# 8BIT_LOGIC_2.net
KiCad netlist of a schematic drawn in EAGLE
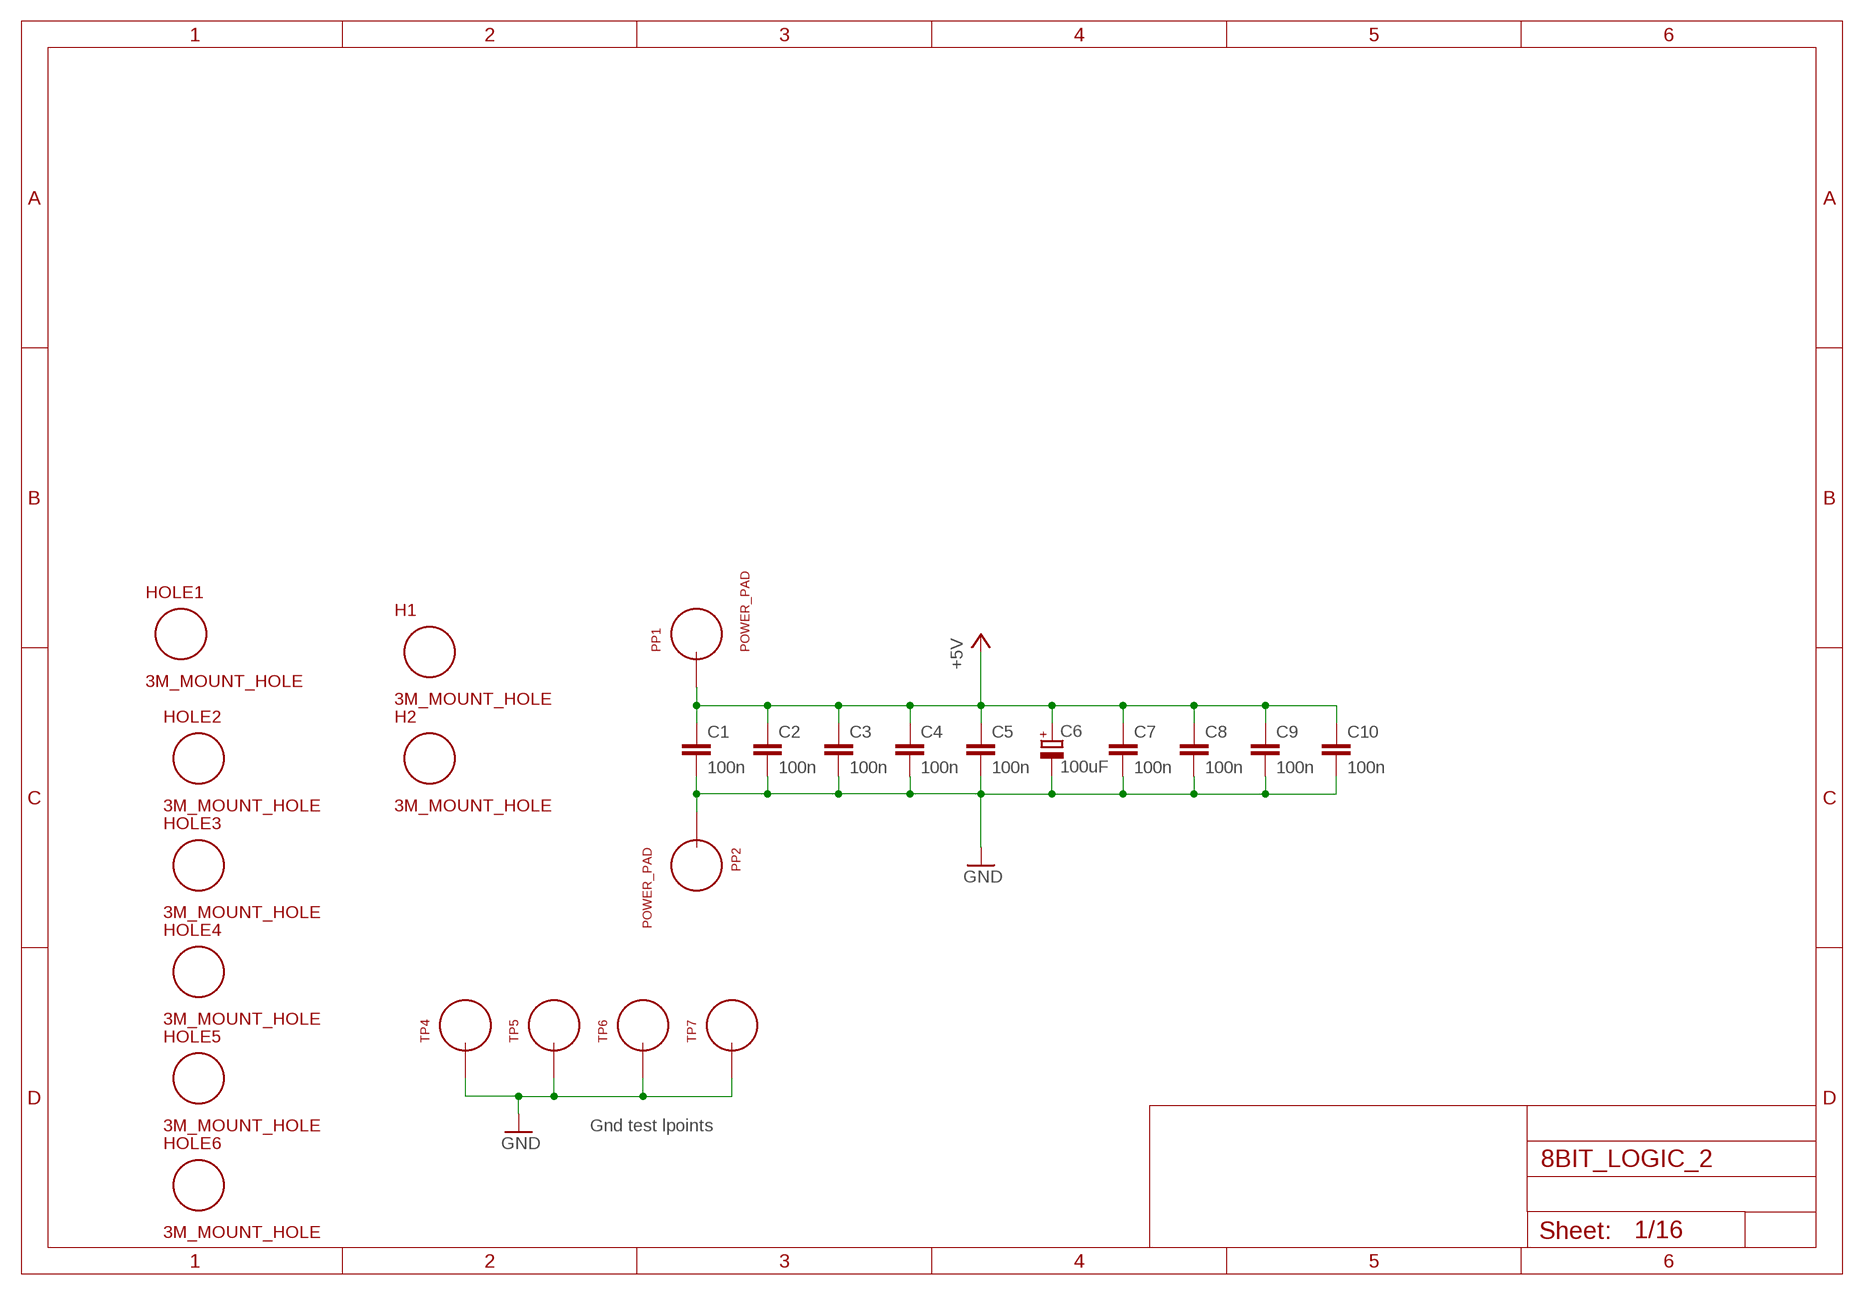
[diagram p0: schematic, sheet 1]
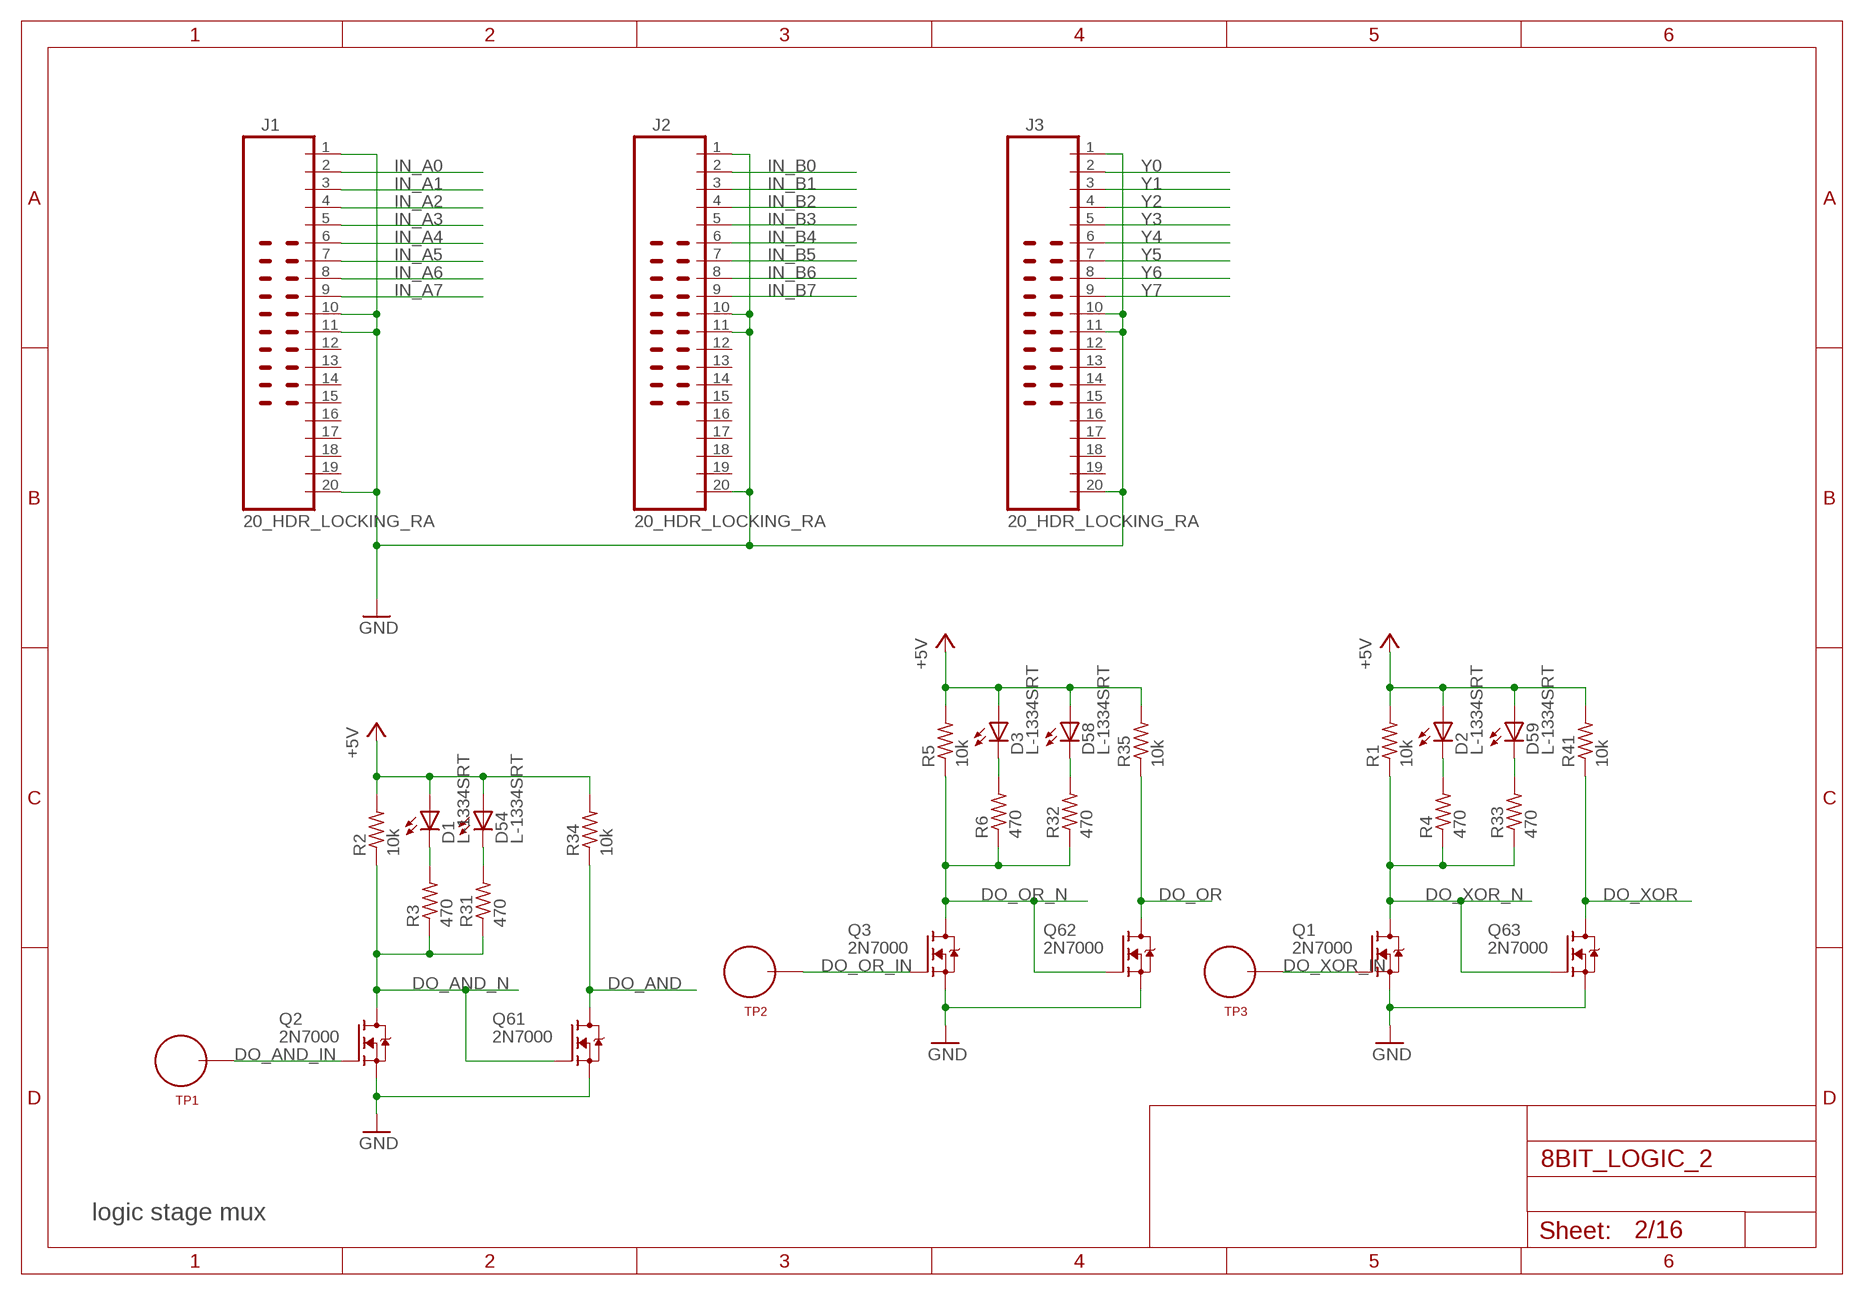
[diagram p1: schematic, sheet 2]
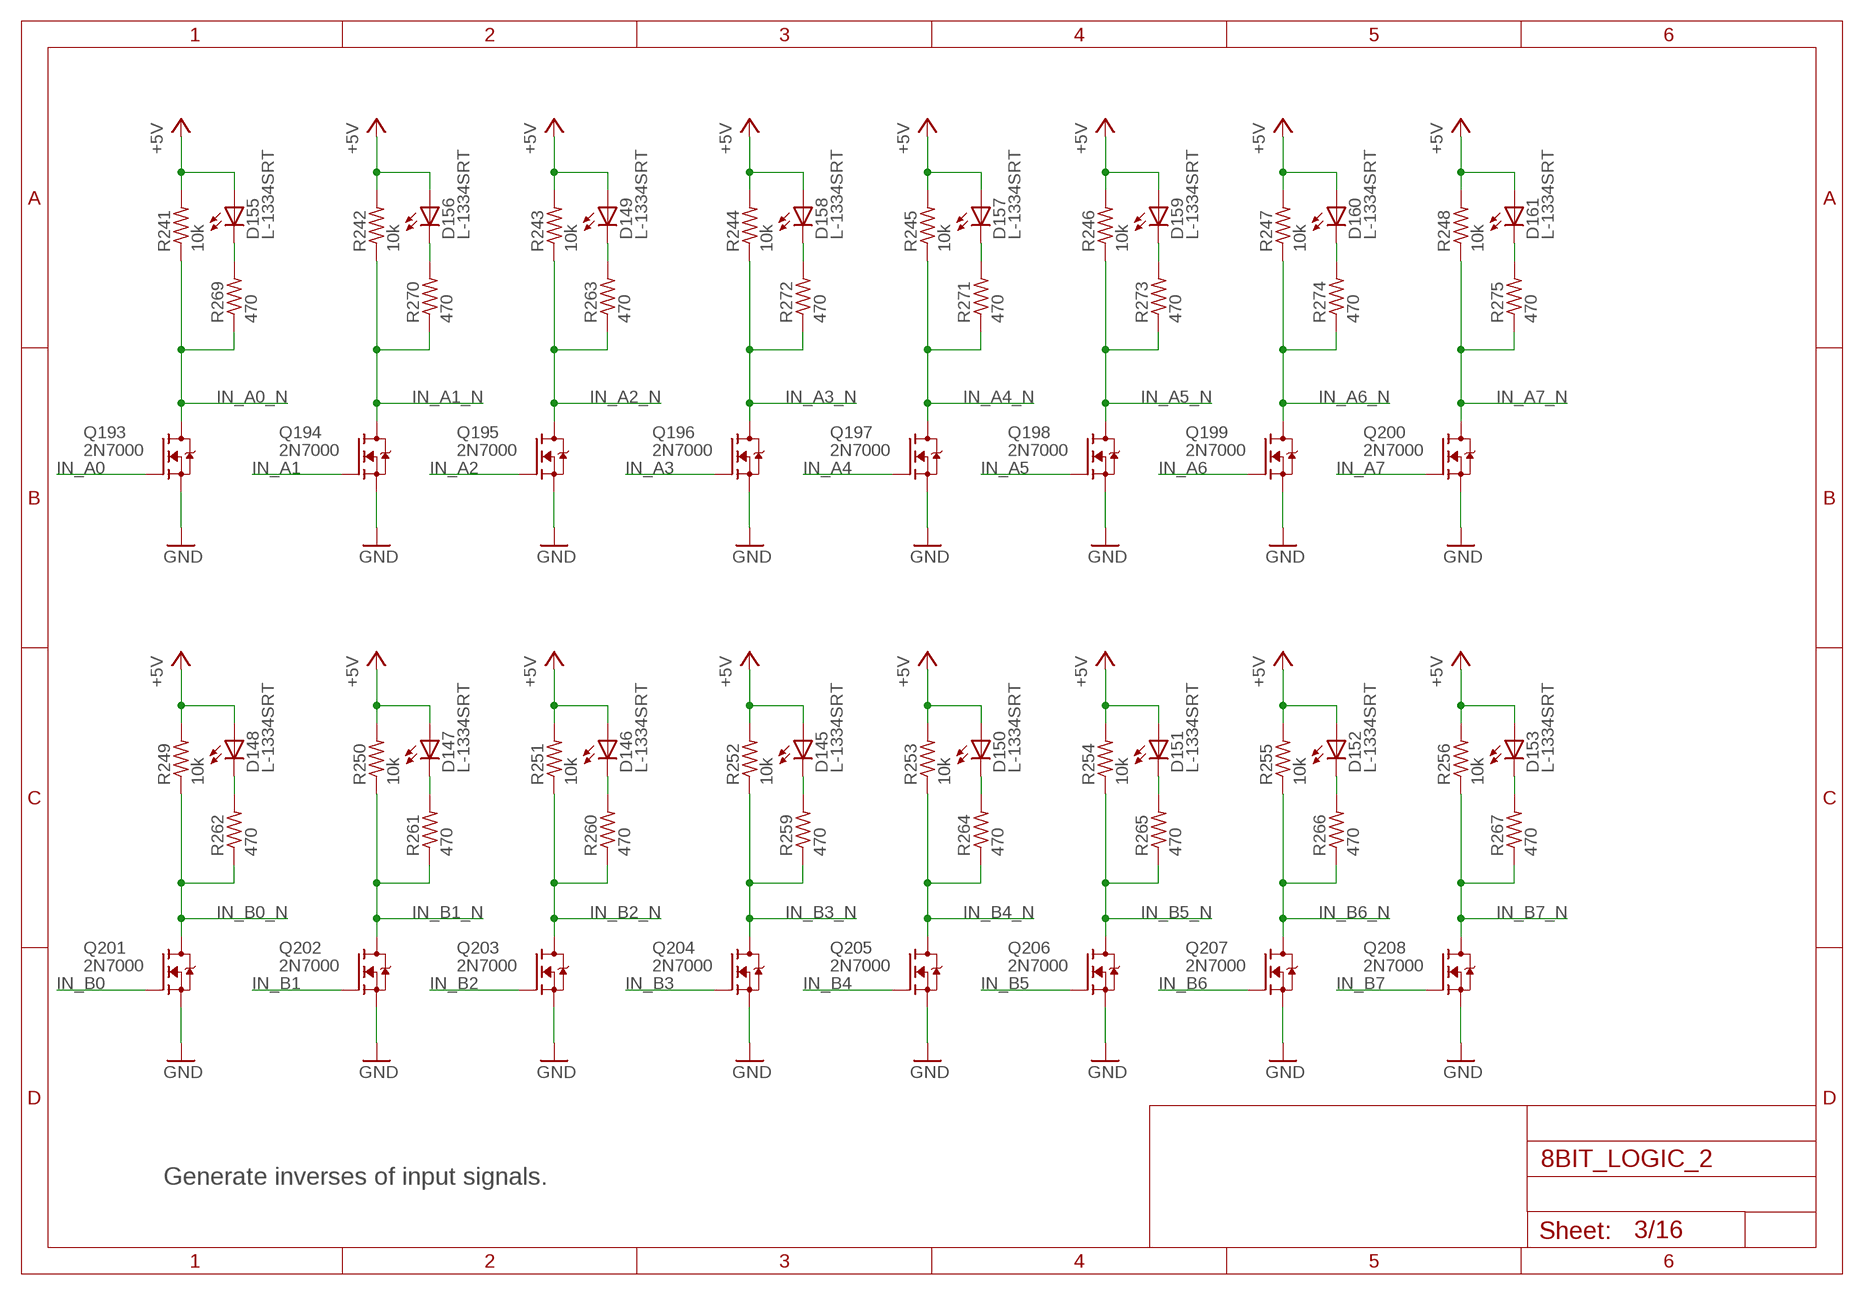
[diagram p2: schematic, sheet 3]
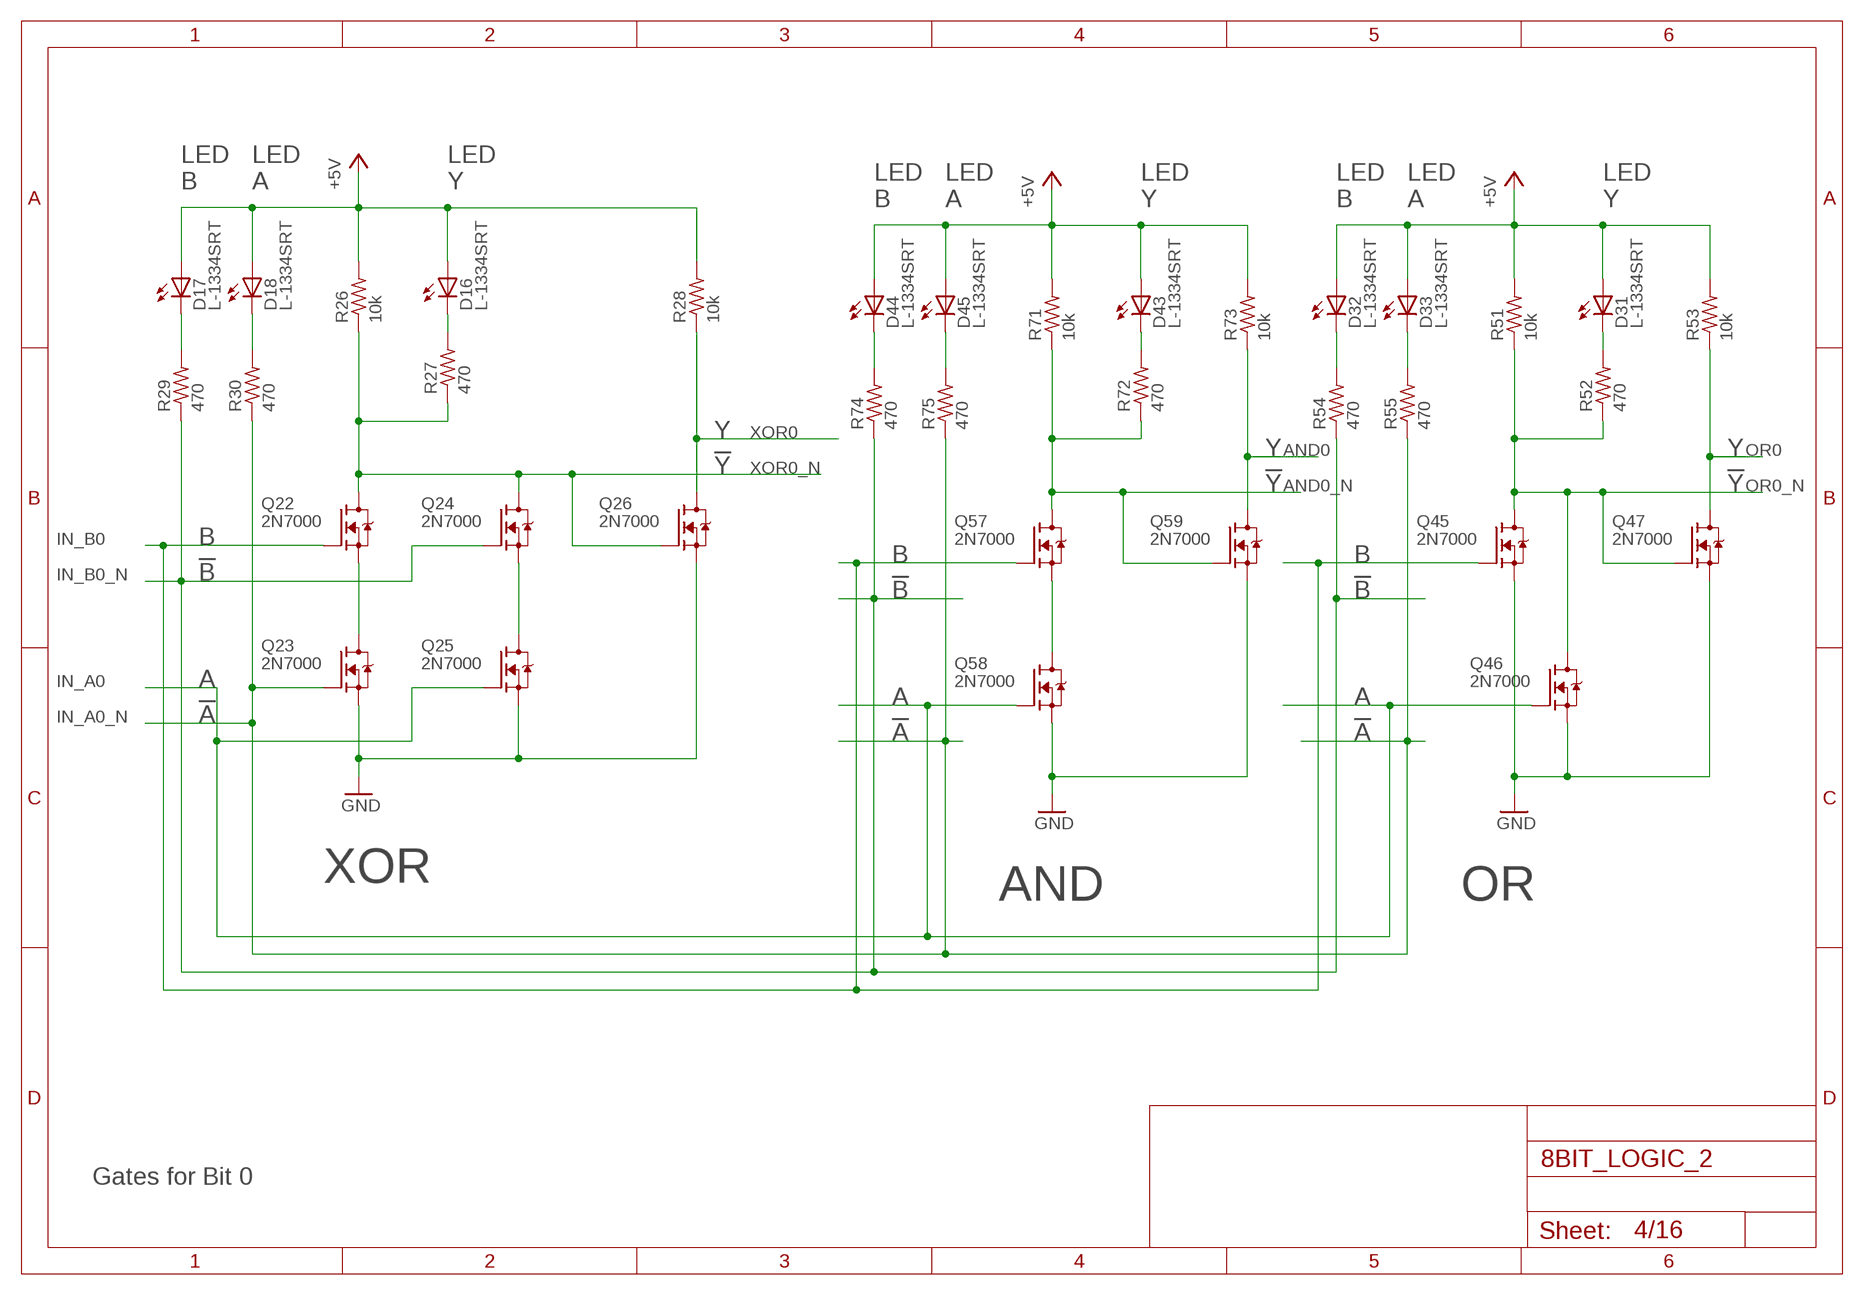
[diagram p3: schematic, sheet 4]
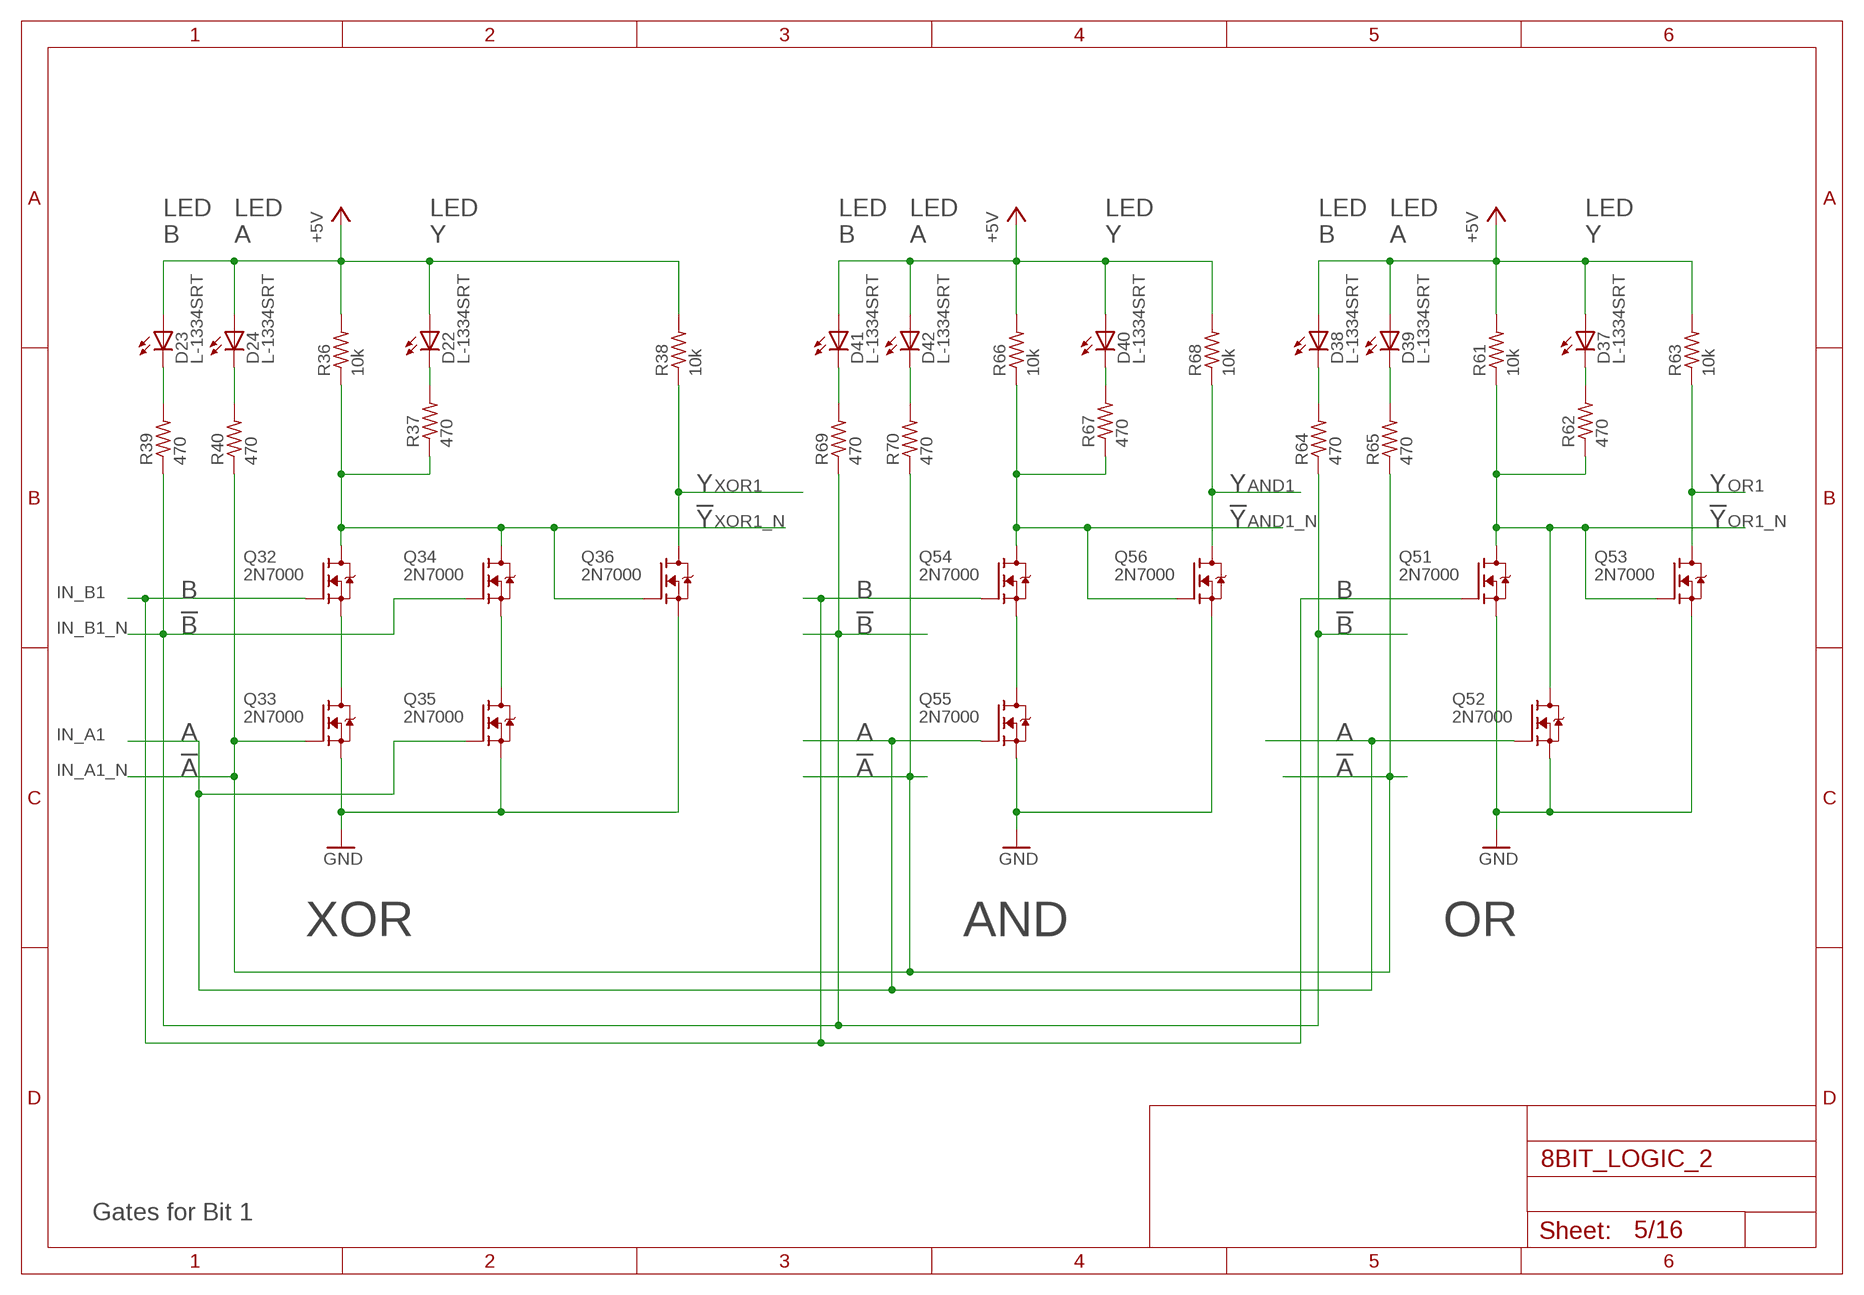
[diagram p4: schematic, sheet 5]
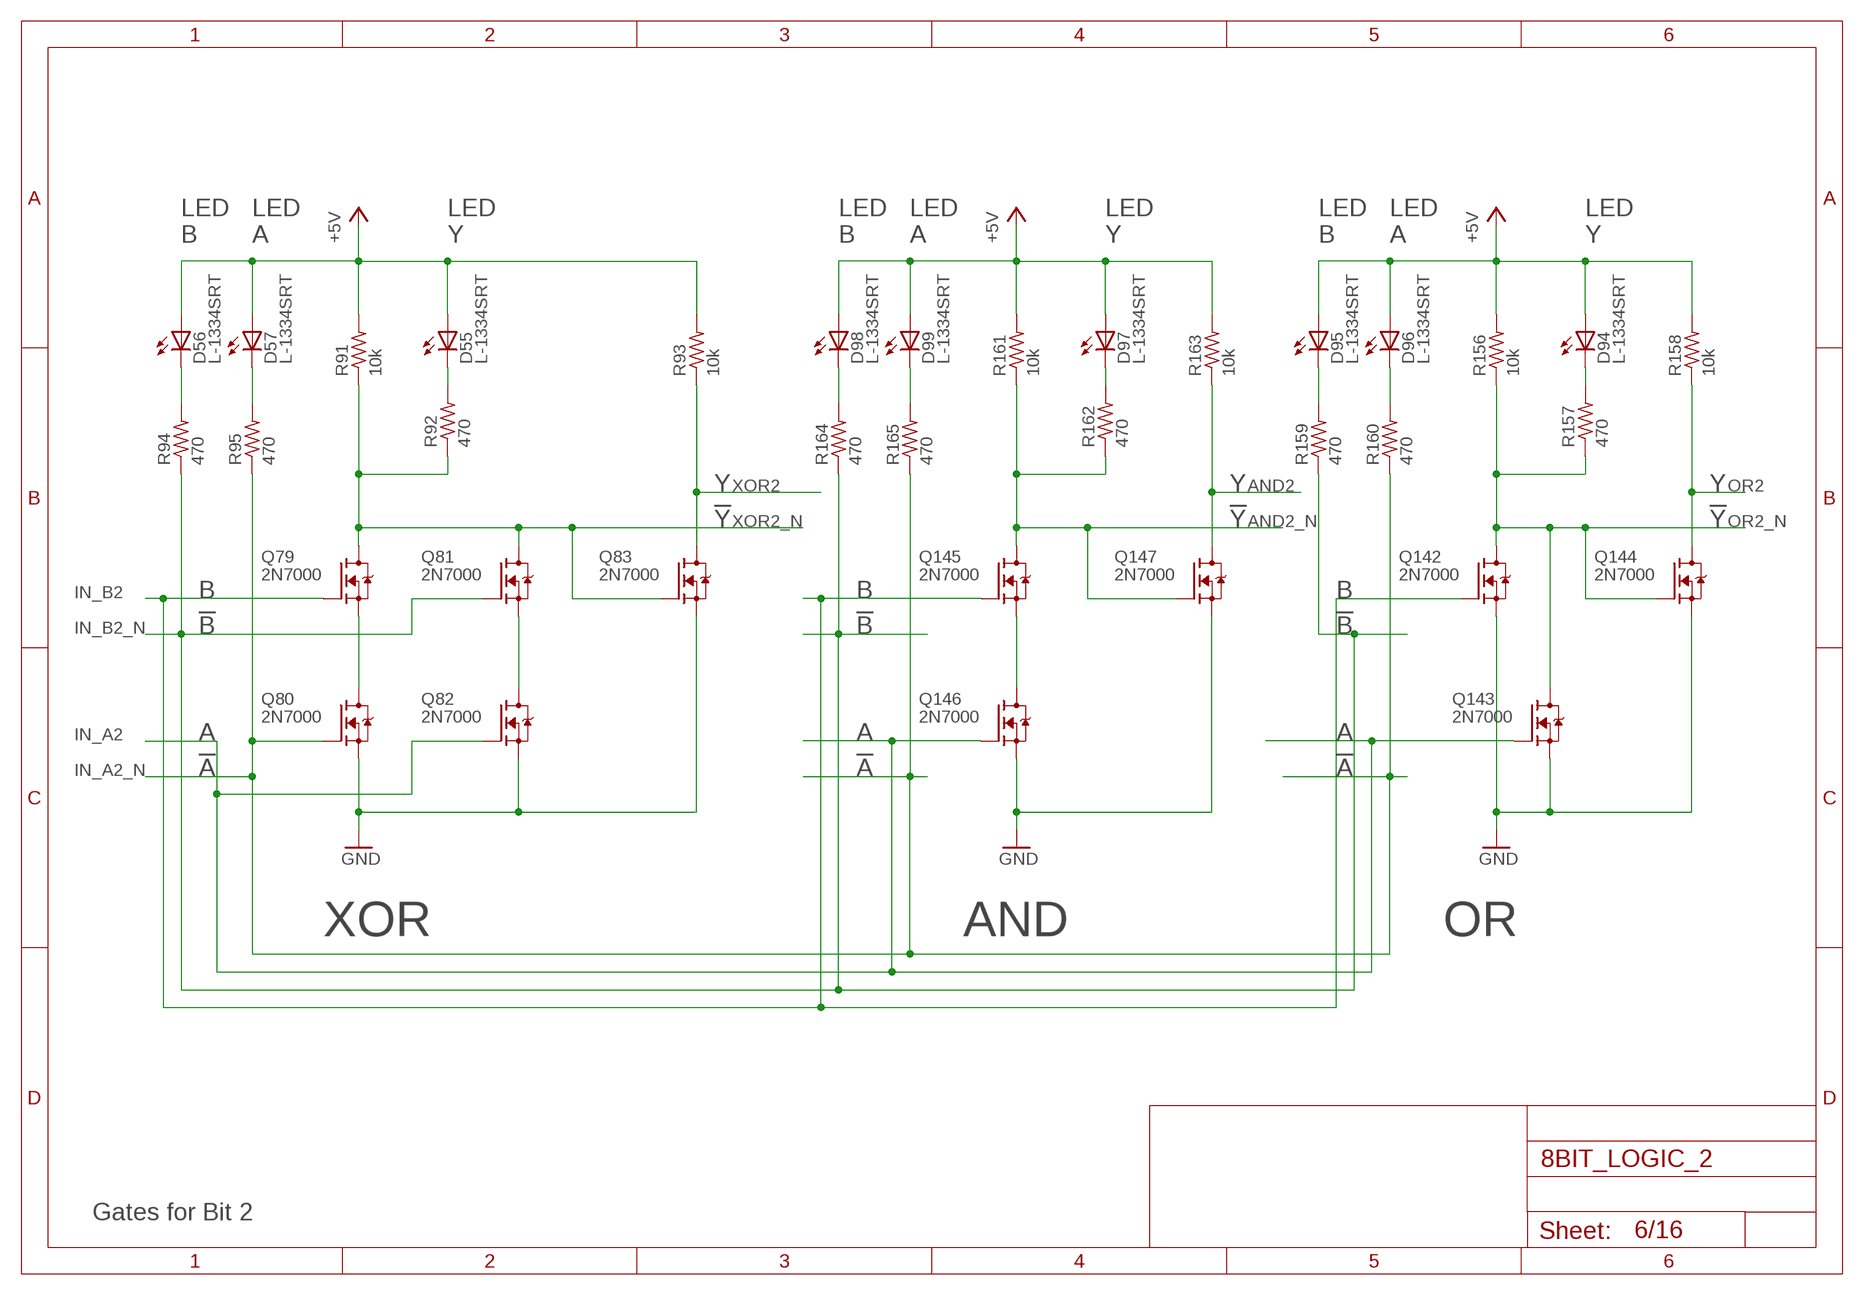
[diagram p5: schematic, sheet 6]
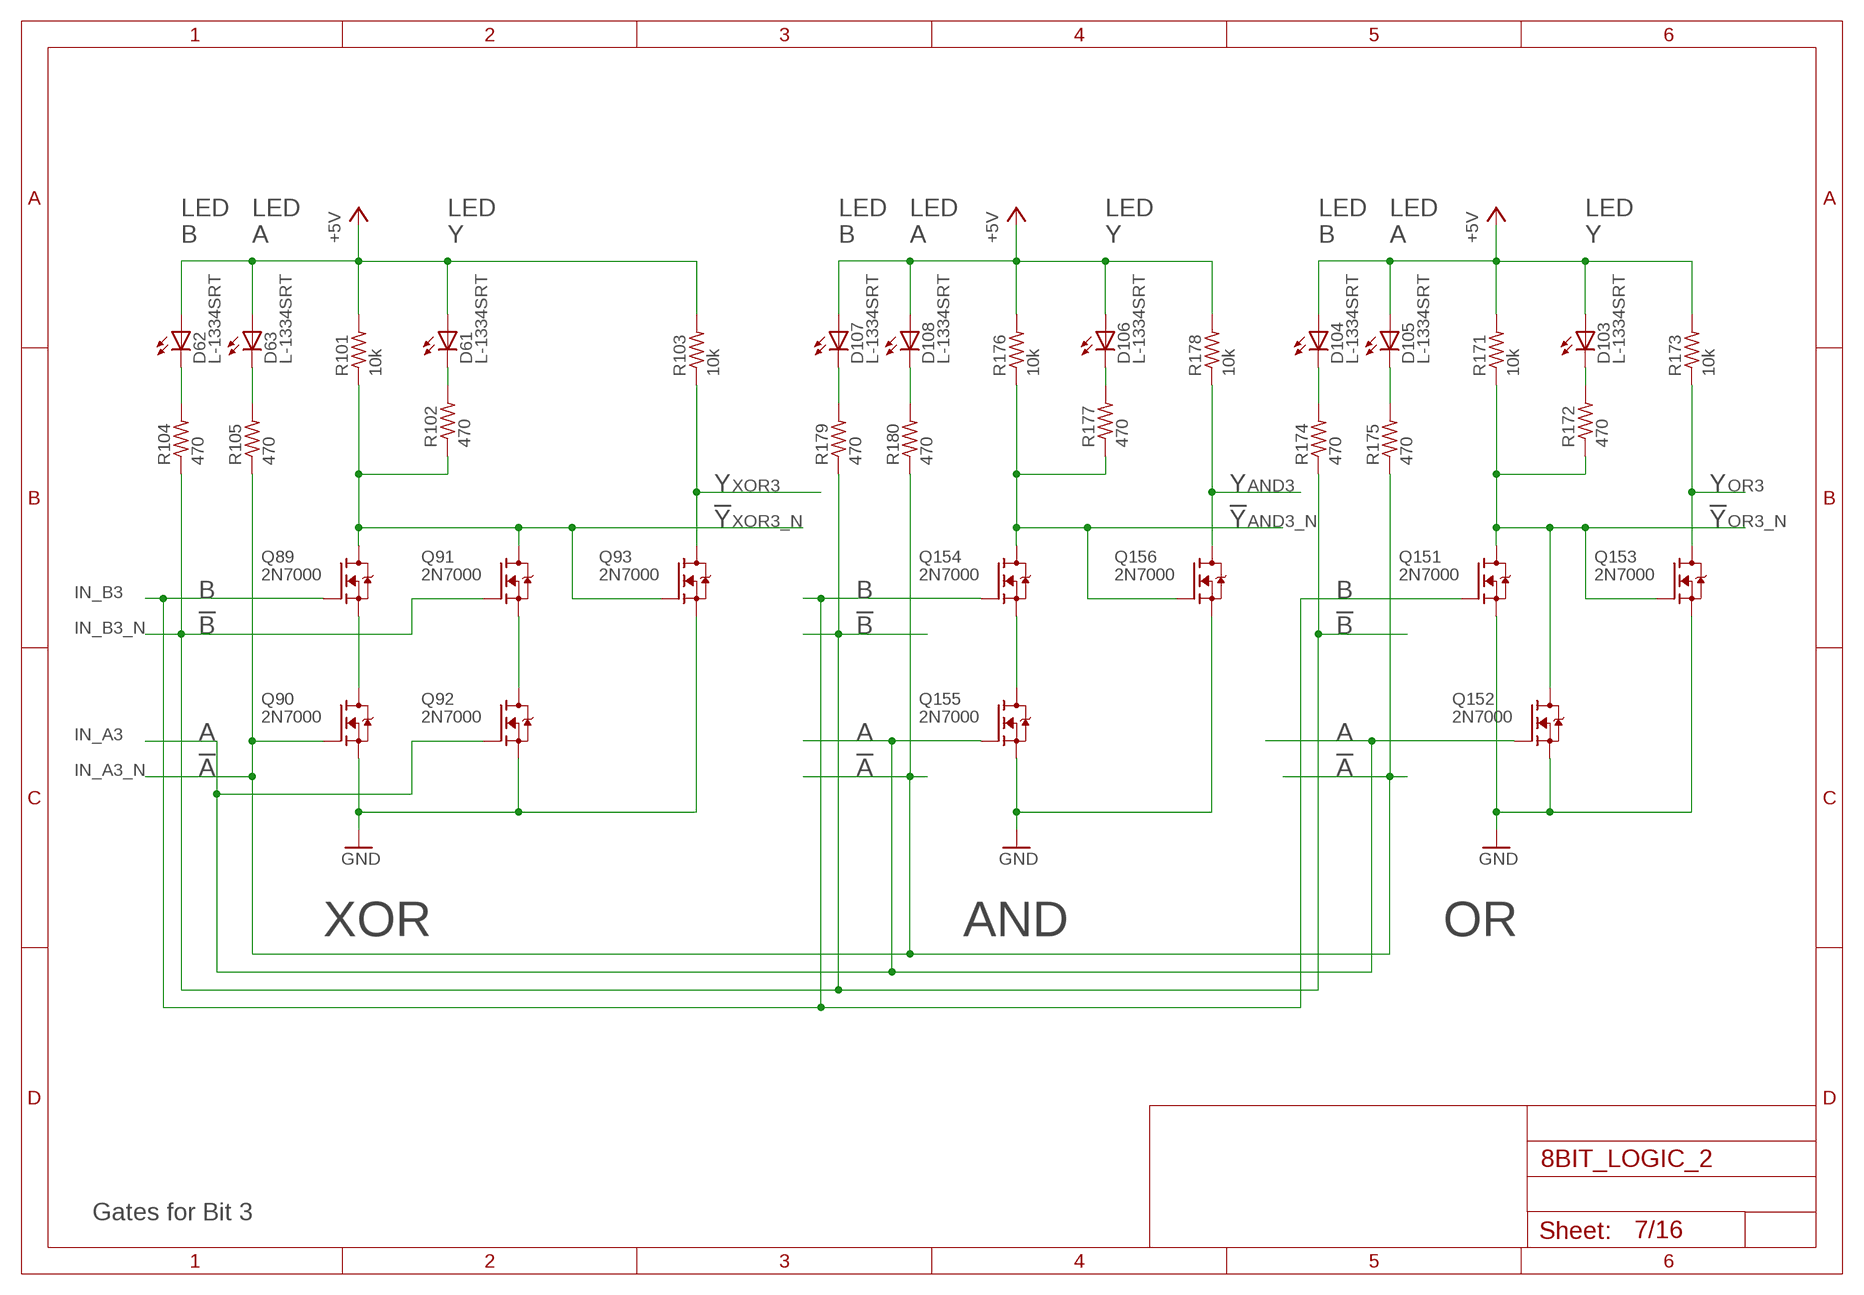
[diagram p6: schematic, sheet 7]
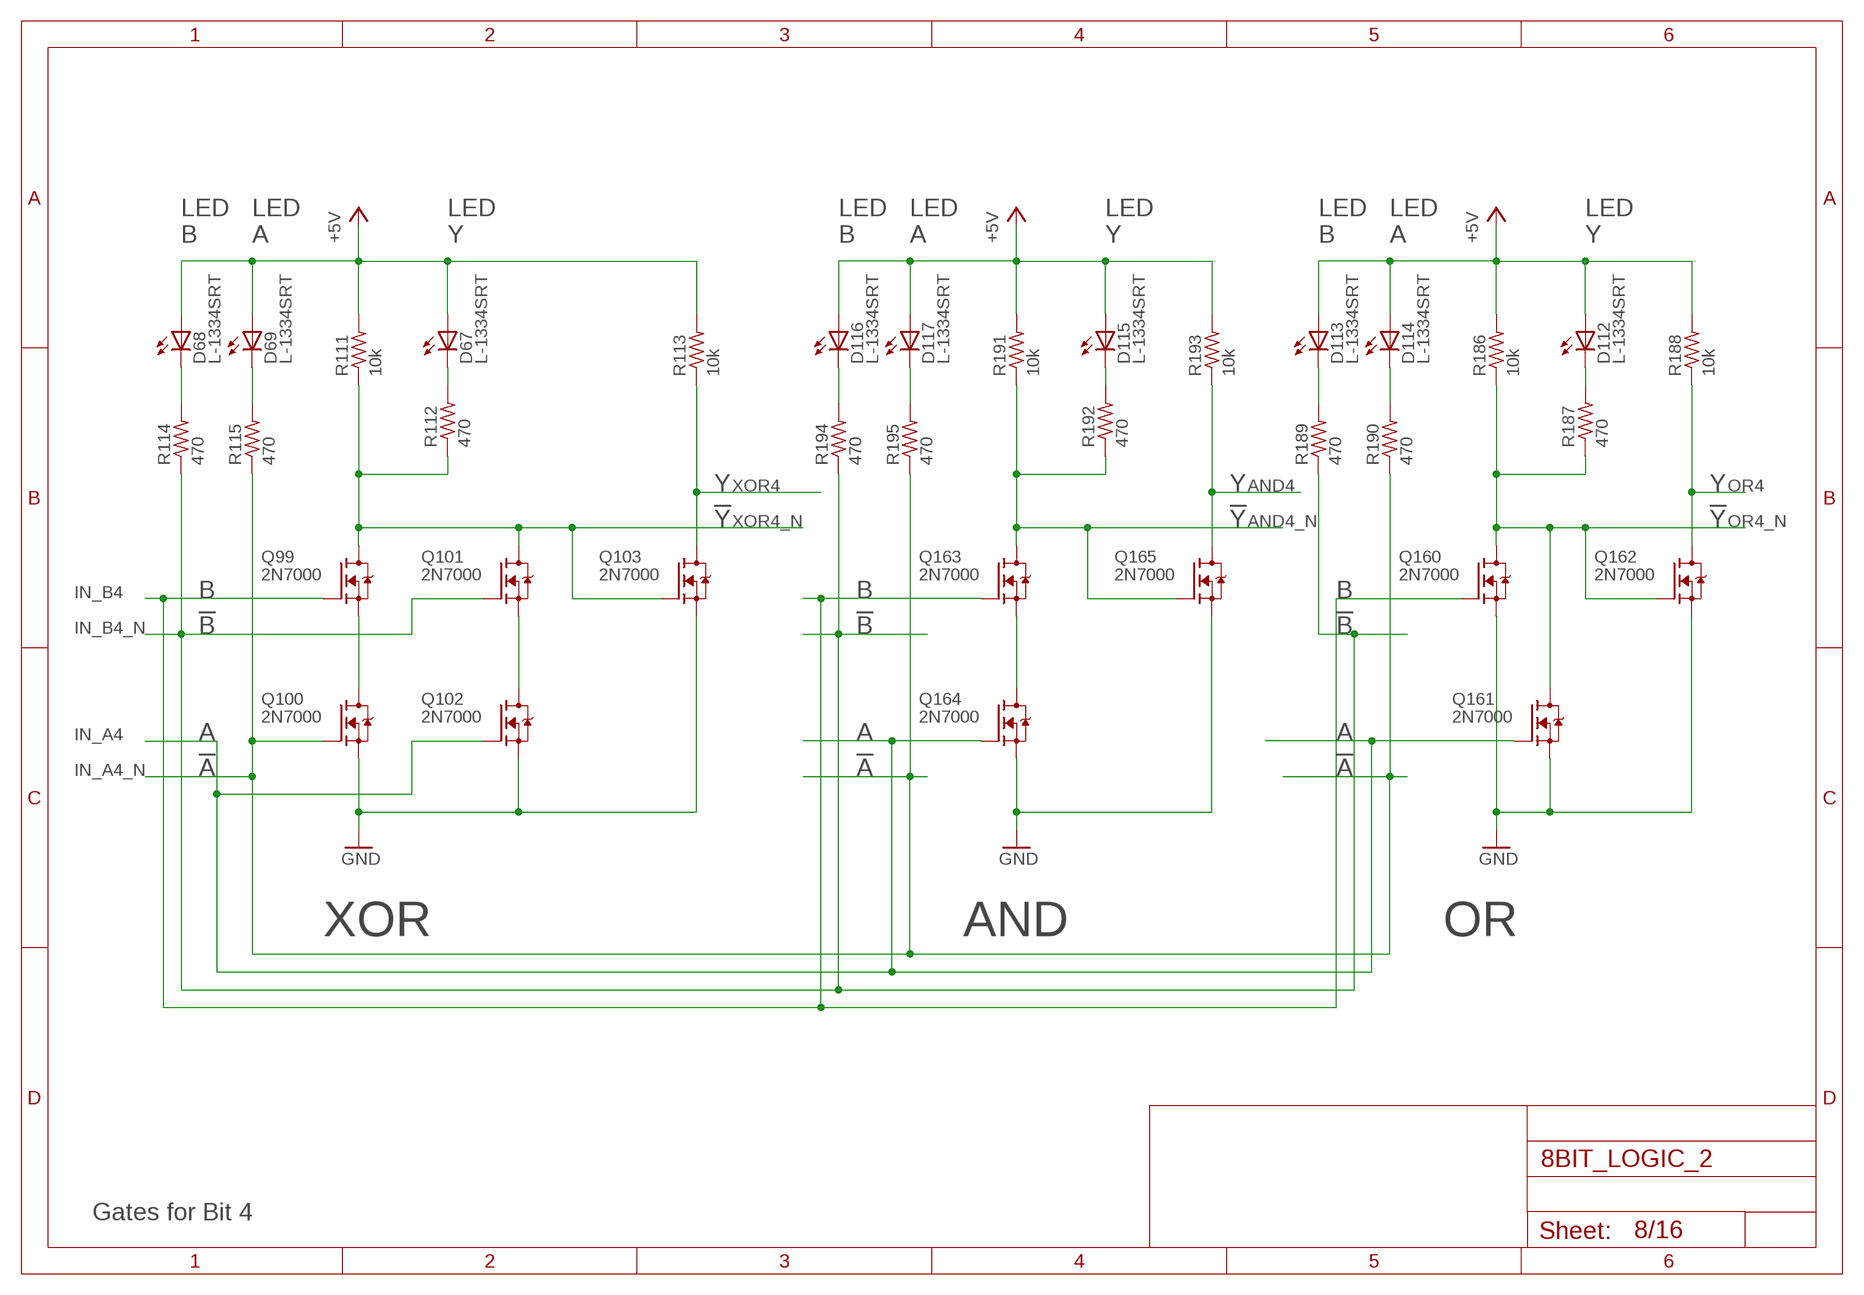
[diagram p7: schematic, sheet 8]
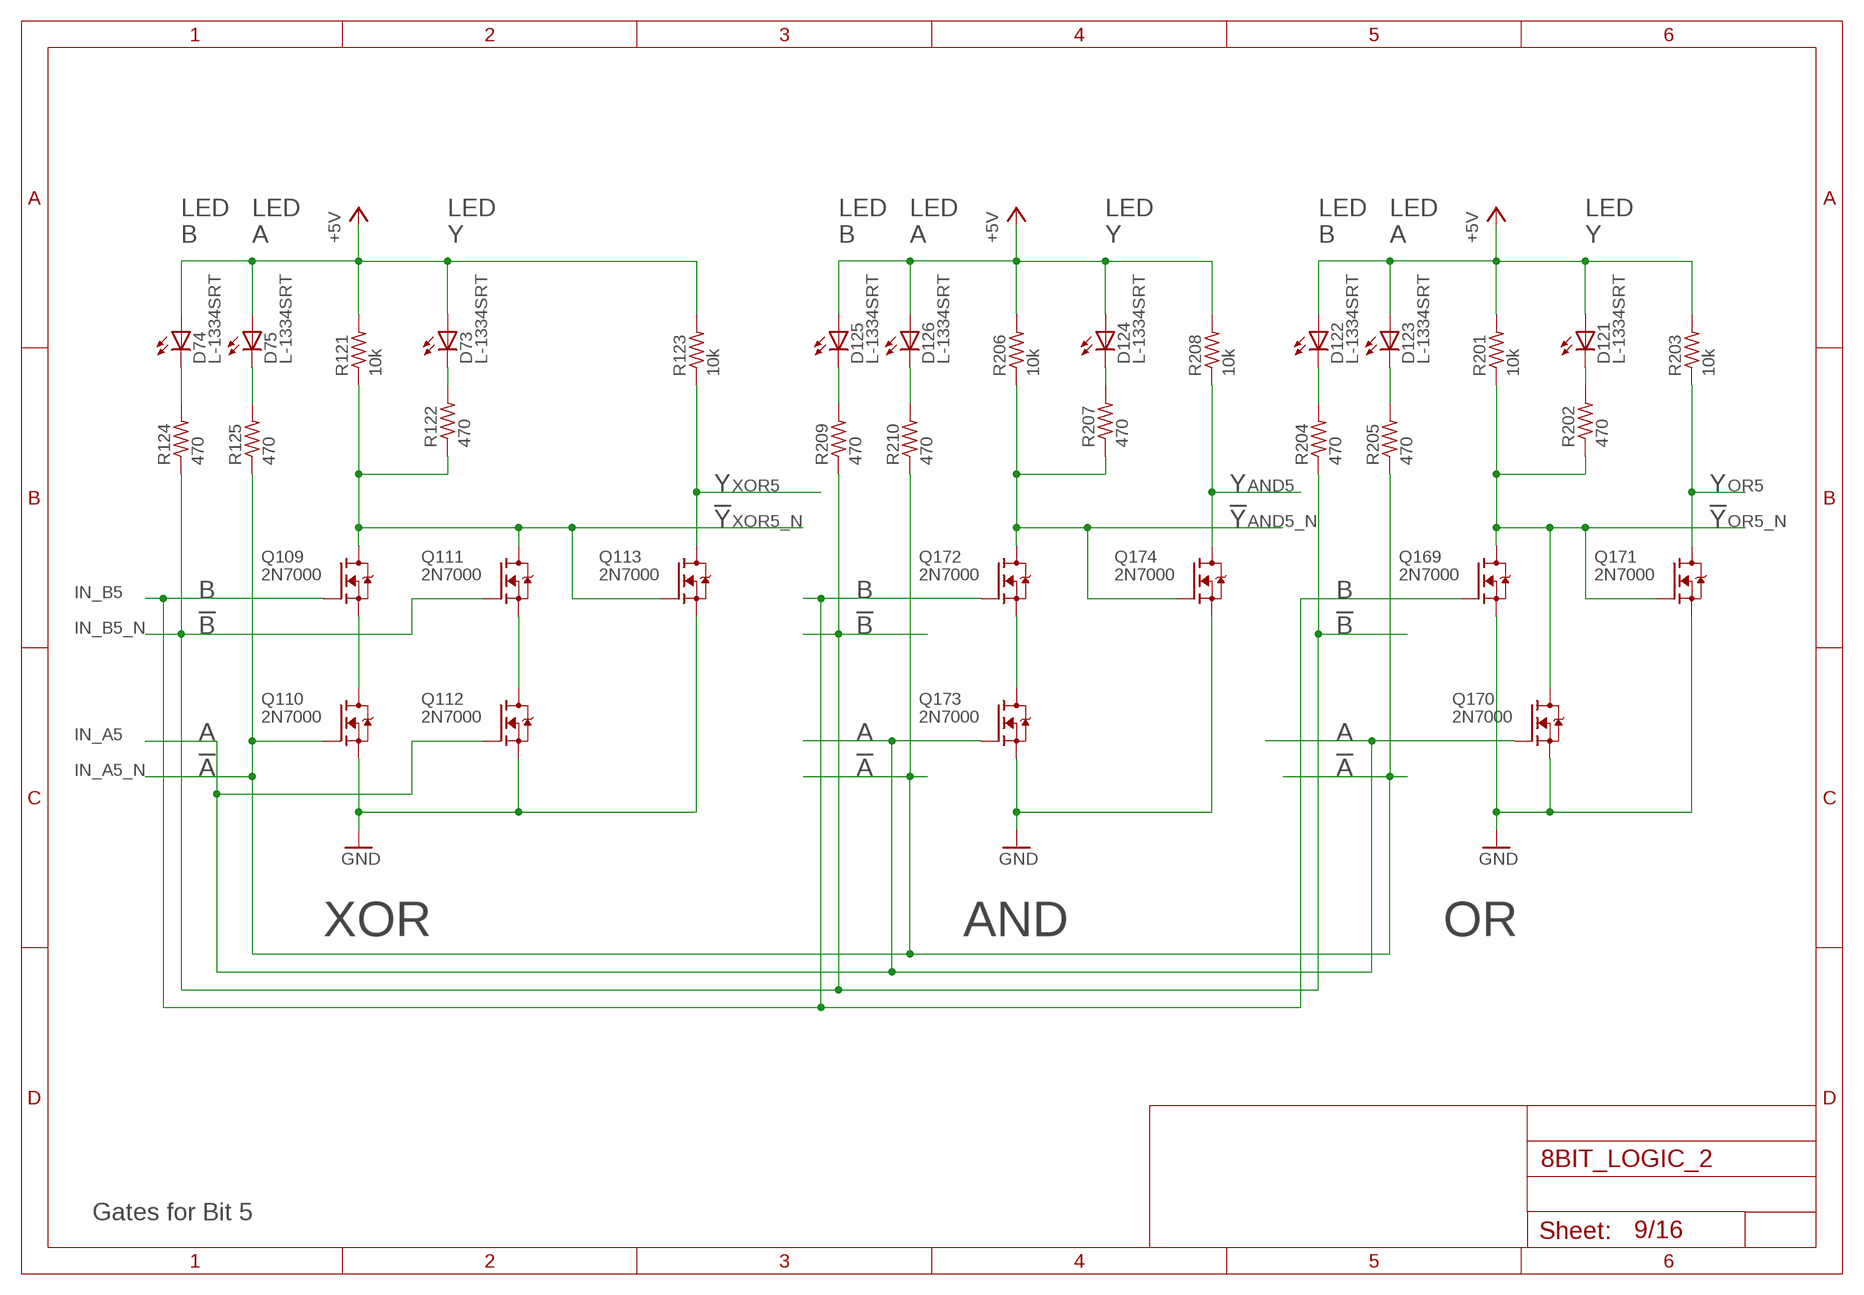
[diagram p8: schematic, sheet 9]
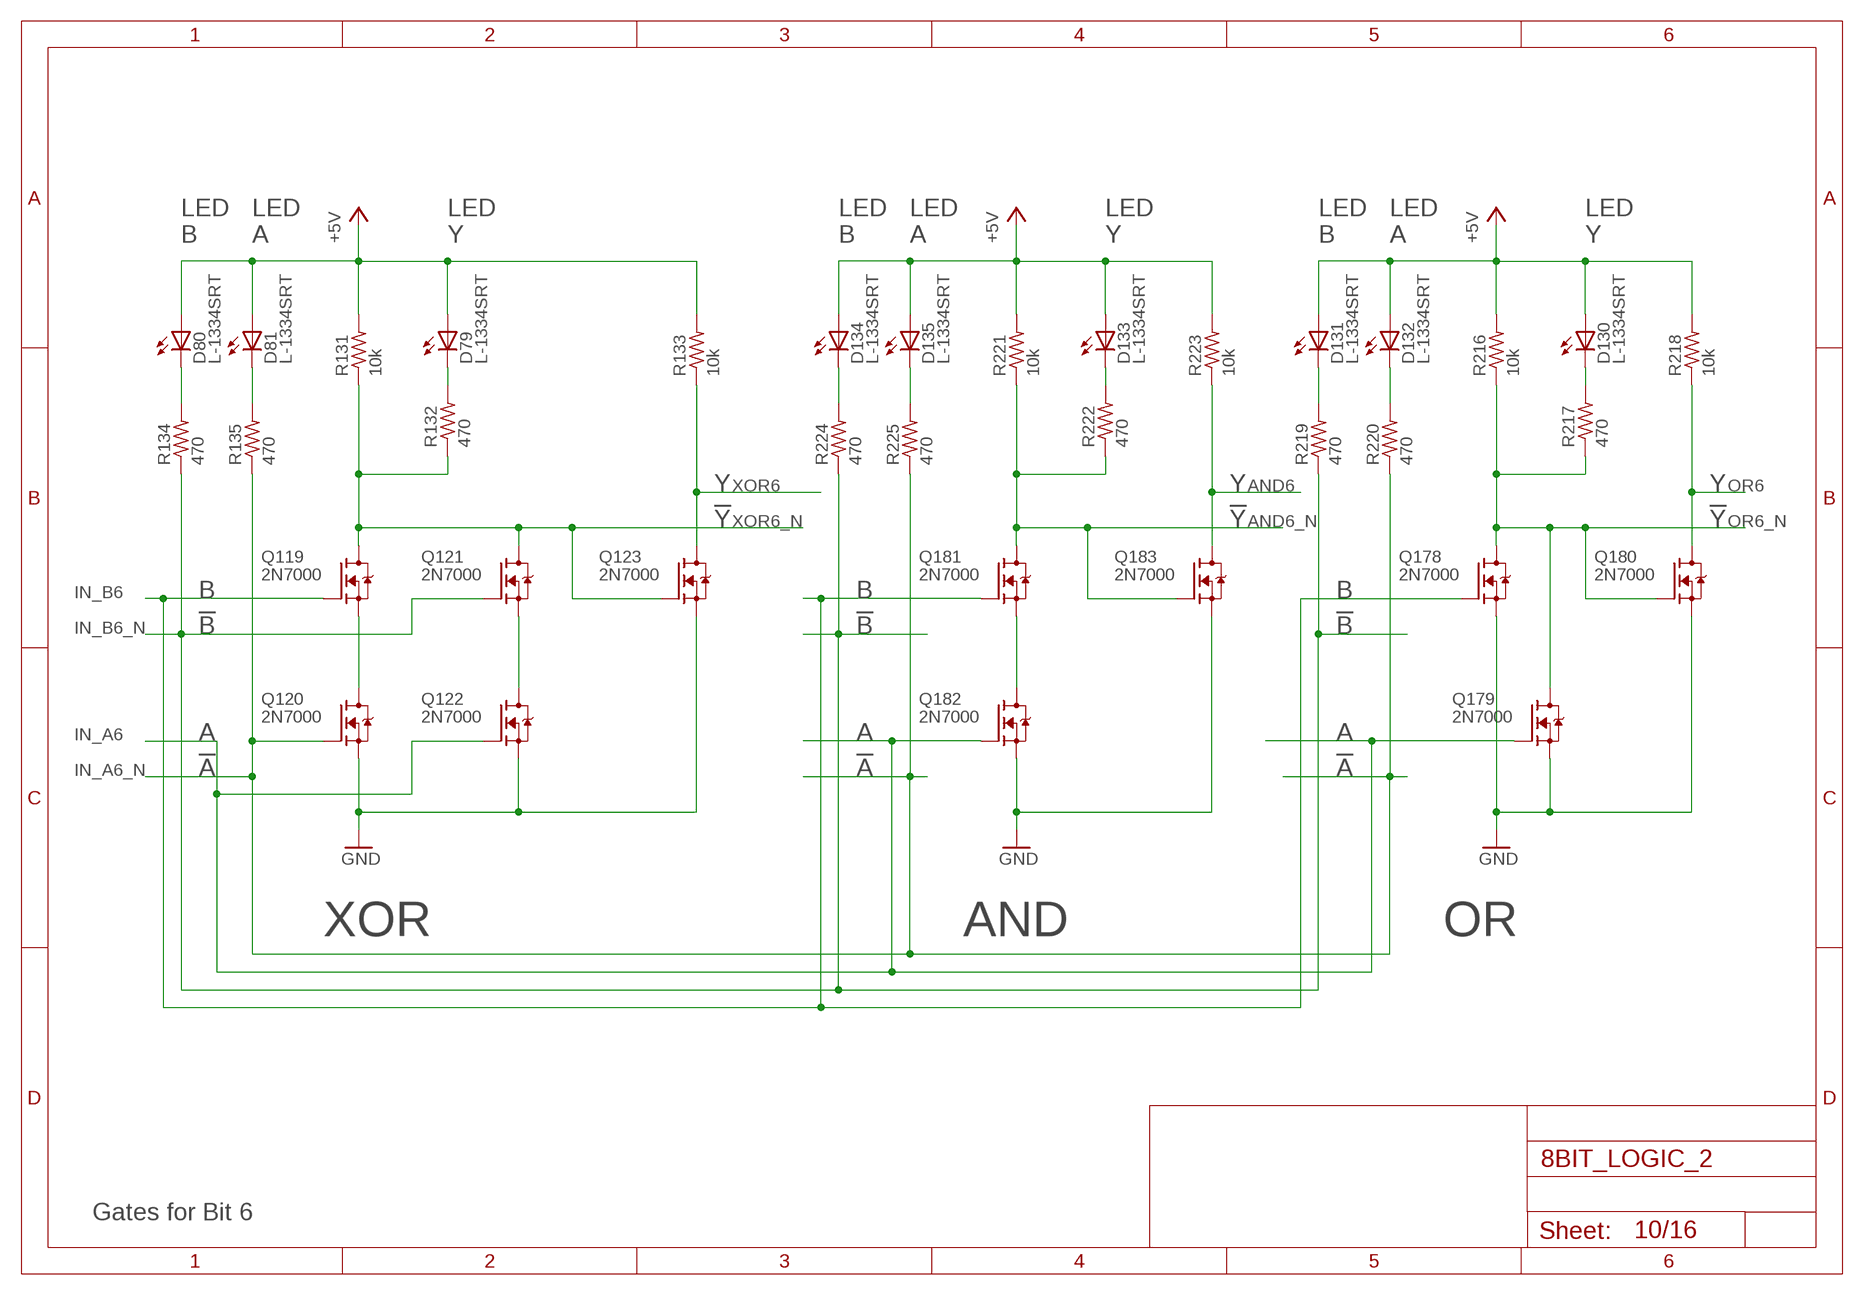
[diagram p9: schematic, sheet 10]
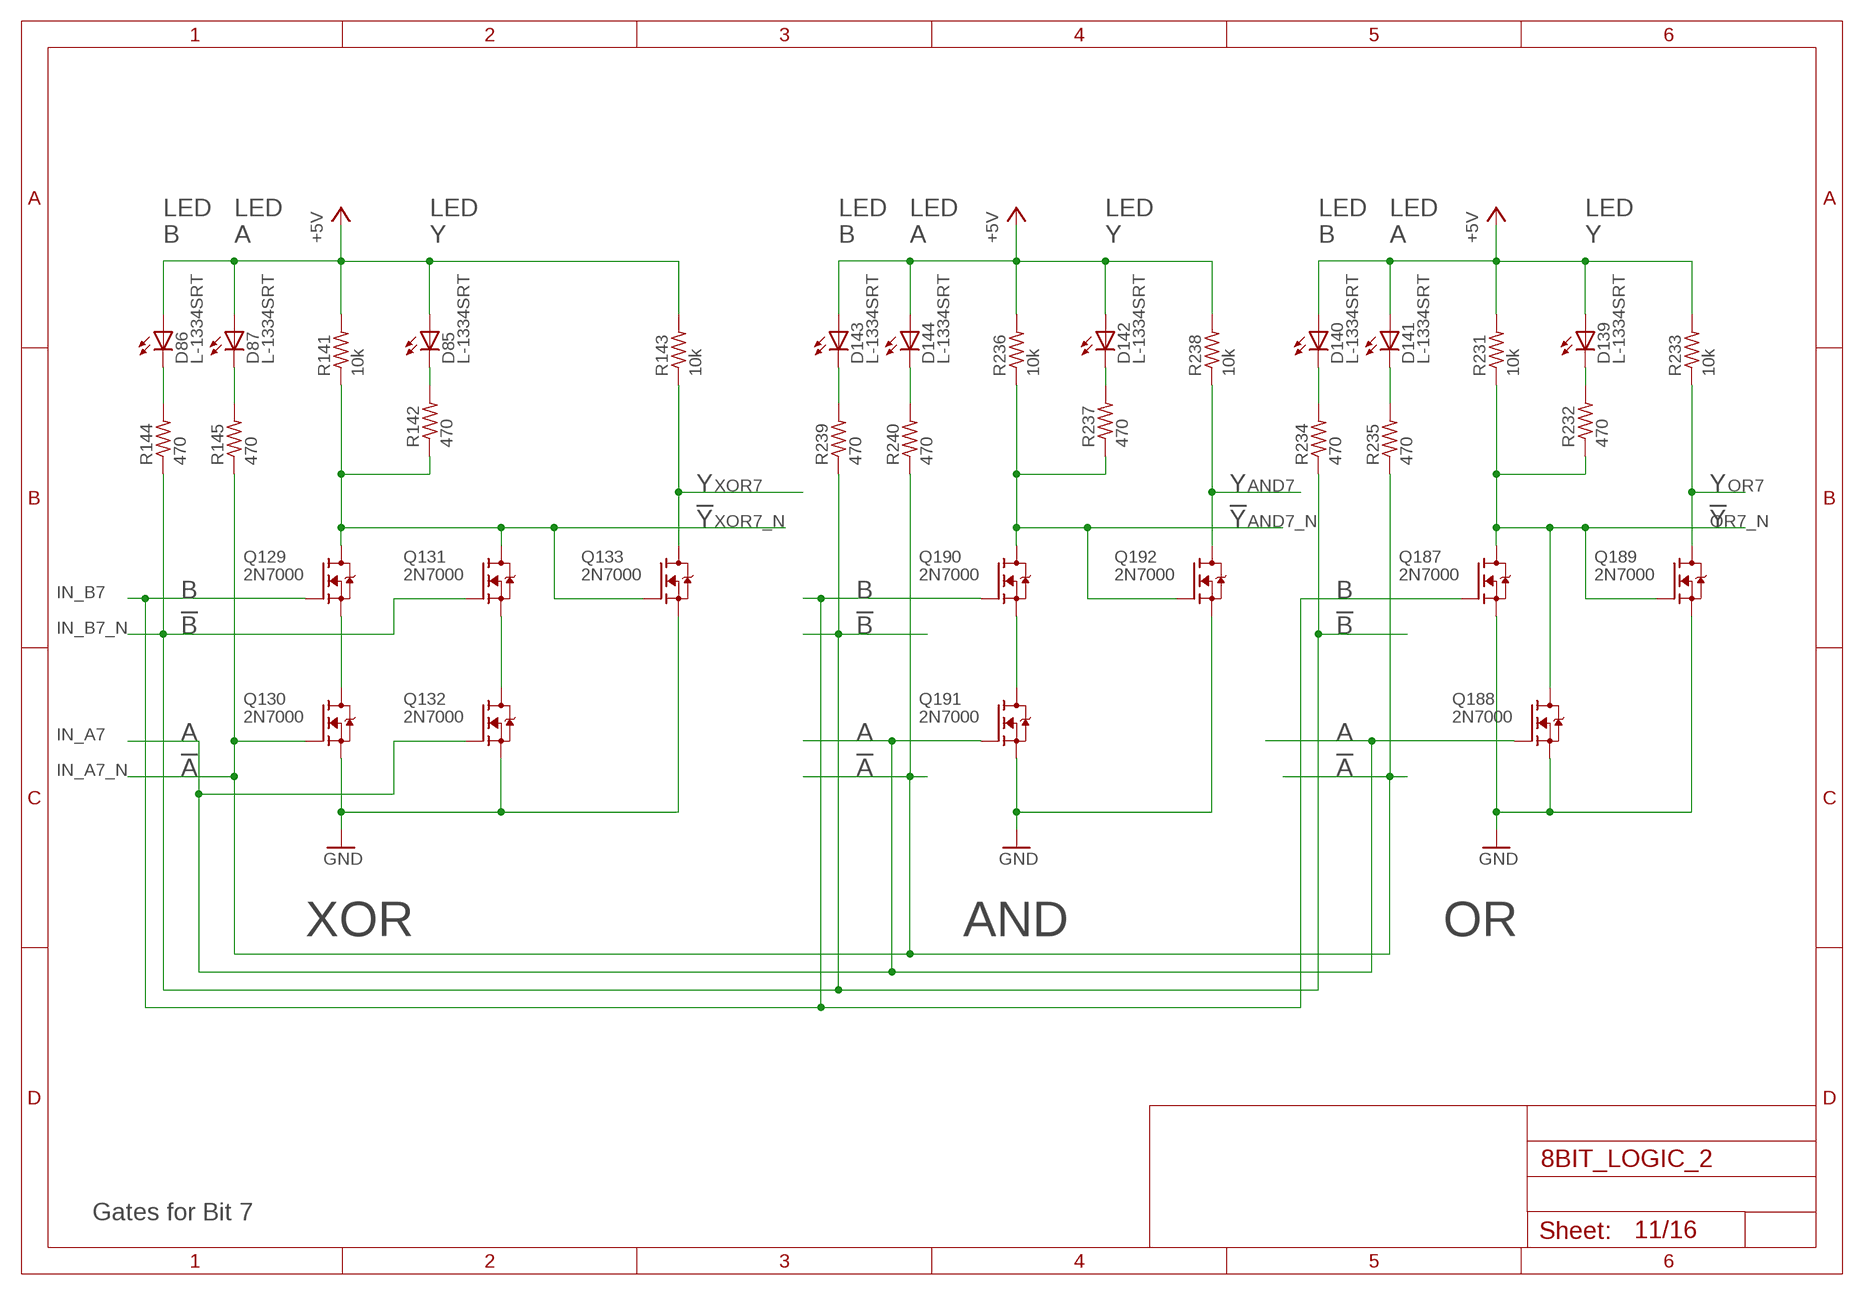
[diagram p10: schematic, sheet 11]
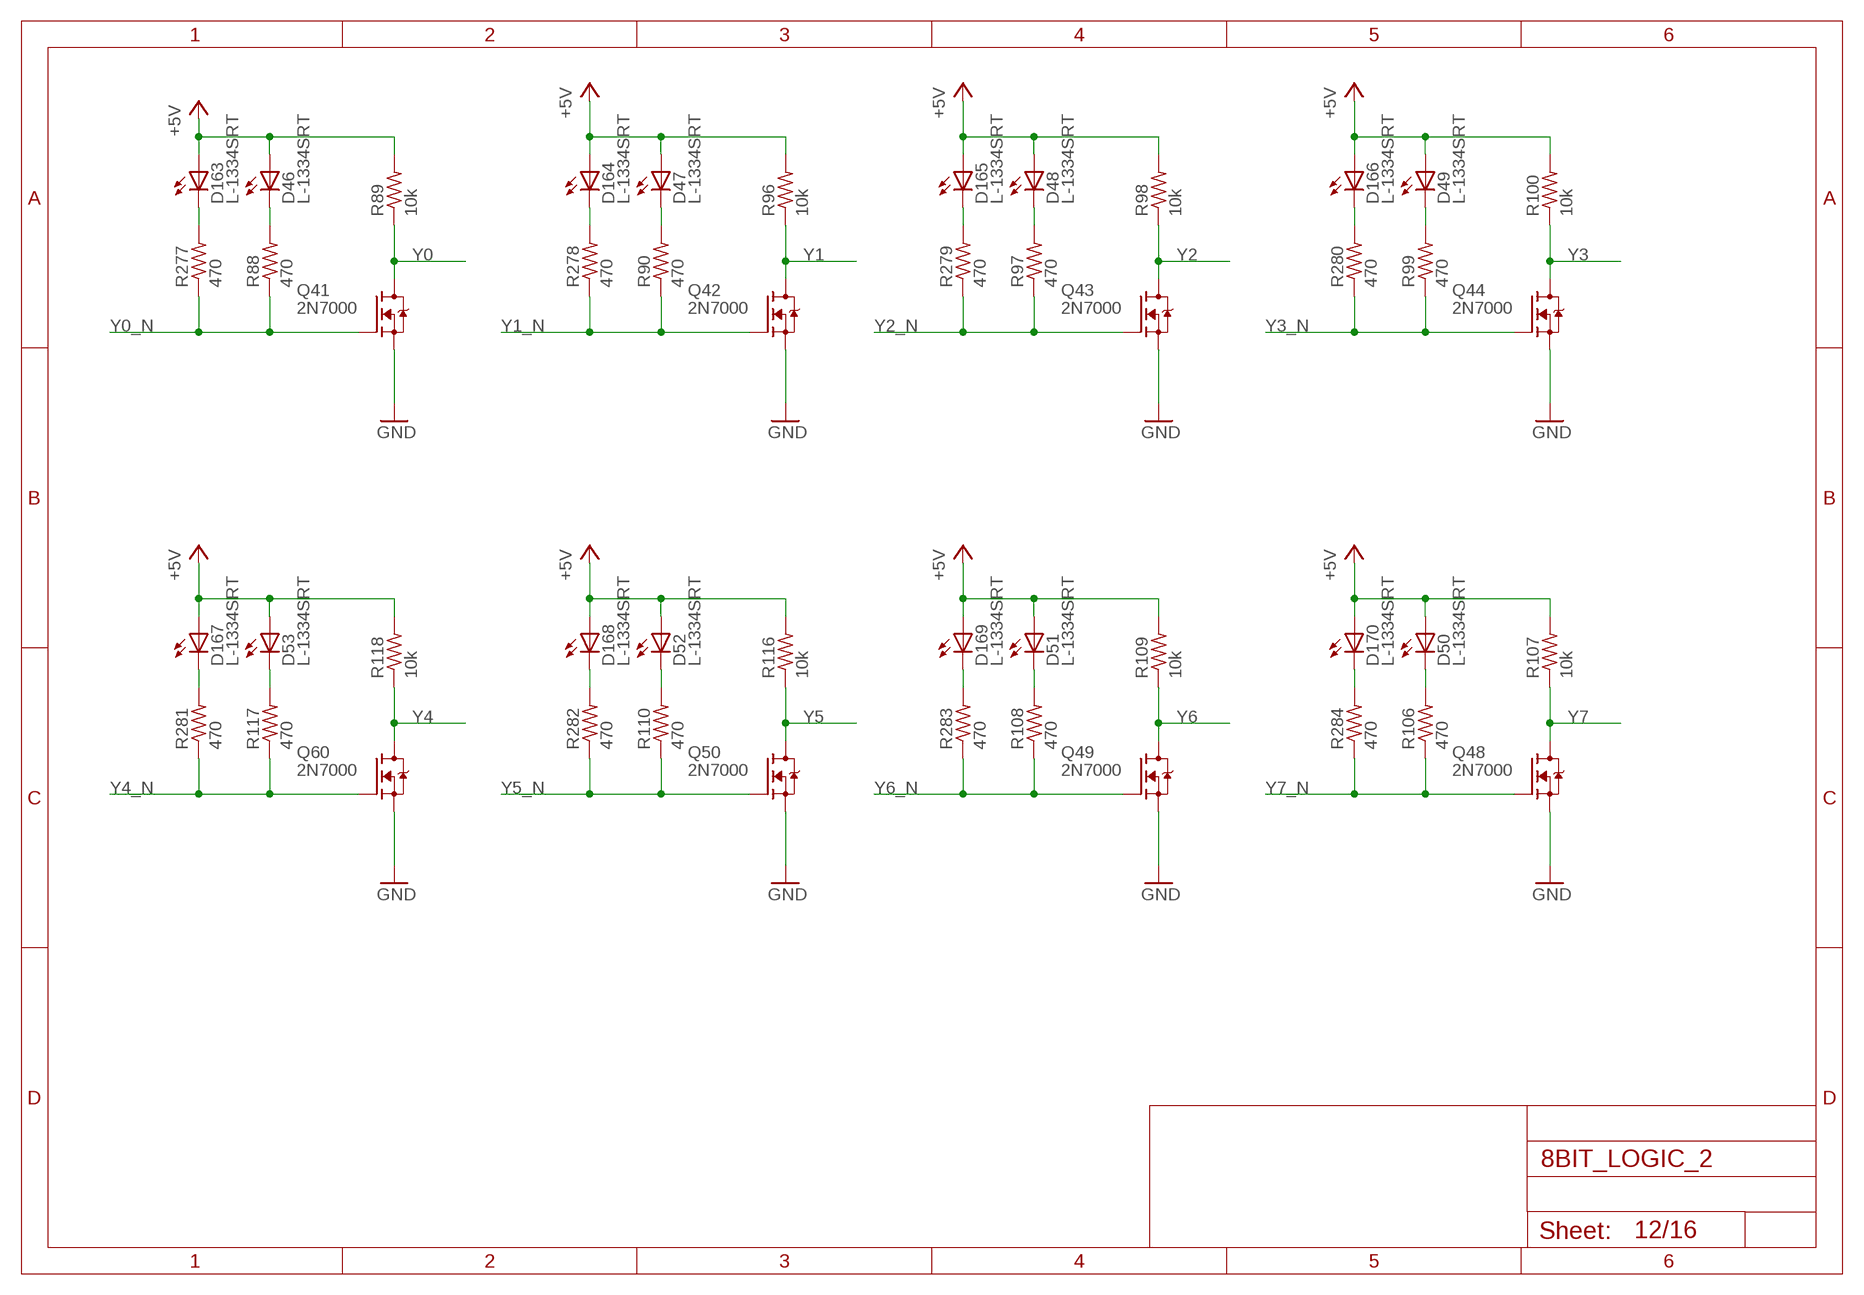
[diagram p11: schematic, sheet 12]
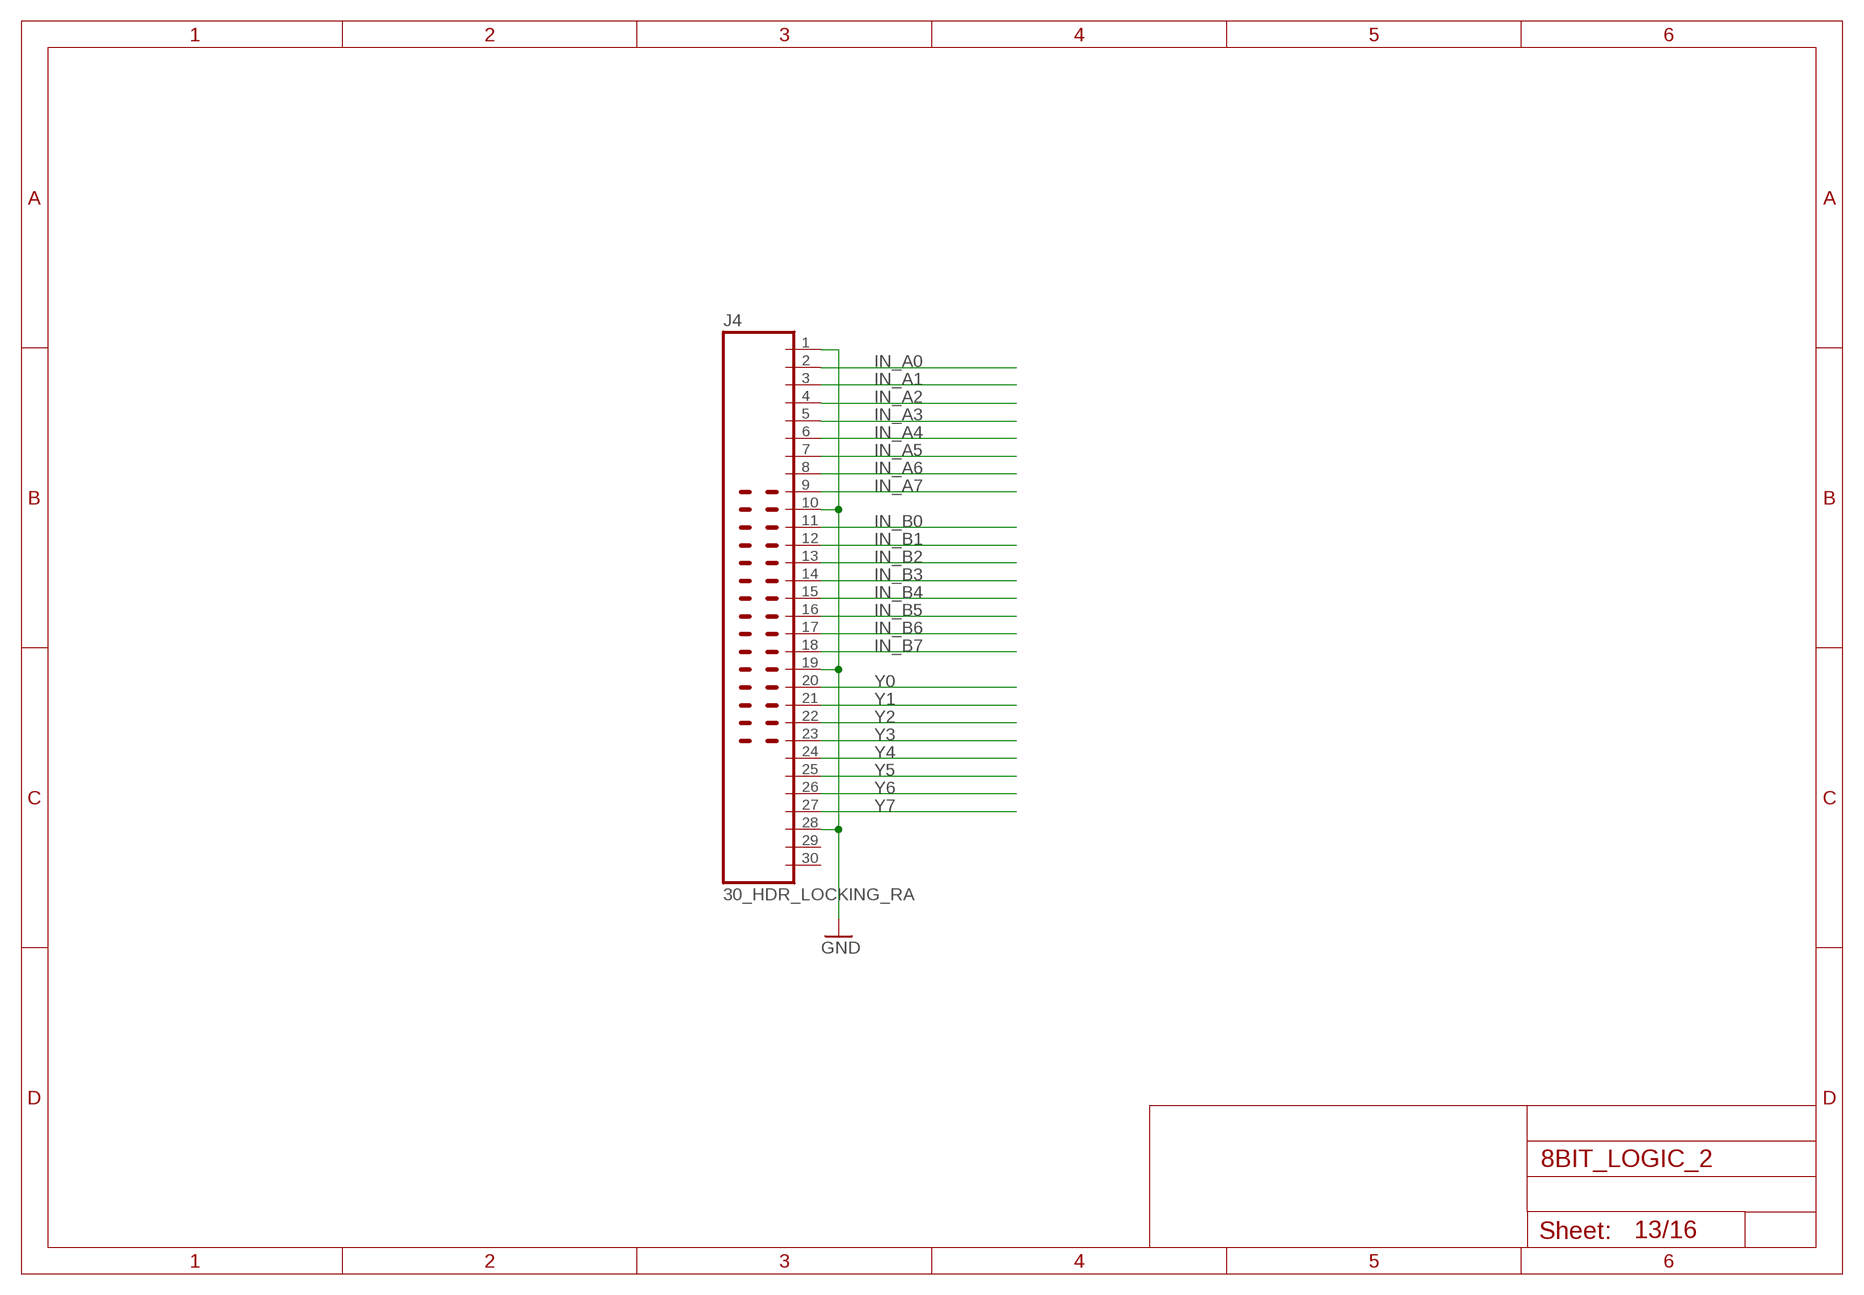
[diagram p12: schematic, sheet 13]
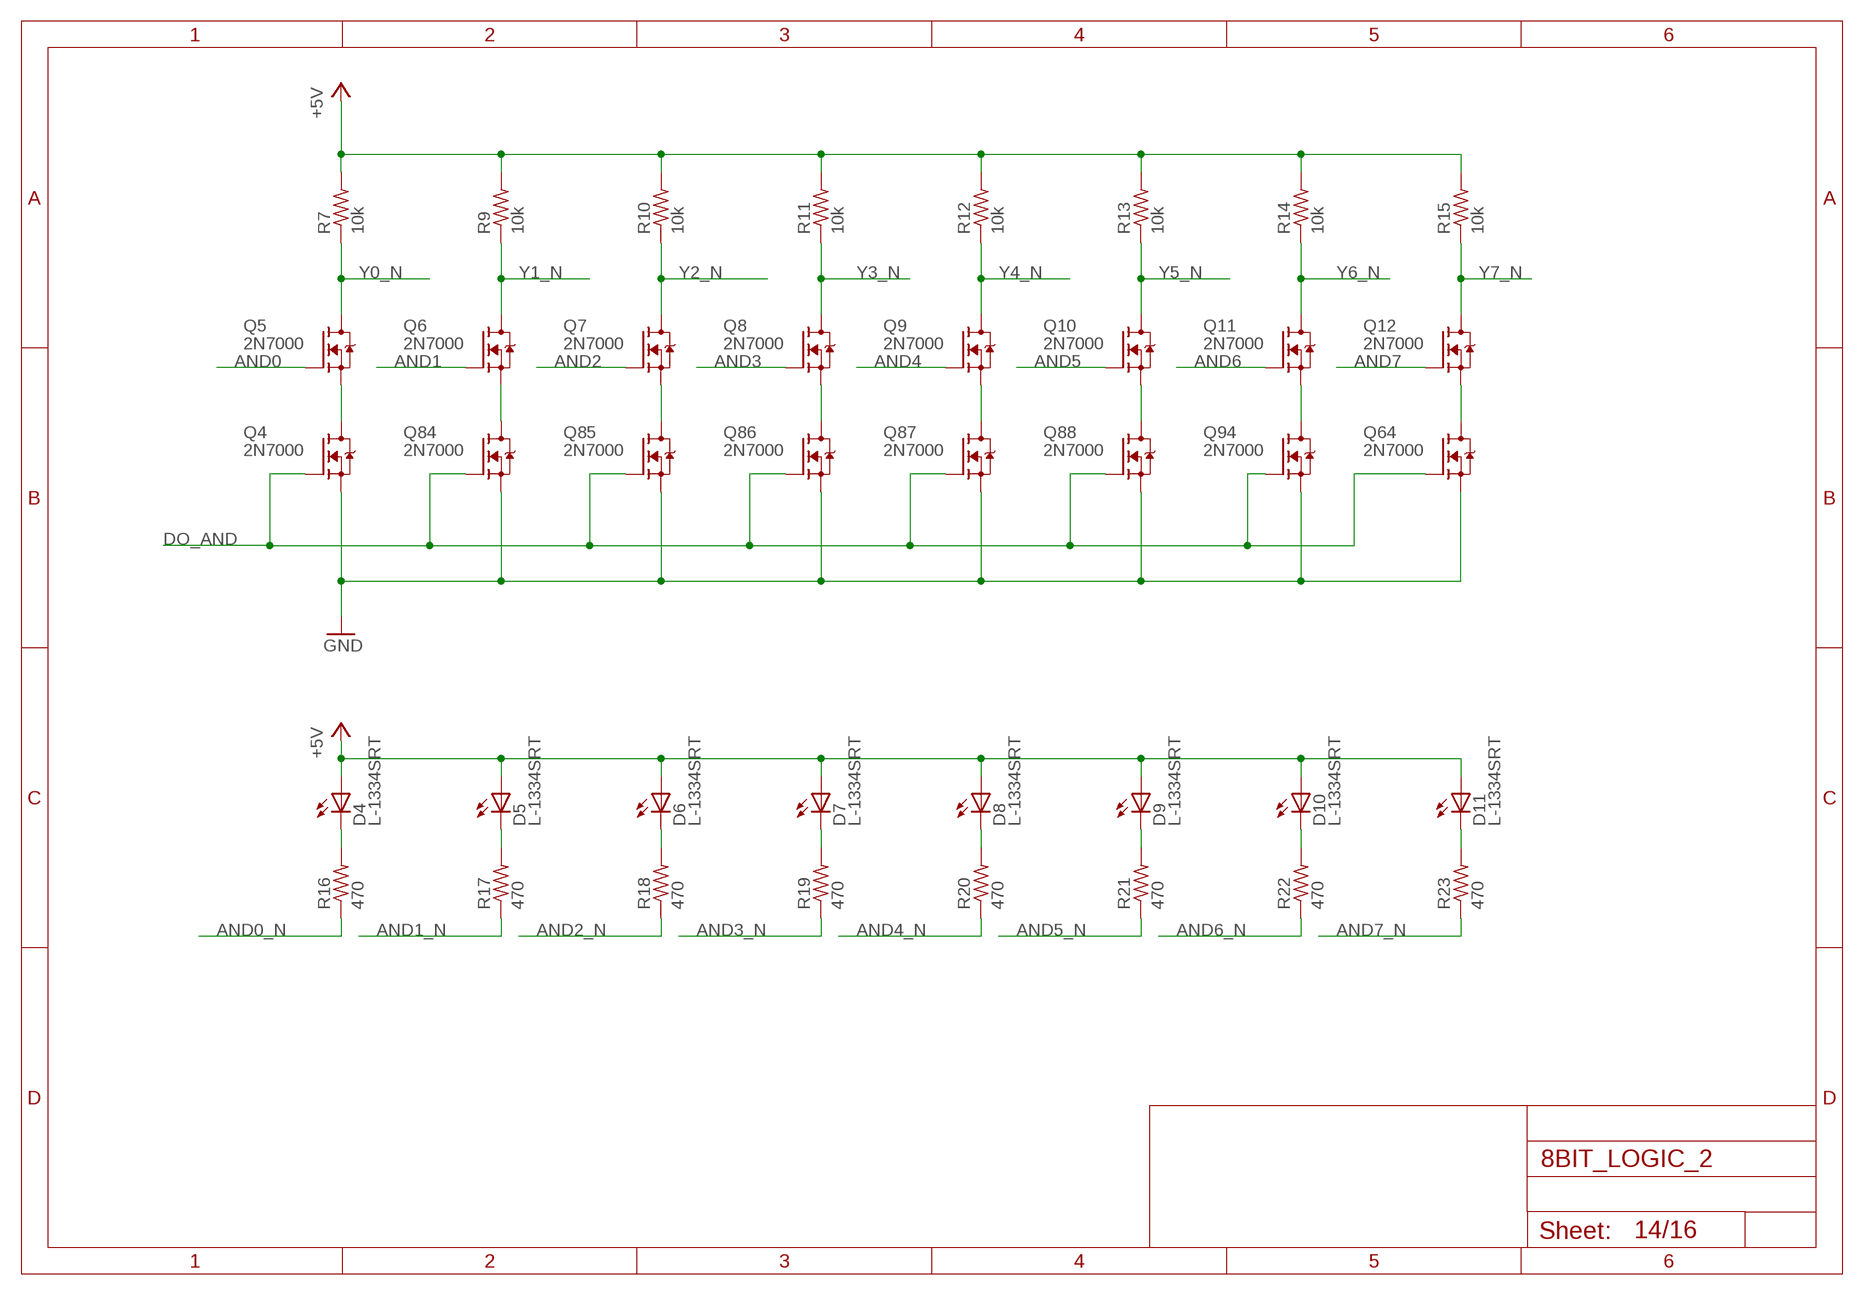
[diagram p13: schematic, sheet 14]
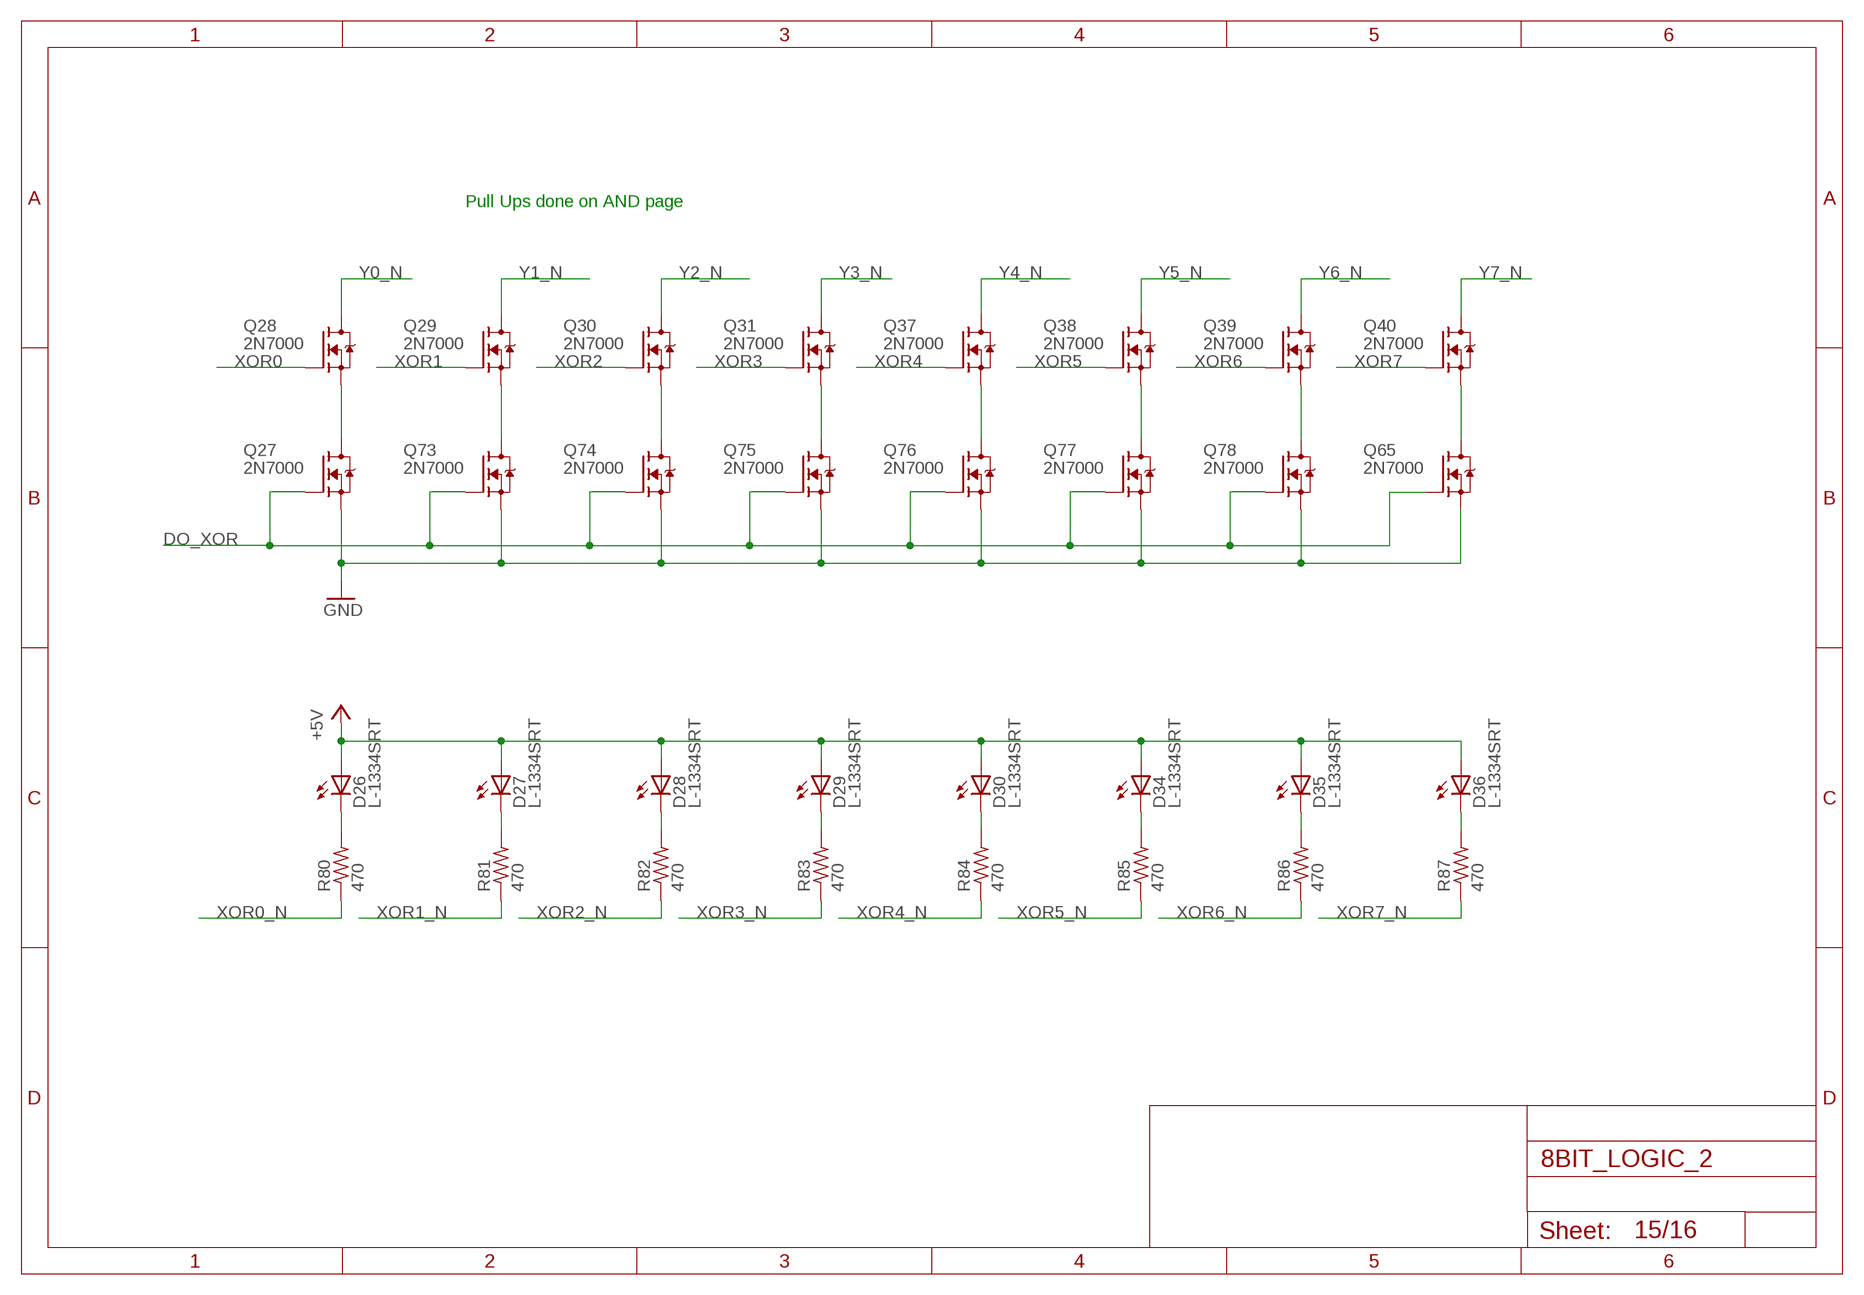
[diagram p14: schematic, sheet 15]
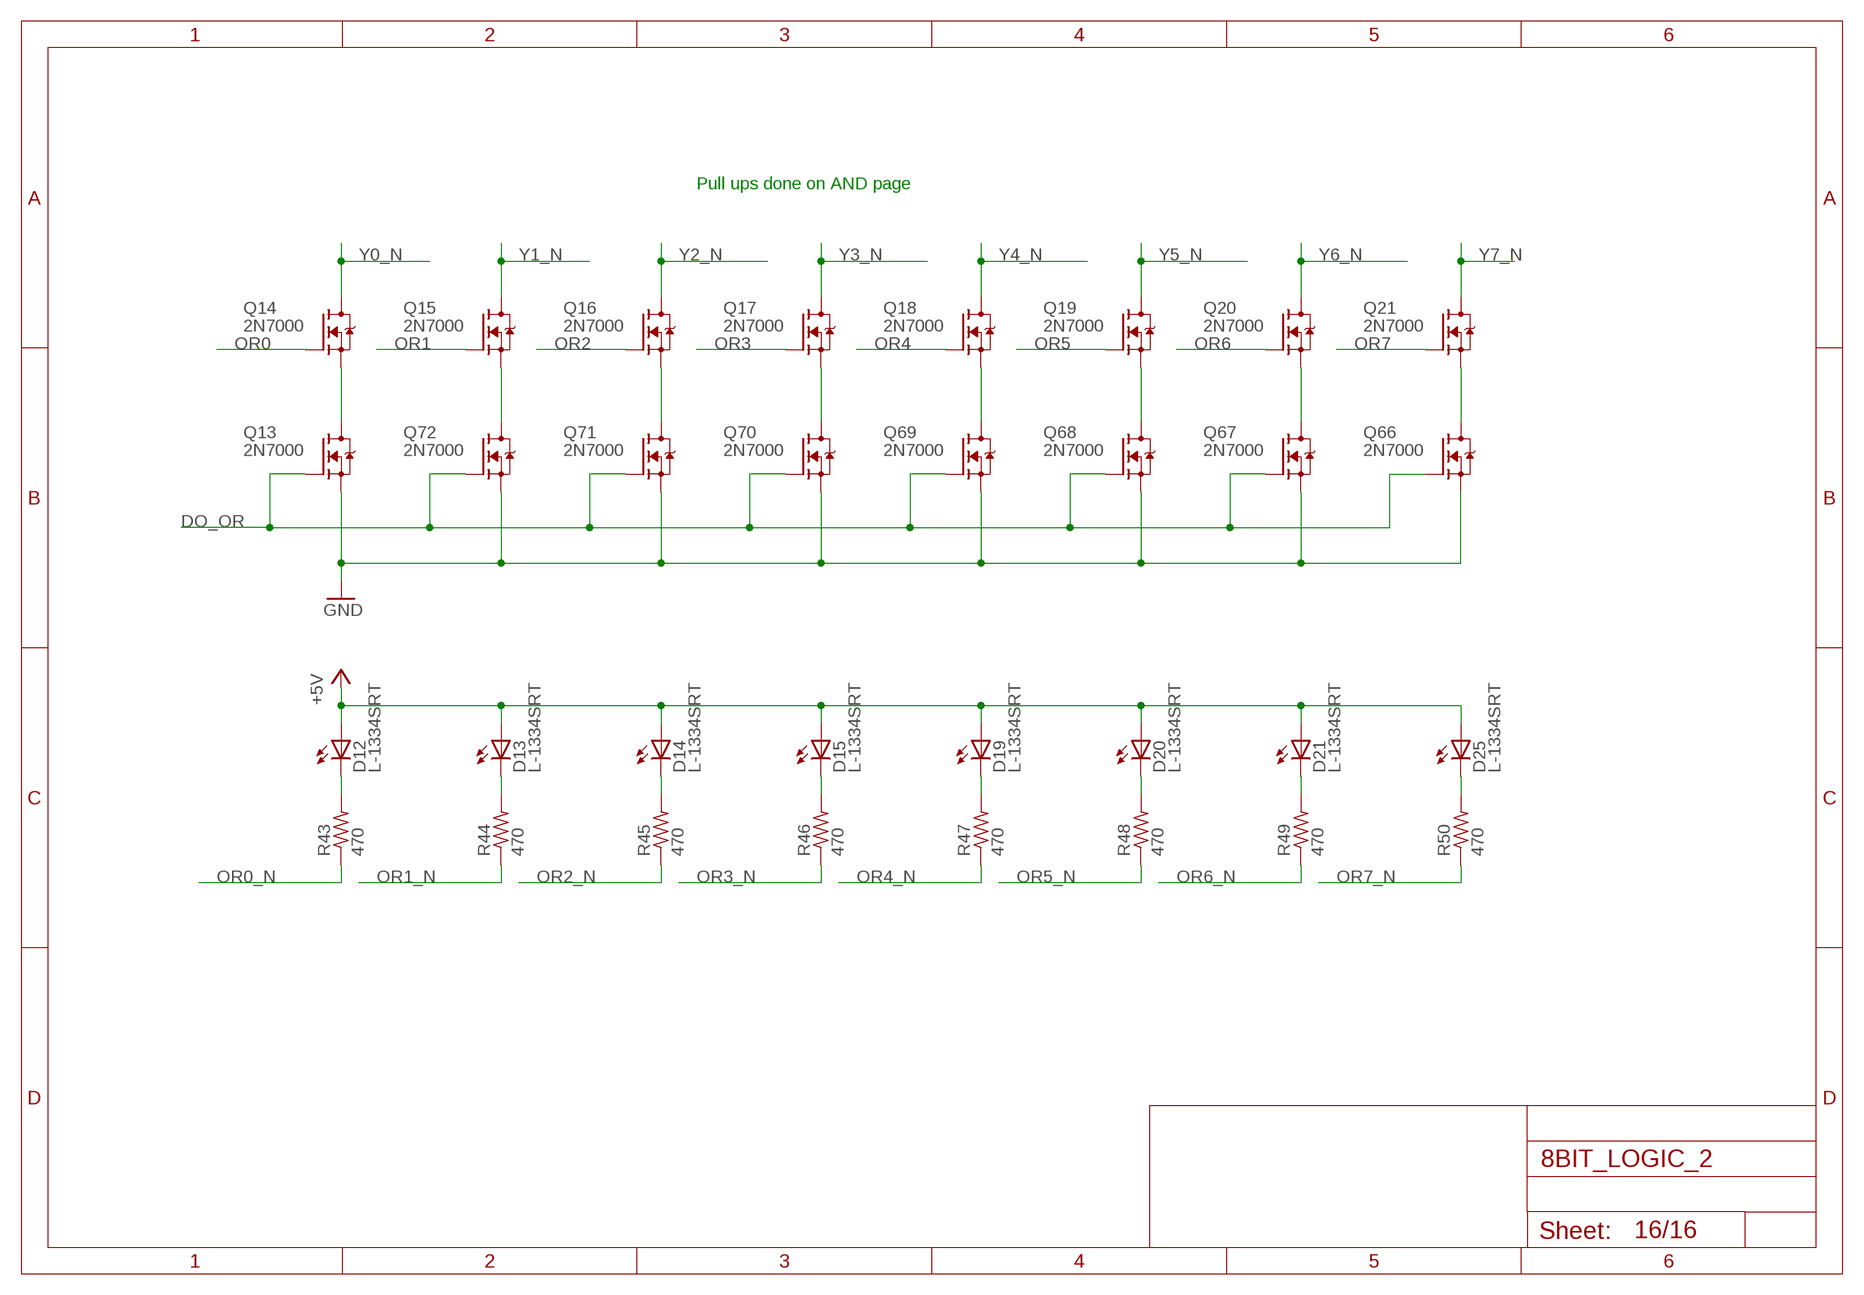
[diagram p15: schematic, sheet 16]

(export (version "E")
  (design (tool "Eeschema 10.0.6"))
  (components
    (comp (ref "D85")
      (value "L-1334SRT")
      (footprint "eagle-import:LED3MM")
      (libsource (lib "eagle-import") (part "L-1334SRT"))
    )
    (comp (ref "D86")
      (value "L-1334SRT")
      (footprint "eagle-import:LED3MM")
      (libsource (lib "eagle-import") (part "L-1334SRT"))
    )
    (comp (ref "D87")
      (value "L-1334SRT")
      (footprint "eagle-import:LED3MM")
      (libsource (lib "eagle-import") (part "L-1334SRT"))
    )
    (comp (ref "D139")
      (value "L-1334SRT")
      (footprint "eagle-import:LED3MM")
      (libsource (lib "eagle-import") (part "L-1334SRT"))
    )
    (comp (ref "D140")
      (value "L-1334SRT")
      (footprint "eagle-import:LED3MM")
      (libsource (lib "eagle-import") (part "L-1334SRT"))
    )
    (comp (ref "D141")
      (value "L-1334SRT")
      (footprint "eagle-import:LED3MM")
      (libsource (lib "eagle-import") (part "L-1334SRT"))
    )
    (comp (ref "D142")
      (value "L-1334SRT")
      (footprint "eagle-import:LED3MM")
      (libsource (lib "eagle-import") (part "L-1334SRT"))
    )
    (comp (ref "D143")
      (value "L-1334SRT")
      (footprint "eagle-import:LED3MM")
      (libsource (lib "eagle-import") (part "L-1334SRT"))
    )
    (comp (ref "D144")
      (value "L-1334SRT")
      (footprint "eagle-import:LED3MM")
      (libsource (lib "eagle-import") (part "L-1334SRT"))
    )
    (comp (ref "Q129")
      (value "2N7000")
      (footprint "eagle-import:TO92-DGS")
      (libsource (lib "eagle-import") (part "2N7000"))
    )
    (comp (ref "Q130")
      (value "2N7000")
      (footprint "eagle-import:TO92-DGS")
      (libsource (lib "eagle-import") (part "2N7000"))
    )
    (comp (ref "Q131")
      (value "2N7000")
      (footprint "eagle-import:TO92-DGS")
      (libsource (lib "eagle-import") (part "2N7000"))
    )
    (comp (ref "Q132")
      (value "2N7000")
      (footprint "eagle-import:TO92-DGS")
      (libsource (lib "eagle-import") (part "2N7000"))
    )
    (comp (ref "Q133")
      (value "2N7000")
      (footprint "eagle-import:TO92-DGS")
      (libsource (lib "eagle-import") (part "2N7000"))
    )
    (comp (ref "Q187")
      (value "2N7000")
      (footprint "eagle-import:TO92-DGS")
      (libsource (lib "eagle-import") (part "2N7000"))
    )
    (comp (ref "Q188")
      (value "2N7000")
      (footprint "eagle-import:TO92-DGS")
      (libsource (lib "eagle-import") (part "2N7000"))
    )
    (comp (ref "Q189")
      (value "2N7000")
      (footprint "eagle-import:TO92-DGS")
      (libsource (lib "eagle-import") (part "2N7000"))
    )
    (comp (ref "Q190")
      (value "2N7000")
      (footprint "eagle-import:TO92-DGS")
      (libsource (lib "eagle-import") (part "2N7000"))
    )
    (comp (ref "Q191")
      (value "2N7000")
      (footprint "eagle-import:TO92-DGS")
      (libsource (lib "eagle-import") (part "2N7000"))
    )
    (comp (ref "Q192")
      (value "2N7000")
      (footprint "eagle-import:TO92-DGS")
      (libsource (lib "eagle-import") (part "2N7000"))
    )
    (comp (ref "R141")
      (value "10k")
      (footprint "eagle-import:R_P2INCH")
      (libsource (lib "eagle-import") (part "R_P2INCH"))
    )
    (comp (ref "R142")
      (value "470")
      (footprint "eagle-import:R_P2INCH")
      (libsource (lib "eagle-import") (part "R_P2INCH"))
    )
    (comp (ref "R143")
      (value "10k")
      (footprint "eagle-import:R_P2INCH")
      (libsource (lib "eagle-import") (part "R_P2INCH"))
    )
    (comp (ref "R144")
      (value "470")
      (footprint "eagle-import:R_P2INCH")
      (libsource (lib "eagle-import") (part "R_P2INCH"))
    )
    (comp (ref "R145")
      (value "470")
      (footprint "eagle-import:R_P2INCH")
      (libsource (lib "eagle-import") (part "R_P2INCH"))
    )
    (comp (ref "R231")
      (value "10k")
      (footprint "eagle-import:R_P2INCH")
      (libsource (lib "eagle-import") (part "R_P2INCH"))
    )
    (comp (ref "R232")
      (value "470")
      (footprint "eagle-import:R_P2INCH")
      (libsource (lib "eagle-import") (part "R_P2INCH"))
    )
    (comp (ref "R233")
      (value "10k")
      (footprint "eagle-import:R_P2INCH")
      (libsource (lib "eagle-import") (part "R_P2INCH"))
    )
    (comp (ref "R234")
      (value "470")
      (footprint "eagle-import:R_P2INCH")
      (libsource (lib "eagle-import") (part "R_P2INCH"))
    )
    (comp (ref "R235")
      (value "470")
      (footprint "eagle-import:R_P2INCH")
      (libsource (lib "eagle-import") (part "R_P2INCH"))
    )
    (comp (ref "R236")
      (value "10k")
      (footprint "eagle-import:R_P2INCH")
      (libsource (lib "eagle-import") (part "R_P2INCH"))
    )
    (comp (ref "R237")
      (value "470")
      (footprint "eagle-import:R_P2INCH")
      (libsource (lib "eagle-import") (part "R_P2INCH"))
    )
    (comp (ref "R238")
      (value "10k")
      (footprint "eagle-import:R_P2INCH")
      (libsource (lib "eagle-import") (part "R_P2INCH"))
    )
    (comp (ref "R239")
      (value "470")
      (footprint "eagle-import:R_P2INCH")
      (libsource (lib "eagle-import") (part "R_P2INCH"))
    )
    (comp (ref "R240")
      (value "470")
      (footprint "eagle-import:R_P2INCH")
      (libsource (lib "eagle-import") (part "R_P2INCH"))
    )
    (comp (ref "D22")
      (value "L-1334SRT")
      (footprint "eagle-import:LED3MM")
      (libsource (lib "eagle-import") (part "L-1334SRT"))
    )
    (comp (ref "D23")
      (value "L-1334SRT")
      (footprint "eagle-import:LED3MM")
      (libsource (lib "eagle-import") (part "L-1334SRT"))
    )
    (comp (ref "D24")
      (value "L-1334SRT")
      (footprint "eagle-import:LED3MM")
      (libsource (lib "eagle-import") (part "L-1334SRT"))
    )
    (comp (ref "D37")
      (value "L-1334SRT")
      (footprint "eagle-import:LED3MM")
      (libsource (lib "eagle-import") (part "L-1334SRT"))
    )
    (comp (ref "D38")
      (value "L-1334SRT")
      (footprint "eagle-import:LED3MM")
      (libsource (lib "eagle-import") (part "L-1334SRT"))
    )
    (comp (ref "D39")
      (value "L-1334SRT")
      (footprint "eagle-import:LED3MM")
      (libsource (lib "eagle-import") (part "L-1334SRT"))
    )
    (comp (ref "D40")
      (value "L-1334SRT")
      (footprint "eagle-import:LED3MM")
      (libsource (lib "eagle-import") (part "L-1334SRT"))
    )
    (comp (ref "D41")
      (value "L-1334SRT")
      (footprint "eagle-import:LED3MM")
      (libsource (lib "eagle-import") (part "L-1334SRT"))
    )
    (comp (ref "D42")
      (value "L-1334SRT")
      (footprint "eagle-import:LED3MM")
      (libsource (lib "eagle-import") (part "L-1334SRT"))
    )
    (comp (ref "Q32")
      (value "2N7000")
      (footprint "eagle-import:TO92-DGS")
      (libsource (lib "eagle-import") (part "2N7000"))
    )
    (comp (ref "Q33")
      (value "2N7000")
      (footprint "eagle-import:TO92-DGS")
      (libsource (lib "eagle-import") (part "2N7000"))
    )
    (comp (ref "Q34")
      (value "2N7000")
      (footprint "eagle-import:TO92-DGS")
      (libsource (lib "eagle-import") (part "2N7000"))
    )
    (comp (ref "Q35")
      (value "2N7000")
      (footprint "eagle-import:TO92-DGS")
      (libsource (lib "eagle-import") (part "2N7000"))
    )
    (comp (ref "Q36")
      (value "2N7000")
      (footprint "eagle-import:TO92-DGS")
      (libsource (lib "eagle-import") (part "2N7000"))
    )
    (comp (ref "Q51")
      (value "2N7000")
      (footprint "eagle-import:TO92-DGS")
      (libsource (lib "eagle-import") (part "2N7000"))
    )
    (comp (ref "Q52")
      (value "2N7000")
      (footprint "eagle-import:TO92-DGS")
      (libsource (lib "eagle-import") (part "2N7000"))
    )
    (comp (ref "Q53")
      (value "2N7000")
      (footprint "eagle-import:TO92-DGS")
      (libsource (lib "eagle-import") (part "2N7000"))
    )
    (comp (ref "Q54")
      (value "2N7000")
      (footprint "eagle-import:TO92-DGS")
      (libsource (lib "eagle-import") (part "2N7000"))
    )
    (comp (ref "Q55")
      (value "2N7000")
      (footprint "eagle-import:TO92-DGS")
      (libsource (lib "eagle-import") (part "2N7000"))
    )
    (comp (ref "Q56")
      (value "2N7000")
      (footprint "eagle-import:TO92-DGS")
      (libsource (lib "eagle-import") (part "2N7000"))
    )
    (comp (ref "R36")
      (value "10k")
      (footprint "eagle-import:R_P2INCH")
      (libsource (lib "eagle-import") (part "R_P2INCH"))
    )
    (comp (ref "R37")
      (value "470")
      (footprint "eagle-import:R_P2INCH")
      (libsource (lib "eagle-import") (part "R_P2INCH"))
    )
    (comp (ref "R38")
      (value "10k")
      (footprint "eagle-import:R_P2INCH")
      (libsource (lib "eagle-import") (part "R_P2INCH"))
    )
    (comp (ref "R39")
      (value "470")
      (footprint "eagle-import:R_P2INCH")
      (libsource (lib "eagle-import") (part "R_P2INCH"))
    )
    (comp (ref "R40")
      (value "470")
      (footprint "eagle-import:R_P2INCH")
      (libsource (lib "eagle-import") (part "R_P2INCH"))
    )
    (comp (ref "R61")
      (value "10k")
      (footprint "eagle-import:R_P2INCH")
      (libsource (lib "eagle-import") (part "R_P2INCH"))
    )
    (comp (ref "R62")
      (value "470")
      (footprint "eagle-import:R_P2INCH")
      (libsource (lib "eagle-import") (part "R_P2INCH"))
    )
    (comp (ref "R63")
      (value "10k")
      (footprint "eagle-import:R_P2INCH")
      (libsource (lib "eagle-import") (part "R_P2INCH"))
    )
    (comp (ref "R64")
      (value "470")
      (footprint "eagle-import:R_P2INCH")
      (libsource (lib "eagle-import") (part "R_P2INCH"))
    )
    (comp (ref "R65")
      (value "470")
      (footprint "eagle-import:R_P2INCH")
      (libsource (lib "eagle-import") (part "R_P2INCH"))
    )
    (comp (ref "R66")
      (value "10k")
      (footprint "eagle-import:R_P2INCH")
      (libsource (lib "eagle-import") (part "R_P2INCH"))
    )
    (comp (ref "R67")
      (value "470")
      (footprint "eagle-import:R_P2INCH")
      (libsource (lib "eagle-import") (part "R_P2INCH"))
    )
    (comp (ref "R68")
      (value "10k")
      (footprint "eagle-import:R_P2INCH")
      (libsource (lib "eagle-import") (part "R_P2INCH"))
    )
    (comp (ref "R69")
      (value "470")
      (footprint "eagle-import:R_P2INCH")
      (libsource (lib "eagle-import") (part "R_P2INCH"))
    )
    (comp (ref "R70")
      (value "470")
      (footprint "eagle-import:R_P2INCH")
      (libsource (lib "eagle-import") (part "R_P2INCH"))
    )
    (comp (ref "D46")
      (value "L-1334SRT")
      (footprint "eagle-import:LED3MM")
      (libsource (lib "eagle-import") (part "L-1334SRT"))
    )
    (comp (ref "D47")
      (value "L-1334SRT")
      (footprint "eagle-import:LED3MM")
      (libsource (lib "eagle-import") (part "L-1334SRT"))
    )
    (comp (ref "D48")
      (value "L-1334SRT")
      (footprint "eagle-import:LED3MM")
      (libsource (lib "eagle-import") (part "L-1334SRT"))
    )
    (comp (ref "D49")
      (value "L-1334SRT")
      (footprint "eagle-import:LED3MM")
      (libsource (lib "eagle-import") (part "L-1334SRT"))
    )
    (comp (ref "D50")
      (value "L-1334SRT")
      (footprint "eagle-import:LED3MM")
      (libsource (lib "eagle-import") (part "L-1334SRT"))
    )
    (comp (ref "D51")
      (value "L-1334SRT")
      (footprint "eagle-import:LED3MM")
      (libsource (lib "eagle-import") (part "L-1334SRT"))
    )
    (comp (ref "D52")
      (value "L-1334SRT")
      (footprint "eagle-import:LED3MM")
      (libsource (lib "eagle-import") (part "L-1334SRT"))
    )
    (comp (ref "D53")
      (value "L-1334SRT")
      (footprint "eagle-import:LED3MM")
      (libsource (lib "eagle-import") (part "L-1334SRT"))
    )
    (comp (ref "D163")
      (value "L-1334SRT")
      (footprint "eagle-import:LED3MM")
      (libsource (lib "eagle-import") (part "L-1334SRT"))
    )
    (comp (ref "D164")
      (value "L-1334SRT")
      (footprint "eagle-import:LED3MM")
      (libsource (lib "eagle-import") (part "L-1334SRT"))
    )
    (comp (ref "D165")
      (value "L-1334SRT")
      (footprint "eagle-import:LED3MM")
      (libsource (lib "eagle-import") (part "L-1334SRT"))
    )
    (comp (ref "D166")
      (value "L-1334SRT")
      (footprint "eagle-import:LED3MM")
      (libsource (lib "eagle-import") (part "L-1334SRT"))
    )
    (comp (ref "D167")
      (value "L-1334SRT")
      (footprint "eagle-import:LED3MM")
      (libsource (lib "eagle-import") (part "L-1334SRT"))
    )
    (comp (ref "D168")
      (value "L-1334SRT")
      (footprint "eagle-import:LED3MM")
      (libsource (lib "eagle-import") (part "L-1334SRT"))
    )
    (comp (ref "D169")
      (value "L-1334SRT")
      (footprint "eagle-import:LED3MM")
      (libsource (lib "eagle-import") (part "L-1334SRT"))
    )
    (comp (ref "D170")
      (value "L-1334SRT")
      (footprint "eagle-import:LED3MM")
      (libsource (lib "eagle-import") (part "L-1334SRT"))
    )
    (comp (ref "Q41")
      (value "2N7000")
      (footprint "eagle-import:TO92-DGS")
      (libsource (lib "eagle-import") (part "2N7000"))
    )
    (comp (ref "Q42")
      (value "2N7000")
      (footprint "eagle-import:TO92-DGS")
      (libsource (lib "eagle-import") (part "2N7000"))
    )
    (comp (ref "Q43")
      (value "2N7000")
      (footprint "eagle-import:TO92-DGS")
      (libsource (lib "eagle-import") (part "2N7000"))
    )
    (comp (ref "Q44")
      (value "2N7000")
      (footprint "eagle-import:TO92-DGS")
      (libsource (lib "eagle-import") (part "2N7000"))
    )
    (comp (ref "Q48")
      (value "2N7000")
      (footprint "eagle-import:TO92-DGS")
      (libsource (lib "eagle-import") (part "2N7000"))
    )
    (comp (ref "Q49")
      (value "2N7000")
      (footprint "eagle-import:TO92-DGS")
      (libsource (lib "eagle-import") (part "2N7000"))
    )
    (comp (ref "Q50")
      (value "2N7000")
      (footprint "eagle-import:TO92-DGS")
      (libsource (lib "eagle-import") (part "2N7000"))
    )
    (comp (ref "Q60")
      (value "2N7000")
      (footprint "eagle-import:TO92-DGS")
      (libsource (lib "eagle-import") (part "2N7000"))
    )
    (comp (ref "R88")
      (value "470")
      (footprint "eagle-import:R_P2INCH")
      (libsource (lib "eagle-import") (part "R_P2INCH"))
    )
    (comp (ref "R89")
      (value "10k")
      (footprint "eagle-import:R_P2INCH")
      (libsource (lib "eagle-import") (part "R_P2INCH"))
    )
    (comp (ref "R90")
      (value "470")
      (footprint "eagle-import:R_P2INCH")
      (libsource (lib "eagle-import") (part "R_P2INCH"))
    )
    (comp (ref "R96")
      (value "10k")
      (footprint "eagle-import:R_P2INCH")
      (libsource (lib "eagle-import") (part "R_P2INCH"))
    )
    (comp (ref "R97")
      (value "470")
      (footprint "eagle-import:R_P2INCH")
      (libsource (lib "eagle-import") (part "R_P2INCH"))
    )
    (comp (ref "R98")
      (value "10k")
      (footprint "eagle-import:R_P2INCH")
      (libsource (lib "eagle-import") (part "R_P2INCH"))
    )
    (comp (ref "R99")
      (value "470")
      (footprint "eagle-import:R_P2INCH")
      (libsource (lib "eagle-import") (part "R_P2INCH"))
    )
    (comp (ref "R100")
      (value "10k")
      (footprint "eagle-import:R_P2INCH")
      (libsource (lib "eagle-import") (part "R_P2INCH"))
    )
    (comp (ref "R106")
      (value "470")
      (footprint "eagle-import:R_P2INCH")
      (libsource (lib "eagle-import") (part "R_P2INCH"))
    )
    (comp (ref "R107")
      (value "10k")
      (footprint "eagle-import:R_P2INCH")
      (libsource (lib "eagle-import") (part "R_P2INCH"))
    )
    (comp (ref "R108")
      (value "470")
      (footprint "eagle-import:R_P2INCH")
      (libsource (lib "eagle-import") (part "R_P2INCH"))
    )
    (comp (ref "R109")
      (value "10k")
      (footprint "eagle-import:R_P2INCH")
      (libsource (lib "eagle-import") (part "R_P2INCH"))
    )
    (comp (ref "R110")
      (value "470")
      (footprint "eagle-import:R_P2INCH")
      (libsource (lib "eagle-import") (part "R_P2INCH"))
    )
    (comp (ref "R116")
      (value "10k")
      (footprint "eagle-import:R_P2INCH")
      (libsource (lib "eagle-import") (part "R_P2INCH"))
    )
    (comp (ref "R117")
      (value "470")
      (footprint "eagle-import:R_P2INCH")
      (libsource (lib "eagle-import") (part "R_P2INCH"))
    )
    (comp (ref "R118")
      (value "10k")
      (footprint "eagle-import:R_P2INCH")
      (libsource (lib "eagle-import") (part "R_P2INCH"))
    )
    (comp (ref "R277")
      (value "470")
      (footprint "eagle-import:R_P2INCH")
      (libsource (lib "eagle-import") (part "R_P2INCH"))
    )
    (comp (ref "R278")
      (value "470")
      (footprint "eagle-import:R_P2INCH")
      (libsource (lib "eagle-import") (part "R_P2INCH"))
    )
    (comp (ref "R279")
      (value "470")
      (footprint "eagle-import:R_P2INCH")
      (libsource (lib "eagle-import") (part "R_P2INCH"))
    )
    (comp (ref "R280")
      (value "470")
      (footprint "eagle-import:R_P2INCH")
      (libsource (lib "eagle-import") (part "R_P2INCH"))
    )
    (comp (ref "R281")
      (value "470")
      (footprint "eagle-import:R_P2INCH")
      (libsource (lib "eagle-import") (part "R_P2INCH"))
    )
    (comp (ref "R282")
      (value "470")
      (footprint "eagle-import:R_P2INCH")
      (libsource (lib "eagle-import") (part "R_P2INCH"))
    )
    (comp (ref "R283")
      (value "470")
      (footprint "eagle-import:R_P2INCH")
      (libsource (lib "eagle-import") (part "R_P2INCH"))
    )
    (comp (ref "R284")
      (value "470")
      (footprint "eagle-import:R_P2INCH")
      (libsource (lib "eagle-import") (part "R_P2INCH"))
    )
    (comp (ref "D4")
      (value "L-1334SRT")
      (footprint "eagle-import:LED3MM")
      (libsource (lib "eagle-import") (part "L-1334SRT"))
    )
    (comp (ref "D5")
      (value "L-1334SRT")
      (footprint "eagle-import:LED3MM")
      (libsource (lib "eagle-import") (part "L-1334SRT"))
    )
    (comp (ref "D6")
      (value "L-1334SRT")
      (footprint "eagle-import:LED3MM")
      (libsource (lib "eagle-import") (part "L-1334SRT"))
    )
    (comp (ref "D7")
      (value "L-1334SRT")
      (footprint "eagle-import:LED3MM")
      (libsource (lib "eagle-import") (part "L-1334SRT"))
    )
    (comp (ref "D8")
      (value "L-1334SRT")
      (footprint "eagle-import:LED3MM")
      (libsource (lib "eagle-import") (part "L-1334SRT"))
    )
    (comp (ref "D9")
      (value "L-1334SRT")
      (footprint "eagle-import:LED3MM")
      (libsource (lib "eagle-import") (part "L-1334SRT"))
    )
    (comp (ref "D10")
      (value "L-1334SRT")
      (footprint "eagle-import:LED3MM")
      (libsource (lib "eagle-import") (part "L-1334SRT"))
    )
    (comp (ref "D11")
      (value "L-1334SRT")
      (footprint "eagle-import:LED3MM")
      (libsource (lib "eagle-import") (part "L-1334SRT"))
    )
    (comp (ref "Q4")
      (value "2N7000")
      (footprint "eagle-import:TO92-DGS")
      (libsource (lib "eagle-import") (part "2N7000"))
    )
    (comp (ref "Q5")
      (value "2N7000")
      (footprint "eagle-import:TO92-DGS")
      (libsource (lib "eagle-import") (part "2N7000"))
    )
    (comp (ref "Q6")
      (value "2N7000")
      (footprint "eagle-import:TO92-DGS")
      (libsource (lib "eagle-import") (part "2N7000"))
    )
    (comp (ref "Q7")
      (value "2N7000")
      (footprint "eagle-import:TO92-DGS")
      (libsource (lib "eagle-import") (part "2N7000"))
    )
    (comp (ref "Q8")
      (value "2N7000")
      (footprint "eagle-import:TO92-DGS")
      (libsource (lib "eagle-import") (part "2N7000"))
    )
    (comp (ref "Q9")
      (value "2N7000")
      (footprint "eagle-import:TO92-DGS")
      (libsource (lib "eagle-import") (part "2N7000"))
    )
    (comp (ref "Q10")
      (value "2N7000")
      (footprint "eagle-import:TO92-DGS")
      (libsource (lib "eagle-import") (part "2N7000"))
    )
    (comp (ref "Q11")
      (value "2N7000")
      (footprint "eagle-import:TO92-DGS")
      (libsource (lib "eagle-import") (part "2N7000"))
    )
    (comp (ref "Q12")
      (value "2N7000")
      (footprint "eagle-import:TO92-DGS")
      (libsource (lib "eagle-import") (part "2N7000"))
    )
    (comp (ref "Q64")
      (value "2N7000")
      (footprint "eagle-import:TO92-DGS")
      (libsource (lib "eagle-import") (part "2N7000"))
    )
    (comp (ref "Q84")
      (value "2N7000")
      (footprint "eagle-import:TO92-DGS")
      (libsource (lib "eagle-import") (part "2N7000"))
    )
    (comp (ref "Q85")
      (value "2N7000")
      (footprint "eagle-import:TO92-DGS")
      (libsource (lib "eagle-import") (part "2N7000"))
    )
    (comp (ref "Q86")
      (value "2N7000")
      (footprint "eagle-import:TO92-DGS")
      (libsource (lib "eagle-import") (part "2N7000"))
    )
    (comp (ref "Q87")
      (value "2N7000")
      (footprint "eagle-import:TO92-DGS")
      (libsource (lib "eagle-import") (part "2N7000"))
    )
    (comp (ref "Q88")
      (value "2N7000")
      (footprint "eagle-import:TO92-DGS")
      (libsource (lib "eagle-import") (part "2N7000"))
    )
    (comp (ref "Q94")
      (value "2N7000")
      (footprint "eagle-import:TO92-DGS")
      (libsource (lib "eagle-import") (part "2N7000"))
    )
    (comp (ref "R7")
      (value "10k")
      (footprint "eagle-import:R_P2INCH")
      (libsource (lib "eagle-import") (part "R_P2INCH"))
    )
    (comp (ref "R9")
      (value "10k")
      (footprint "eagle-import:R_P2INCH")
      (libsource (lib "eagle-import") (part "R_P2INCH"))
    )
    (comp (ref "R10")
      (value "10k")
      (footprint "eagle-import:R_P2INCH")
      (libsource (lib "eagle-import") (part "R_P2INCH"))
    )
    (comp (ref "R11")
      (value "10k")
      (footprint "eagle-import:R_P2INCH")
      (libsource (lib "eagle-import") (part "R_P2INCH"))
    )
    (comp (ref "R12")
      (value "10k")
      (footprint "eagle-import:R_P2INCH")
      (libsource (lib "eagle-import") (part "R_P2INCH"))
    )
    (comp (ref "R13")
      (value "10k")
      (footprint "eagle-import:R_P2INCH")
      (libsource (lib "eagle-import") (part "R_P2INCH"))
    )
    (comp (ref "R14")
      (value "10k")
      (footprint "eagle-import:R_P2INCH")
      (libsource (lib "eagle-import") (part "R_P2INCH"))
    )
    (comp (ref "R15")
      (value "10k")
      (footprint "eagle-import:R_P2INCH")
      (libsource (lib "eagle-import") (part "R_P2INCH"))
    )
    (comp (ref "R16")
      (value "470")
      (footprint "eagle-import:R_P2INCH")
      (libsource (lib "eagle-import") (part "R_P2INCH"))
    )
    (comp (ref "R17")
      (value "470")
      (footprint "eagle-import:R_P2INCH")
      (libsource (lib "eagle-import") (part "R_P2INCH"))
    )
    (comp (ref "R18")
      (value "470")
      (footprint "eagle-import:R_P2INCH")
      (libsource (lib "eagle-import") (part "R_P2INCH"))
    )
    (comp (ref "R19")
      (value "470")
      (footprint "eagle-import:R_P2INCH")
      (libsource (lib "eagle-import") (part "R_P2INCH"))
    )
    (comp (ref "R20")
      (value "470")
      (footprint "eagle-import:R_P2INCH")
      (libsource (lib "eagle-import") (part "R_P2INCH"))
    )
    (comp (ref "R21")
      (value "470")
      (footprint "eagle-import:R_P2INCH")
      (libsource (lib "eagle-import") (part "R_P2INCH"))
    )
    (comp (ref "R22")
      (value "470")
      (footprint "eagle-import:R_P2INCH")
      (libsource (lib "eagle-import") (part "R_P2INCH"))
    )
    (comp (ref "R23")
      (value "470")
      (footprint "eagle-import:R_P2INCH")
      (libsource (lib "eagle-import") (part "R_P2INCH"))
    )
    (comp (ref "D26")
      (value "L-1334SRT")
      (footprint "eagle-import:LED3MM")
      (libsource (lib "eagle-import") (part "L-1334SRT"))
    )
    (comp (ref "D27")
      (value "L-1334SRT")
      (footprint "eagle-import:LED3MM")
      (libsource (lib "eagle-import") (part "L-1334SRT"))
    )
    (comp (ref "D28")
      (value "L-1334SRT")
      (footprint "eagle-import:LED3MM")
      (libsource (lib "eagle-import") (part "L-1334SRT"))
    )
    (comp (ref "D29")
      (value "L-1334SRT")
      (footprint "eagle-import:LED3MM")
      (libsource (lib "eagle-import") (part "L-1334SRT"))
    )
    (comp (ref "D30")
      (value "L-1334SRT")
      (footprint "eagle-import:LED3MM")
      (libsource (lib "eagle-import") (part "L-1334SRT"))
    )
    (comp (ref "D34")
      (value "L-1334SRT")
      (footprint "eagle-import:LED3MM")
      (libsource (lib "eagle-import") (part "L-1334SRT"))
    )
    (comp (ref "D35")
      (value "L-1334SRT")
      (footprint "eagle-import:LED3MM")
      (libsource (lib "eagle-import") (part "L-1334SRT"))
    )
    (comp (ref "D36")
      (value "L-1334SRT")
      (footprint "eagle-import:LED3MM")
      (libsource (lib "eagle-import") (part "L-1334SRT"))
    )
    (comp (ref "Q27")
      (value "2N7000")
      (footprint "eagle-import:TO92-DGS")
      (libsource (lib "eagle-import") (part "2N7000"))
    )
    (comp (ref "Q28")
      (value "2N7000")
      (footprint "eagle-import:TO92-DGS")
      (libsource (lib "eagle-import") (part "2N7000"))
    )
    (comp (ref "Q29")
      (value "2N7000")
      (footprint "eagle-import:TO92-DGS")
      (libsource (lib "eagle-import") (part "2N7000"))
    )
    (comp (ref "Q30")
      (value "2N7000")
      (footprint "eagle-import:TO92-DGS")
      (libsource (lib "eagle-import") (part "2N7000"))
    )
    (comp (ref "Q31")
      (value "2N7000")
      (footprint "eagle-import:TO92-DGS")
      (libsource (lib "eagle-import") (part "2N7000"))
    )
    (comp (ref "Q37")
      (value "2N7000")
      (footprint "eagle-import:TO92-DGS")
      (libsource (lib "eagle-import") (part "2N7000"))
    )
    (comp (ref "Q38")
      (value "2N7000")
      (footprint "eagle-import:TO92-DGS")
      (libsource (lib "eagle-import") (part "2N7000"))
    )
    (comp (ref "Q39")
      (value "2N7000")
      (footprint "eagle-import:TO92-DGS")
      (libsource (lib "eagle-import") (part "2N7000"))
    )
    (comp (ref "Q40")
      (value "2N7000")
      (footprint "eagle-import:TO92-DGS")
      (libsource (lib "eagle-import") (part "2N7000"))
    )
    (comp (ref "Q65")
      (value "2N7000")
      (footprint "eagle-import:TO92-DGS")
      (libsource (lib "eagle-import") (part "2N7000"))
    )
    (comp (ref "Q73")
      (value "2N7000")
      (footprint "eagle-import:TO92-DGS")
      (libsource (lib "eagle-import") (part "2N7000"))
    )
    (comp (ref "Q74")
      (value "2N7000")
      (footprint "eagle-import:TO92-DGS")
      (libsource (lib "eagle-import") (part "2N7000"))
    )
    (comp (ref "Q75")
      (value "2N7000")
      (footprint "eagle-import:TO92-DGS")
      (libsource (lib "eagle-import") (part "2N7000"))
    )
    (comp (ref "Q76")
      (value "2N7000")
      (footprint "eagle-import:TO92-DGS")
      (libsource (lib "eagle-import") (part "2N7000"))
    )
    (comp (ref "Q77")
      (value "2N7000")
      (footprint "eagle-import:TO92-DGS")
      (libsource (lib "eagle-import") (part "2N7000"))
    )
    (comp (ref "Q78")
      (value "2N7000")
      (footprint "eagle-import:TO92-DGS")
      (libsource (lib "eagle-import") (part "2N7000"))
    )
    (comp (ref "R80")
      (value "470")
      (footprint "eagle-import:R_P2INCH")
      (libsource (lib "eagle-import") (part "R_P2INCH"))
    )
    (comp (ref "R81")
      (value "470")
      (footprint "eagle-import:R_P2INCH")
      (libsource (lib "eagle-import") (part "R_P2INCH"))
    )
    (comp (ref "R82")
      (value "470")
      (footprint "eagle-import:R_P2INCH")
      (libsource (lib "eagle-import") (part "R_P2INCH"))
    )
    (comp (ref "R83")
      (value "470")
      (footprint "eagle-import:R_P2INCH")
      (libsource (lib "eagle-import") (part "R_P2INCH"))
    )
    (comp (ref "R84")
      (value "470")
      (footprint "eagle-import:R_P2INCH")
      (libsource (lib "eagle-import") (part "R_P2INCH"))
    )
    (comp (ref "R85")
      (value "470")
      (footprint "eagle-import:R_P2INCH")
      (libsource (lib "eagle-import") (part "R_P2INCH"))
    )
    (comp (ref "R86")
      (value "470")
      (footprint "eagle-import:R_P2INCH")
      (libsource (lib "eagle-import") (part "R_P2INCH"))
    )
    (comp (ref "R87")
      (value "470")
      (footprint "eagle-import:R_P2INCH")
      (libsource (lib "eagle-import") (part "R_P2INCH"))
    )
    (comp (ref "D73")
      (value "L-1334SRT")
      (footprint "eagle-import:LED3MM")
      (libsource (lib "eagle-import") (part "L-1334SRT"))
    )
    (comp (ref "D74")
      (value "L-1334SRT")
      (footprint "eagle-import:LED3MM")
      (libsource (lib "eagle-import") (part "L-1334SRT"))
    )
    (comp (ref "D75")
      (value "L-1334SRT")
      (footprint "eagle-import:LED3MM")
      (libsource (lib "eagle-import") (part "L-1334SRT"))
    )
    (comp (ref "D121")
      (value "L-1334SRT")
      (footprint "eagle-import:LED3MM")
      (libsource (lib "eagle-import") (part "L-1334SRT"))
    )
    (comp (ref "D122")
      (value "L-1334SRT")
      (footprint "eagle-import:LED3MM")
      (libsource (lib "eagle-import") (part "L-1334SRT"))
    )
    (comp (ref "D123")
      (value "L-1334SRT")
      (footprint "eagle-import:LED3MM")
      (libsource (lib "eagle-import") (part "L-1334SRT"))
    )
    (comp (ref "D124")
      (value "L-1334SRT")
      (footprint "eagle-import:LED3MM")
      (libsource (lib "eagle-import") (part "L-1334SRT"))
    )
    (comp (ref "D125")
      (value "L-1334SRT")
      (footprint "eagle-import:LED3MM")
      (libsource (lib "eagle-import") (part "L-1334SRT"))
    )
    (comp (ref "D126")
      (value "L-1334SRT")
      (footprint "eagle-import:LED3MM")
      (libsource (lib "eagle-import") (part "L-1334SRT"))
    )
    (comp (ref "Q109")
      (value "2N7000")
      (footprint "eagle-import:TO92-DGS")
      (libsource (lib "eagle-import") (part "2N7000"))
    )
    (comp (ref "Q110")
      (value "2N7000")
      (footprint "eagle-import:TO92-DGS")
      (libsource (lib "eagle-import") (part "2N7000"))
    )
    (comp (ref "Q111")
      (value "2N7000")
      (footprint "eagle-import:TO92-DGS")
      (libsource (lib "eagle-import") (part "2N7000"))
    )
    (comp (ref "Q112")
      (value "2N7000")
      (footprint "eagle-import:TO92-DGS")
      (libsource (lib "eagle-import") (part "2N7000"))
    )
    (comp (ref "Q113")
      (value "2N7000")
      (footprint "eagle-import:TO92-DGS")
      (libsource (lib "eagle-import") (part "2N7000"))
    )
    (comp (ref "Q169")
      (value "2N7000")
      (footprint "eagle-import:TO92-DGS")
      (libsource (lib "eagle-import") (part "2N7000"))
    )
    (comp (ref "Q170")
      (value "2N7000")
      (footprint "eagle-import:TO92-DGS")
      (libsource (lib "eagle-import") (part "2N7000"))
    )
    (comp (ref "Q171")
      (value "2N7000")
      (footprint "eagle-import:TO92-DGS")
      (libsource (lib "eagle-import") (part "2N7000"))
    )
    (comp (ref "Q172")
      (value "2N7000")
      (footprint "eagle-import:TO92-DGS")
      (libsource (lib "eagle-import") (part "2N7000"))
    )
    (comp (ref "Q173")
      (value "2N7000")
      (footprint "eagle-import:TO92-DGS")
      (libsource (lib "eagle-import") (part "2N7000"))
    )
    (comp (ref "Q174")
      (value "2N7000")
      (footprint "eagle-import:TO92-DGS")
      (libsource (lib "eagle-import") (part "2N7000"))
    )
    (comp (ref "R121")
      (value "10k")
      (footprint "eagle-import:R_P2INCH")
      (libsource (lib "eagle-import") (part "R_P2INCH"))
    )
    (comp (ref "R122")
      (value "470")
      (footprint "eagle-import:R_P2INCH")
      (libsource (lib "eagle-import") (part "R_P2INCH"))
    )
    (comp (ref "R123")
      (value "10k")
      (footprint "eagle-import:R_P2INCH")
      (libsource (lib "eagle-import") (part "R_P2INCH"))
    )
    (comp (ref "R124")
      (value "470")
      (footprint "eagle-import:R_P2INCH")
      (libsource (lib "eagle-import") (part "R_P2INCH"))
    )
    (comp (ref "R125")
      (value "470")
      (footprint "eagle-import:R_P2INCH")
      (libsource (lib "eagle-import") (part "R_P2INCH"))
    )
    (comp (ref "R201")
      (value "10k")
      (footprint "eagle-import:R_P2INCH")
      (libsource (lib "eagle-import") (part "R_P2INCH"))
    )
    (comp (ref "R202")
      (value "470")
      (footprint "eagle-import:R_P2INCH")
      (libsource (lib "eagle-import") (part "R_P2INCH"))
    )
    (comp (ref "R203")
      (value "10k")
      (footprint "eagle-import:R_P2INCH")
      (libsource (lib "eagle-import") (part "R_P2INCH"))
    )
    (comp (ref "R204")
      (value "470")
      (footprint "eagle-import:R_P2INCH")
      (libsource (lib "eagle-import") (part "R_P2INCH"))
    )
    (comp (ref "R205")
      (value "470")
      (footprint "eagle-import:R_P2INCH")
      (libsource (lib "eagle-import") (part "R_P2INCH"))
    )
    (comp (ref "R206")
      (value "10k")
      (footprint "eagle-import:R_P2INCH")
      (libsource (lib "eagle-import") (part "R_P2INCH"))
    )
    (comp (ref "R207")
      (value "470")
      (footprint "eagle-import:R_P2INCH")
      (libsource (lib "eagle-import") (part "R_P2INCH"))
    )
    (comp (ref "R208")
      (value "10k")
      (footprint "eagle-import:R_P2INCH")
      (libsource (lib "eagle-import") (part "R_P2INCH"))
    )
    (comp (ref "R209")
      (value "470")
      (footprint "eagle-import:R_P2INCH")
      (libsource (lib "eagle-import") (part "R_P2INCH"))
    )
    (comp (ref "R210")
      (value "470")
      (footprint "eagle-import:R_P2INCH")
      (libsource (lib "eagle-import") (part "R_P2INCH"))
    )
    (comp (ref "J4")
      (value "30_HDR_LOCKING_RA")
      (footprint "eagle-import:30_HDR_LOCKING_RA")
      (libsource (lib "eagle-import") (part "30_HDR_LOCKING_RA"))
    )
    (comp (ref "D145")
      (value "L-1334SRT")
      (footprint "eagle-import:LED3MM")
      (libsource (lib "eagle-import") (part "L-1334SRT"))
    )
    (comp (ref "D146")
      (value "L-1334SRT")
      (footprint "eagle-import:LED3MM")
      (libsource (lib "eagle-import") (part "L-1334SRT"))
    )
    (comp (ref "D147")
      (value "L-1334SRT")
      (footprint "eagle-import:LED3MM")
      (libsource (lib "eagle-import") (part "L-1334SRT"))
    )
    (comp (ref "D148")
      (value "L-1334SRT")
      (footprint "eagle-import:LED3MM")
      (libsource (lib "eagle-import") (part "L-1334SRT"))
    )
    (comp (ref "D149")
      (value "L-1334SRT")
      (footprint "eagle-import:LED3MM")
      (libsource (lib "eagle-import") (part "L-1334SRT"))
    )
    (comp (ref "D150")
      (value "L-1334SRT")
      (footprint "eagle-import:LED3MM")
      (libsource (lib "eagle-import") (part "L-1334SRT"))
    )
    (comp (ref "D151")
      (value "L-1334SRT")
      (footprint "eagle-import:LED3MM")
      (libsource (lib "eagle-import") (part "L-1334SRT"))
    )
    (comp (ref "D152")
      (value "L-1334SRT")
      (footprint "eagle-import:LED3MM")
      (libsource (lib "eagle-import") (part "L-1334SRT"))
    )
    (comp (ref "D153")
      (value "L-1334SRT")
      (footprint "eagle-import:LED3MM")
      (libsource (lib "eagle-import") (part "L-1334SRT"))
    )
    (comp (ref "D155")
      (value "L-1334SRT")
      (footprint "eagle-import:LED3MM")
      (libsource (lib "eagle-import") (part "L-1334SRT"))
    )
    (comp (ref "D156")
      (value "L-1334SRT")
      (footprint "eagle-import:LED3MM")
      (libsource (lib "eagle-import") (part "L-1334SRT"))
    )
    (comp (ref "D157")
      (value "L-1334SRT")
      (footprint "eagle-import:LED3MM")
      (libsource (lib "eagle-import") (part "L-1334SRT"))
    )
    (comp (ref "D158")
      (value "L-1334SRT")
      (footprint "eagle-import:LED3MM")
      (libsource (lib "eagle-import") (part "L-1334SRT"))
    )
    (comp (ref "D159")
      (value "L-1334SRT")
      (footprint "eagle-import:LED3MM")
      (libsource (lib "eagle-import") (part "L-1334SRT"))
    )
    (comp (ref "D160")
      (value "L-1334SRT")
      (footprint "eagle-import:LED3MM")
      (libsource (lib "eagle-import") (part "L-1334SRT"))
    )
    (comp (ref "D161")
      (value "L-1334SRT")
      (footprint "eagle-import:LED3MM")
      (libsource (lib "eagle-import") (part "L-1334SRT"))
    )
    (comp (ref "Q193")
      (value "2N7000")
      (footprint "eagle-import:TO92-DGS")
      (libsource (lib "eagle-import") (part "2N7000"))
    )
    (comp (ref "Q194")
      (value "2N7000")
      (footprint "eagle-import:TO92-DGS")
      (libsource (lib "eagle-import") (part "2N7000"))
    )
    (comp (ref "Q195")
      (value "2N7000")
      (footprint "eagle-import:TO92-DGS")
      (libsource (lib "eagle-import") (part "2N7000"))
    )
    (comp (ref "Q196")
      (value "2N7000")
      (footprint "eagle-import:TO92-DGS")
      (libsource (lib "eagle-import") (part "2N7000"))
    )
    (comp (ref "Q197")
      (value "2N7000")
      (footprint "eagle-import:TO92-DGS")
      (libsource (lib "eagle-import") (part "2N7000"))
    )
    (comp (ref "Q198")
      (value "2N7000")
      (footprint "eagle-import:TO92-DGS")
      (libsource (lib "eagle-import") (part "2N7000"))
    )
    (comp (ref "Q199")
      (value "2N7000")
      (footprint "eagle-import:TO92-DGS")
      (libsource (lib "eagle-import") (part "2N7000"))
    )
    (comp (ref "Q200")
      (value "2N7000")
      (footprint "eagle-import:TO92-DGS")
      (libsource (lib "eagle-import") (part "2N7000"))
    )
    (comp (ref "Q201")
      (value "2N7000")
      (footprint "eagle-import:TO92-DGS")
      (libsource (lib "eagle-import") (part "2N7000"))
    )
    (comp (ref "Q202")
      (value "2N7000")
      (footprint "eagle-import:TO92-DGS")
      (libsource (lib "eagle-import") (part "2N7000"))
    )
    (comp (ref "Q203")
      (value "2N7000")
      (footprint "eagle-import:TO92-DGS")
      (libsource (lib "eagle-import") (part "2N7000"))
    )
    (comp (ref "Q204")
      (value "2N7000")
      (footprint "eagle-import:TO92-DGS")
      (libsource (lib "eagle-import") (part "2N7000"))
    )
    (comp (ref "Q205")
      (value "2N7000")
      (footprint "eagle-import:TO92-DGS")
      (libsource (lib "eagle-import") (part "2N7000"))
    )
    (comp (ref "Q206")
      (value "2N7000")
      (footprint "eagle-import:TO92-DGS")
      (libsource (lib "eagle-import") (part "2N7000"))
    )
    (comp (ref "Q207")
      (value "2N7000")
      (footprint "eagle-import:TO92-DGS")
      (libsource (lib "eagle-import") (part "2N7000"))
    )
    (comp (ref "Q208")
      (value "2N7000")
      (footprint "eagle-import:TO92-DGS")
      (libsource (lib "eagle-import") (part "2N7000"))
    )
    (comp (ref "R241")
      (value "10k")
      (footprint "eagle-import:R_P2INCH")
      (libsource (lib "eagle-import") (part "R_P2INCH"))
    )
    (comp (ref "R242")
      (value "10k")
      (footprint "eagle-import:R_P2INCH")
      (libsource (lib "eagle-import") (part "R_P2INCH"))
    )
    (comp (ref "R243")
      (value "10k")
      (footprint "eagle-import:R_P2INCH")
      (libsource (lib "eagle-import") (part "R_P2INCH"))
    )
    (comp (ref "R244")
      (value "10k")
      (footprint "eagle-import:R_P2INCH")
      (libsource (lib "eagle-import") (part "R_P2INCH"))
    )
    (comp (ref "R245")
      (value "10k")
      (footprint "eagle-import:R_P2INCH")
      (libsource (lib "eagle-import") (part "R_P2INCH"))
    )
    (comp (ref "R246")
      (value "10k")
      (footprint "eagle-import:R_P2INCH")
      (libsource (lib "eagle-import") (part "R_P2INCH"))
    )
    (comp (ref "R247")
      (value "10k")
      (footprint "eagle-import:R_P2INCH")
      (libsource (lib "eagle-import") (part "R_P2INCH"))
    )
    (comp (ref "R248")
      (value "10k")
      (footprint "eagle-import:R_P2INCH")
      (libsource (lib "eagle-import") (part "R_P2INCH"))
    )
    (comp (ref "R249")
      (value "10k")
      (footprint "eagle-import:R_P2INCH")
      (libsource (lib "eagle-import") (part "R_P2INCH"))
    )
    (comp (ref "R250")
      (value "10k")
      (footprint "eagle-import:R_P2INCH")
      (libsource (lib "eagle-import") (part "R_P2INCH"))
    )
    (comp (ref "R251")
      (value "10k")
      (footprint "eagle-import:R_P2INCH")
      (libsource (lib "eagle-import") (part "R_P2INCH"))
    )
    (comp (ref "R252")
      (value "10k")
      (footprint "eagle-import:R_P2INCH")
      (libsource (lib "eagle-import") (part "R_P2INCH"))
    )
    (comp (ref "R253")
      (value "10k")
      (footprint "eagle-import:R_P2INCH")
      (libsource (lib "eagle-import") (part "R_P2INCH"))
    )
    (comp (ref "R254")
      (value "10k")
      (footprint "eagle-import:R_P2INCH")
      (libsource (lib "eagle-import") (part "R_P2INCH"))
    )
    (comp (ref "R255")
      (value "10k")
      (footprint "eagle-import:R_P2INCH")
      (libsource (lib "eagle-import") (part "R_P2INCH"))
    )
    (comp (ref "R256")
      (value "10k")
      (footprint "eagle-import:R_P2INCH")
      (libsource (lib "eagle-import") (part "R_P2INCH"))
    )
    (comp (ref "R259")
      (value "470")
      (footprint "eagle-import:R_P2INCH")
      (libsource (lib "eagle-import") (part "R_P2INCH"))
    )
    (comp (ref "R260")
      (value "470")
      (footprint "eagle-import:R_P2INCH")
      (libsource (lib "eagle-import") (part "R_P2INCH"))
    )
    (comp (ref "R261")
      (value "470")
      (footprint "eagle-import:R_P2INCH")
      (libsource (lib "eagle-import") (part "R_P2INCH"))
    )
    (comp (ref "R262")
      (value "470")
      (footprint "eagle-import:R_P2INCH")
      (libsource (lib "eagle-import") (part "R_P2INCH"))
    )
    (comp (ref "R263")
      (value "470")
      (footprint "eagle-import:R_P2INCH")
      (libsource (lib "eagle-import") (part "R_P2INCH"))
    )
    (comp (ref "R264")
      (value "470")
      (footprint "eagle-import:R_P2INCH")
      (libsource (lib "eagle-import") (part "R_P2INCH"))
    )
    (comp (ref "R265")
      (value "470")
      (footprint "eagle-import:R_P2INCH")
      (libsource (lib "eagle-import") (part "R_P2INCH"))
    )
    (comp (ref "R266")
      (value "470")
      (footprint "eagle-import:R_P2INCH")
      (libsource (lib "eagle-import") (part "R_P2INCH"))
    )
    (comp (ref "R267")
      (value "470")
      (footprint "eagle-import:R_P2INCH")
      (libsource (lib "eagle-import") (part "R_P2INCH"))
    )
    (comp (ref "R269")
      (value "470")
      (footprint "eagle-import:R_P2INCH")
      (libsource (lib "eagle-import") (part "R_P2INCH"))
    )
    (comp (ref "R270")
      (value "470")
      (footprint "eagle-import:R_P2INCH")
      (libsource (lib "eagle-import") (part "R_P2INCH"))
    )
    (comp (ref "R271")
      (value "470")
      (footprint "eagle-import:R_P2INCH")
      (libsource (lib "eagle-import") (part "R_P2INCH"))
    )
    (comp (ref "R272")
      (value "470")
      (footprint "eagle-import:R_P2INCH")
      (libsource (lib "eagle-import") (part "R_P2INCH"))
    )
    (comp (ref "R273")
      (value "470")
      (footprint "eagle-import:R_P2INCH")
      (libsource (lib "eagle-import") (part "R_P2INCH"))
    )
    (comp (ref "R274")
      (value "470")
      (footprint "eagle-import:R_P2INCH")
      (libsource (lib "eagle-import") (part "R_P2INCH"))
    )
    (comp (ref "R275")
      (value "470")
      (footprint "eagle-import:R_P2INCH")
      (libsource (lib "eagle-import") (part "R_P2INCH"))
    )
    (comp (ref "C1")
      (value "100n")
      (footprint "eagle-import:CAP_P2INCH")
      (libsource (lib "eagle-import") (part "C_P2INCH"))
    )
    (comp (ref "C2")
      (value "100n")
      (footprint "eagle-import:CAP_P2INCH")
      (libsource (lib "eagle-import") (part "C_P2INCH"))
    )
    (comp (ref "C3")
      (value "100n")
      (footprint "eagle-import:CAP_P2INCH")
      (libsource (lib "eagle-import") (part "C_P2INCH"))
    )
    (comp (ref "C4")
      (value "100n")
      (footprint "eagle-import:CAP_P2INCH")
      (libsource (lib "eagle-import") (part "C_P2INCH"))
    )
    (comp (ref "C5")
      (value "100n")
      (footprint "eagle-import:CAP_P2INCH")
      (libsource (lib "eagle-import") (part "C_P2INCH"))
    )
    (comp (ref "C6")
      (value "100uF")
      (footprint "eagle-import:POLARISED_CAP_2P5")
      (libsource (lib "eagle-import") (part "POLARISED_CAP_2P5"))
    )
    (comp (ref "C7")
      (value "100n")
      (footprint "eagle-import:CAP_P2INCH")
      (libsource (lib "eagle-import") (part "C_P2INCH"))
    )
    (comp (ref "C8")
      (value "100n")
      (footprint "eagle-import:CAP_P2INCH")
      (libsource (lib "eagle-import") (part "C_P2INCH"))
    )
    (comp (ref "C9")
      (value "100n")
      (footprint "eagle-import:CAP_P2INCH")
      (libsource (lib "eagle-import") (part "C_P2INCH"))
    )
    (comp (ref "C10")
      (value "100n")
      (footprint "eagle-import:CAP_P2INCH")
      (libsource (lib "eagle-import") (part "C_P2INCH"))
    )
    (comp (ref "H1")
      (value "3M_MOUNT_HOLE")
      (footprint "eagle-import:3M_HOLE")
      (libsource (lib "eagle-import") (part "3M_MOUNT_HOLE"))
    )
    (comp (ref "H2")
      (value "3M_MOUNT_HOLE")
      (footprint "eagle-import:3M_HOLE")
      (libsource (lib "eagle-import") (part "3M_MOUNT_HOLE"))
    )
    (comp (ref "HOLE1")
      (value "3M_MOUNT_HOLE")
      (footprint "eagle-import:3M_HOLE")
      (libsource (lib "eagle-import") (part "3M_MOUNT_HOLE"))
    )
    (comp (ref "HOLE2")
      (value "3M_MOUNT_HOLE")
      (footprint "eagle-import:3M_HOLE")
      (libsource (lib "eagle-import") (part "3M_MOUNT_HOLE"))
    )
    (comp (ref "HOLE3")
      (value "3M_MOUNT_HOLE")
      (footprint "eagle-import:3M_HOLE")
      (libsource (lib "eagle-import") (part "3M_MOUNT_HOLE"))
    )
    (comp (ref "HOLE4")
      (value "3M_MOUNT_HOLE")
      (footprint "eagle-import:3M_HOLE")
      (libsource (lib "eagle-import") (part "3M_MOUNT_HOLE"))
    )
    (comp (ref "HOLE5")
      (value "3M_MOUNT_HOLE")
      (footprint "eagle-import:3M_HOLE")
      (libsource (lib "eagle-import") (part "3M_MOUNT_HOLE"))
    )
    (comp (ref "HOLE6")
      (value "3M_MOUNT_HOLE")
      (footprint "eagle-import:3M_HOLE")
      (libsource (lib "eagle-import") (part "3M_MOUNT_HOLE"))
    )
    (comp (ref "PP1")
      (value "POWER_PAD")
      (footprint "eagle-import:POWER_PAD")
      (libsource (lib "eagle-import") (part "POWER_PAD"))
    )
    (comp (ref "PP2")
      (value "POWER_PAD")
      (footprint "eagle-import:POWER_PAD")
      (libsource (lib "eagle-import") (part "POWER_PAD"))
    )
    (comp (ref "TP4")
      (value "TEST_LOOP")
      (footprint "eagle-import:TEST_LOOP")
      (libsource (lib "eagle-import") (part "TEST_LOOP"))
    )
    (comp (ref "TP5")
      (value "TEST_LOOP")
      (footprint "eagle-import:TEST_LOOP")
      (libsource (lib "eagle-import") (part "TEST_LOOP"))
    )
    (comp (ref "TP6")
      (value "TEST_LOOP")
      (footprint "eagle-import:TEST_LOOP")
      (libsource (lib "eagle-import") (part "TEST_LOOP"))
    )
    (comp (ref "TP7")
      (value "TEST_LOOP")
      (footprint "eagle-import:TEST_LOOP")
      (libsource (lib "eagle-import") (part "TEST_LOOP"))
    )
    (comp (ref "D67")
      (value "L-1334SRT")
      (footprint "eagle-import:LED3MM")
      (libsource (lib "eagle-import") (part "L-1334SRT"))
    )
    (comp (ref "D68")
      (value "L-1334SRT")
      (footprint "eagle-import:LED3MM")
      (libsource (lib "eagle-import") (part "L-1334SRT"))
    )
    (comp (ref "D69")
      (value "L-1334SRT")
      (footprint "eagle-import:LED3MM")
      (libsource (lib "eagle-import") (part "L-1334SRT"))
    )
    (comp (ref "D112")
      (value "L-1334SRT")
      (footprint "eagle-import:LED3MM")
      (libsource (lib "eagle-import") (part "L-1334SRT"))
    )
    (comp (ref "D113")
      (value "L-1334SRT")
      (footprint "eagle-import:LED3MM")
      (libsource (lib "eagle-import") (part "L-1334SRT"))
    )
    (comp (ref "D114")
      (value "L-1334SRT")
      (footprint "eagle-import:LED3MM")
      (libsource (lib "eagle-import") (part "L-1334SRT"))
    )
    (comp (ref "D115")
      (value "L-1334SRT")
      (footprint "eagle-import:LED3MM")
      (libsource (lib "eagle-import") (part "L-1334SRT"))
    )
    (comp (ref "D116")
      (value "L-1334SRT")
      (footprint "eagle-import:LED3MM")
      (libsource (lib "eagle-import") (part "L-1334SRT"))
    )
    (comp (ref "D117")
      (value "L-1334SRT")
      (footprint "eagle-import:LED3MM")
      (libsource (lib "eagle-import") (part "L-1334SRT"))
    )
    (comp (ref "Q99")
      (value "2N7000")
      (footprint "eagle-import:TO92-DGS")
      (libsource (lib "eagle-import") (part "2N7000"))
    )
    (comp (ref "Q100")
      (value "2N7000")
      (footprint "eagle-import:TO92-DGS")
      (libsource (lib "eagle-import") (part "2N7000"))
    )
    (comp (ref "Q101")
      (value "2N7000")
      (footprint "eagle-import:TO92-DGS")
      (libsource (lib "eagle-import") (part "2N7000"))
    )
    (comp (ref "Q102")
      (value "2N7000")
      (footprint "eagle-import:TO92-DGS")
      (libsource (lib "eagle-import") (part "2N7000"))
    )
    (comp (ref "Q103")
      (value "2N7000")
      (footprint "eagle-import:TO92-DGS")
      (libsource (lib "eagle-import") (part "2N7000"))
    )
    (comp (ref "Q160")
      (value "2N7000")
      (footprint "eagle-import:TO92-DGS")
      (libsource (lib "eagle-import") (part "2N7000"))
    )
    (comp (ref "Q161")
      (value "2N7000")
      (footprint "eagle-import:TO92-DGS")
      (libsource (lib "eagle-import") (part "2N7000"))
    )
    (comp (ref "Q162")
      (value "2N7000")
      (footprint "eagle-import:TO92-DGS")
      (libsource (lib "eagle-import") (part "2N7000"))
    )
    (comp (ref "Q163")
      (value "2N7000")
      (footprint "eagle-import:TO92-DGS")
      (libsource (lib "eagle-import") (part "2N7000"))
    )
    (comp (ref "Q164")
      (value "2N7000")
      (footprint "eagle-import:TO92-DGS")
      (libsource (lib "eagle-import") (part "2N7000"))
    )
    (comp (ref "Q165")
      (value "2N7000")
      (footprint "eagle-import:TO92-DGS")
      (libsource (lib "eagle-import") (part "2N7000"))
    )
    (comp (ref "R111")
      (value "10k")
      (footprint "eagle-import:R_P2INCH")
      (libsource (lib "eagle-import") (part "R_P2INCH"))
    )
    (comp (ref "R112")
      (value "470")
      (footprint "eagle-import:R_P2INCH")
      (libsource (lib "eagle-import") (part "R_P2INCH"))
    )
    (comp (ref "R113")
      (value "10k")
      (footprint "eagle-import:R_P2INCH")
      (libsource (lib "eagle-import") (part "R_P2INCH"))
    )
    (comp (ref "R114")
      (value "470")
      (footprint "eagle-import:R_P2INCH")
      (libsource (lib "eagle-import") (part "R_P2INCH"))
    )
    (comp (ref "R115")
      (value "470")
      (footprint "eagle-import:R_P2INCH")
      (libsource (lib "eagle-import") (part "R_P2INCH"))
    )
    (comp (ref "R186")
      (value "10k")
      (footprint "eagle-import:R_P2INCH")
      (libsource (lib "eagle-import") (part "R_P2INCH"))
    )
    (comp (ref "R187")
      (value "470")
      (footprint "eagle-import:R_P2INCH")
      (libsource (lib "eagle-import") (part "R_P2INCH"))
    )
    (comp (ref "R188")
      (value "10k")
      (footprint "eagle-import:R_P2INCH")
      (libsource (lib "eagle-import") (part "R_P2INCH"))
    )
    (comp (ref "R189")
      (value "470")
      (footprint "eagle-import:R_P2INCH")
      (libsource (lib "eagle-import") (part "R_P2INCH"))
    )
    (comp (ref "R190")
      (value "470")
      (footprint "eagle-import:R_P2INCH")
      (libsource (lib "eagle-import") (part "R_P2INCH"))
    )
    (comp (ref "R191")
      (value "10k")
      (footprint "eagle-import:R_P2INCH")
      (libsource (lib "eagle-import") (part "R_P2INCH"))
    )
    (comp (ref "R192")
      (value "470")
      (footprint "eagle-import:R_P2INCH")
      (libsource (lib "eagle-import") (part "R_P2INCH"))
    )
    (comp (ref "R193")
      (value "10k")
      (footprint "eagle-import:R_P2INCH")
      (libsource (lib "eagle-import") (part "R_P2INCH"))
    )
    (comp (ref "R194")
      (value "470")
      (footprint "eagle-import:R_P2INCH")
      (libsource (lib "eagle-import") (part "R_P2INCH"))
    )
    (comp (ref "R195")
      (value "470")
      (footprint "eagle-import:R_P2INCH")
      (libsource (lib "eagle-import") (part "R_P2INCH"))
    )
    (comp (ref "D79")
      (value "L-1334SRT")
      (footprint "eagle-import:LED3MM")
      (libsource (lib "eagle-import") (part "L-1334SRT"))
    )
    (comp (ref "D80")
      (value "L-1334SRT")
      (footprint "eagle-import:LED3MM")
      (libsource (lib "eagle-import") (part "L-1334SRT"))
    )
    (comp (ref "D81")
      (value "L-1334SRT")
      (footprint "eagle-import:LED3MM")
      (libsource (lib "eagle-import") (part "L-1334SRT"))
    )
    (comp (ref "D130")
      (value "L-1334SRT")
      (footprint "eagle-import:LED3MM")
      (libsource (lib "eagle-import") (part "L-1334SRT"))
    )
    (comp (ref "D131")
      (value "L-1334SRT")
      (footprint "eagle-import:LED3MM")
      (libsource (lib "eagle-import") (part "L-1334SRT"))
    )
    (comp (ref "D132")
      (value "L-1334SRT")
      (footprint "eagle-import:LED3MM")
      (libsource (lib "eagle-import") (part "L-1334SRT"))
    )
    (comp (ref "D133")
      (value "L-1334SRT")
      (footprint "eagle-import:LED3MM")
      (libsource (lib "eagle-import") (part "L-1334SRT"))
    )
    (comp (ref "D134")
      (value "L-1334SRT")
      (footprint "eagle-import:LED3MM")
      (libsource (lib "eagle-import") (part "L-1334SRT"))
    )
    (comp (ref "D135")
      (value "L-1334SRT")
      (footprint "eagle-import:LED3MM")
      (libsource (lib "eagle-import") (part "L-1334SRT"))
    )
    (comp (ref "Q119")
      (value "2N7000")
      (footprint "eagle-import:TO92-DGS")
      (libsource (lib "eagle-import") (part "2N7000"))
    )
    (comp (ref "Q120")
      (value "2N7000")
      (footprint "eagle-import:TO92-DGS")
      (libsource (lib "eagle-import") (part "2N7000"))
    )
    (comp (ref "Q121")
      (value "2N7000")
      (footprint "eagle-import:TO92-DGS")
      (libsource (lib "eagle-import") (part "2N7000"))
    )
    (comp (ref "Q122")
      (value "2N7000")
      (footprint "eagle-import:TO92-DGS")
      (libsource (lib "eagle-import") (part "2N7000"))
    )
    (comp (ref "Q123")
      (value "2N7000")
      (footprint "eagle-import:TO92-DGS")
      (libsource (lib "eagle-import") (part "2N7000"))
    )
    (comp (ref "Q178")
      (value "2N7000")
      (footprint "eagle-import:TO92-DGS")
      (libsource (lib "eagle-import") (part "2N7000"))
    )
    (comp (ref "Q179")
      (value "2N7000")
      (footprint "eagle-import:TO92-DGS")
      (libsource (lib "eagle-import") (part "2N7000"))
    )
    (comp (ref "Q180")
      (value "2N7000")
      (footprint "eagle-import:TO92-DGS")
      (libsource (lib "eagle-import") (part "2N7000"))
    )
    (comp (ref "Q181")
      (value "2N7000")
      (footprint "eagle-import:TO92-DGS")
      (libsource (lib "eagle-import") (part "2N7000"))
    )
    (comp (ref "Q182")
      (value "2N7000")
      (footprint "eagle-import:TO92-DGS")
      (libsource (lib "eagle-import") (part "2N7000"))
    )
    (comp (ref "Q183")
      (value "2N7000")
      (footprint "eagle-import:TO92-DGS")
      (libsource (lib "eagle-import") (part "2N7000"))
    )
    (comp (ref "R131")
      (value "10k")
      (footprint "eagle-import:R_P2INCH")
      (libsource (lib "eagle-import") (part "R_P2INCH"))
    )
    (comp (ref "R132")
      (value "470")
      (footprint "eagle-import:R_P2INCH")
      (libsource (lib "eagle-import") (part "R_P2INCH"))
    )
    (comp (ref "R133")
      (value "10k")
      (footprint "eagle-import:R_P2INCH")
      (libsource (lib "eagle-import") (part "R_P2INCH"))
    )
    (comp (ref "R134")
      (value "470")
      (footprint "eagle-import:R_P2INCH")
      (libsource (lib "eagle-import") (part "R_P2INCH"))
    )
    (comp (ref "R135")
      (value "470")
      (footprint "eagle-import:R_P2INCH")
      (libsource (lib "eagle-import") (part "R_P2INCH"))
    )
    (comp (ref "R216")
      (value "10k")
      (footprint "eagle-import:R_P2INCH")
      (libsource (lib "eagle-import") (part "R_P2INCH"))
    )
    (comp (ref "R217")
      (value "470")
      (footprint "eagle-import:R_P2INCH")
      (libsource (lib "eagle-import") (part "R_P2INCH"))
    )
    (comp (ref "R218")
      (value "10k")
      (footprint "eagle-import:R_P2INCH")
      (libsource (lib "eagle-import") (part "R_P2INCH"))
    )
    (comp (ref "R219")
      (value "470")
      (footprint "eagle-import:R_P2INCH")
      (libsource (lib "eagle-import") (part "R_P2INCH"))
    )
    (comp (ref "R220")
      (value "470")
      (footprint "eagle-import:R_P2INCH")
      (libsource (lib "eagle-import") (part "R_P2INCH"))
    )
    (comp (ref "R221")
      (value "10k")
      (footprint "eagle-import:R_P2INCH")
      (libsource (lib "eagle-import") (part "R_P2INCH"))
    )
    (comp (ref "R222")
      (value "470")
      (footprint "eagle-import:R_P2INCH")
      (libsource (lib "eagle-import") (part "R_P2INCH"))
    )
    (comp (ref "R223")
      (value "10k")
      (footprint "eagle-import:R_P2INCH")
      (libsource (lib "eagle-import") (part "R_P2INCH"))
    )
    (comp (ref "R224")
      (value "470")
      (footprint "eagle-import:R_P2INCH")
      (libsource (lib "eagle-import") (part "R_P2INCH"))
    )
    (comp (ref "R225")
      (value "470")
      (footprint "eagle-import:R_P2INCH")
      (libsource (lib "eagle-import") (part "R_P2INCH"))
    )
    (comp (ref "D61")
      (value "L-1334SRT")
      (footprint "eagle-import:LED3MM")
      (libsource (lib "eagle-import") (part "L-1334SRT"))
    )
    (comp (ref "D62")
      (value "L-1334SRT")
      (footprint "eagle-import:LED3MM")
      (libsource (lib "eagle-import") (part "L-1334SRT"))
    )
    (comp (ref "D63")
      (value "L-1334SRT")
      (footprint "eagle-import:LED3MM")
      (libsource (lib "eagle-import") (part "L-1334SRT"))
    )
    (comp (ref "D103")
      (value "L-1334SRT")
      (footprint "eagle-import:LED3MM")
      (libsource (lib "eagle-import") (part "L-1334SRT"))
    )
    (comp (ref "D104")
      (value "L-1334SRT")
      (footprint "eagle-import:LED3MM")
      (libsource (lib "eagle-import") (part "L-1334SRT"))
    )
    (comp (ref "D105")
      (value "L-1334SRT")
      (footprint "eagle-import:LED3MM")
      (libsource (lib "eagle-import") (part "L-1334SRT"))
    )
    (comp (ref "D106")
      (value "L-1334SRT")
      (footprint "eagle-import:LED3MM")
      (libsource (lib "eagle-import") (part "L-1334SRT"))
    )
    (comp (ref "D107")
      (value "L-1334SRT")
      (footprint "eagle-import:LED3MM")
      (libsource (lib "eagle-import") (part "L-1334SRT"))
    )
    (comp (ref "D108")
      (value "L-1334SRT")
      (footprint "eagle-import:LED3MM")
      (libsource (lib "eagle-import") (part "L-1334SRT"))
    )
    (comp (ref "Q89")
      (value "2N7000")
      (footprint "eagle-import:TO92-DGS")
      (libsource (lib "eagle-import") (part "2N7000"))
    )
    (comp (ref "Q90")
      (value "2N7000")
      (footprint "eagle-import:TO92-DGS")
      (libsource (lib "eagle-import") (part "2N7000"))
    )
    (comp (ref "Q91")
      (value "2N7000")
      (footprint "eagle-import:TO92-DGS")
      (libsource (lib "eagle-import") (part "2N7000"))
    )
    (comp (ref "Q92")
      (value "2N7000")
      (footprint "eagle-import:TO92-DGS")
      (libsource (lib "eagle-import") (part "2N7000"))
    )
    (comp (ref "Q93")
      (value "2N7000")
      (footprint "eagle-import:TO92-DGS")
      (libsource (lib "eagle-import") (part "2N7000"))
    )
    (comp (ref "Q151")
      (value "2N7000")
      (footprint "eagle-import:TO92-DGS")
      (libsource (lib "eagle-import") (part "2N7000"))
    )
    (comp (ref "Q152")
      (value "2N7000")
      (footprint "eagle-import:TO92-DGS")
      (libsource (lib "eagle-import") (part "2N7000"))
    )
    (comp (ref "Q153")
      (value "2N7000")
      (footprint "eagle-import:TO92-DGS")
      (libsource (lib "eagle-import") (part "2N7000"))
    )
    (comp (ref "Q154")
      (value "2N7000")
      (footprint "eagle-import:TO92-DGS")
      (libsource (lib "eagle-import") (part "2N7000"))
    )
    (comp (ref "Q155")
      (value "2N7000")
      (footprint "eagle-import:TO92-DGS")
      (libsource (lib "eagle-import") (part "2N7000"))
    )
    (comp (ref "Q156")
      (value "2N7000")
      (footprint "eagle-import:TO92-DGS")
      (libsource (lib "eagle-import") (part "2N7000"))
    )
    (comp (ref "R101")
      (value "10k")
      (footprint "eagle-import:R_P2INCH")
      (libsource (lib "eagle-import") (part "R_P2INCH"))
    )
    (comp (ref "R102")
      (value "470")
      (footprint "eagle-import:R_P2INCH")
      (libsource (lib "eagle-import") (part "R_P2INCH"))
    )
    (comp (ref "R103")
      (value "10k")
      (footprint "eagle-import:R_P2INCH")
      (libsource (lib "eagle-import") (part "R_P2INCH"))
    )
    (comp (ref "R104")
      (value "470")
      (footprint "eagle-import:R_P2INCH")
      (libsource (lib "eagle-import") (part "R_P2INCH"))
    )
    (comp (ref "R105")
      (value "470")
      (footprint "eagle-import:R_P2INCH")
      (libsource (lib "eagle-import") (part "R_P2INCH"))
    )
    (comp (ref "R171")
      (value "10k")
      (footprint "eagle-import:R_P2INCH")
      (libsource (lib "eagle-import") (part "R_P2INCH"))
    )
    (comp (ref "R172")
      (value "470")
      (footprint "eagle-import:R_P2INCH")
      (libsource (lib "eagle-import") (part "R_P2INCH"))
    )
    (comp (ref "R173")
      (value "10k")
      (footprint "eagle-import:R_P2INCH")
      (libsource (lib "eagle-import") (part "R_P2INCH"))
    )
    (comp (ref "R174")
      (value "470")
      (footprint "eagle-import:R_P2INCH")
      (libsource (lib "eagle-import") (part "R_P2INCH"))
    )
    (comp (ref "R175")
      (value "470")
      (footprint "eagle-import:R_P2INCH")
      (libsource (lib "eagle-import") (part "R_P2INCH"))
    )
    (comp (ref "R176")
      (value "10k")
      (footprint "eagle-import:R_P2INCH")
      (libsource (lib "eagle-import") (part "R_P2INCH"))
    )
    (comp (ref "R177")
      (value "470")
      (footprint "eagle-import:R_P2INCH")
      (libsource (lib "eagle-import") (part "R_P2INCH"))
    )
    (comp (ref "R178")
      (value "10k")
      (footprint "eagle-import:R_P2INCH")
      (libsource (lib "eagle-import") (part "R_P2INCH"))
    )
    (comp (ref "R179")
      (value "470")
      (footprint "eagle-import:R_P2INCH")
      (libsource (lib "eagle-import") (part "R_P2INCH"))
    )
    (comp (ref "R180")
      (value "470")
      (footprint "eagle-import:R_P2INCH")
      (libsource (lib "eagle-import") (part "R_P2INCH"))
    )
    (comp (ref "D55")
      (value "L-1334SRT")
      (footprint "eagle-import:LED3MM")
      (libsource (lib "eagle-import") (part "L-1334SRT"))
    )
    (comp (ref "D56")
      (value "L-1334SRT")
      (footprint "eagle-import:LED3MM")
      (libsource (lib "eagle-import") (part "L-1334SRT"))
    )
    (comp (ref "D57")
      (value "L-1334SRT")
      (footprint "eagle-import:LED3MM")
      (libsource (lib "eagle-import") (part "L-1334SRT"))
    )
    (comp (ref "D94")
      (value "L-1334SRT")
      (footprint "eagle-import:LED3MM")
      (libsource (lib "eagle-import") (part "L-1334SRT"))
    )
    (comp (ref "D95")
      (value "L-1334SRT")
      (footprint "eagle-import:LED3MM")
      (libsource (lib "eagle-import") (part "L-1334SRT"))
    )
    (comp (ref "D96")
      (value "L-1334SRT")
      (footprint "eagle-import:LED3MM")
      (libsource (lib "eagle-import") (part "L-1334SRT"))
    )
    (comp (ref "D97")
      (value "L-1334SRT")
      (footprint "eagle-import:LED3MM")
      (libsource (lib "eagle-import") (part "L-1334SRT"))
    )
    (comp (ref "D98")
      (value "L-1334SRT")
      (footprint "eagle-import:LED3MM")
      (libsource (lib "eagle-import") (part "L-1334SRT"))
    )
    (comp (ref "D99")
      (value "L-1334SRT")
      (footprint "eagle-import:LED3MM")
      (libsource (lib "eagle-import") (part "L-1334SRT"))
    )
    (comp (ref "Q79")
      (value "2N7000")
      (footprint "eagle-import:TO92-DGS")
      (libsource (lib "eagle-import") (part "2N7000"))
    )
    (comp (ref "Q80")
      (value "2N7000")
      (footprint "eagle-import:TO92-DGS")
      (libsource (lib "eagle-import") (part "2N7000"))
    )
    (comp (ref "Q81")
      (value "2N7000")
      (footprint "eagle-import:TO92-DGS")
      (libsource (lib "eagle-import") (part "2N7000"))
    )
    (comp (ref "Q82")
      (value "2N7000")
      (footprint "eagle-import:TO92-DGS")
      (libsource (lib "eagle-import") (part "2N7000"))
    )
    (comp (ref "Q83")
      (value "2N7000")
      (footprint "eagle-import:TO92-DGS")
      (libsource (lib "eagle-import") (part "2N7000"))
    )
    (comp (ref "Q142")
      (value "2N7000")
      (footprint "eagle-import:TO92-DGS")
      (libsource (lib "eagle-import") (part "2N7000"))
    )
    (comp (ref "Q143")
      (value "2N7000")
      (footprint "eagle-import:TO92-DGS")
      (libsource (lib "eagle-import") (part "2N7000"))
    )
    (comp (ref "Q144")
      (value "2N7000")
      (footprint "eagle-import:TO92-DGS")
      (libsource (lib "eagle-import") (part "2N7000"))
    )
    (comp (ref "Q145")
      (value "2N7000")
      (footprint "eagle-import:TO92-DGS")
      (libsource (lib "eagle-import") (part "2N7000"))
    )
    (comp (ref "Q146")
      (value "2N7000")
      (footprint "eagle-import:TO92-DGS")
      (libsource (lib "eagle-import") (part "2N7000"))
    )
    (comp (ref "Q147")
      (value "2N7000")
      (footprint "eagle-import:TO92-DGS")
      (libsource (lib "eagle-import") (part "2N7000"))
    )
    (comp (ref "R91")
      (value "10k")
      (footprint "eagle-import:R_P2INCH")
      (libsource (lib "eagle-import") (part "R_P2INCH"))
    )
    (comp (ref "R92")
      (value "470")
      (footprint "eagle-import:R_P2INCH")
      (libsource (lib "eagle-import") (part "R_P2INCH"))
    )
    (comp (ref "R93")
      (value "10k")
      (footprint "eagle-import:R_P2INCH")
      (libsource (lib "eagle-import") (part "R_P2INCH"))
    )
    (comp (ref "R94")
      (value "470")
      (footprint "eagle-import:R_P2INCH")
      (libsource (lib "eagle-import") (part "R_P2INCH"))
    )
    (comp (ref "R95")
      (value "470")
      (footprint "eagle-import:R_P2INCH")
      (libsource (lib "eagle-import") (part "R_P2INCH"))
    )
    (comp (ref "R156")
      (value "10k")
      (footprint "eagle-import:R_P2INCH")
      (libsource (lib "eagle-import") (part "R_P2INCH"))
    )
    (comp (ref "R157")
      (value "470")
      (footprint "eagle-import:R_P2INCH")
      (libsource (lib "eagle-import") (part "R_P2INCH"))
    )
    (comp (ref "R158")
      (value "10k")
      (footprint "eagle-import:R_P2INCH")
      (libsource (lib "eagle-import") (part "R_P2INCH"))
    )
    (comp (ref "R159")
      (value "470")
      (footprint "eagle-import:R_P2INCH")
      (libsource (lib "eagle-import") (part "R_P2INCH"))
    )
    (comp (ref "R160")
      (value "470")
      (footprint "eagle-import:R_P2INCH")
      (libsource (lib "eagle-import") (part "R_P2INCH"))
    )
    (comp (ref "R161")
      (value "10k")
      (footprint "eagle-import:R_P2INCH")
      (libsource (lib "eagle-import") (part "R_P2INCH"))
    )
    (comp (ref "R162")
      (value "470")
      (footprint "eagle-import:R_P2INCH")
      (libsource (lib "eagle-import") (part "R_P2INCH"))
    )
    (comp (ref "R163")
      (value "10k")
      (footprint "eagle-import:R_P2INCH")
      (libsource (lib "eagle-import") (part "R_P2INCH"))
    )
    (comp (ref "R164")
      (value "470")
      (footprint "eagle-import:R_P2INCH")
      (libsource (lib "eagle-import") (part "R_P2INCH"))
    )
    (comp (ref "R165")
      (value "470")
      (footprint "eagle-import:R_P2INCH")
      (libsource (lib "eagle-import") (part "R_P2INCH"))
    )
    (comp (ref "D1")
      (value "L-1334SRT")
      (footprint "eagle-import:LED3MM")
      (libsource (lib "eagle-import") (part "L-1334SRT"))
    )
    (comp (ref "D2")
      (value "L-1334SRT")
      (footprint "eagle-import:LED3MM")
      (libsource (lib "eagle-import") (part "L-1334SRT"))
    )
    (comp (ref "D3")
      (value "L-1334SRT")
      (footprint "eagle-import:LED3MM")
      (libsource (lib "eagle-import") (part "L-1334SRT"))
    )
    (comp (ref "D54")
      (value "L-1334SRT")
      (footprint "eagle-import:LED3MM")
      (libsource (lib "eagle-import") (part "L-1334SRT"))
    )
    (comp (ref "D58")
      (value "L-1334SRT")
      (footprint "eagle-import:LED3MM")
      (libsource (lib "eagle-import") (part "L-1334SRT"))
    )
    (comp (ref "D59")
      (value "L-1334SRT")
      (footprint "eagle-import:LED3MM")
      (libsource (lib "eagle-import") (part "L-1334SRT"))
    )
    (comp (ref "J1")
      (value "20_HDR_LOCKING_RA")
      (footprint "eagle-import:20_HDR_LOCKING_RA")
      (libsource (lib "eagle-import") (part "20_HDR_LOCKING_RA"))
    )
    (comp (ref "J2")
      (value "20_HDR_LOCKING_RA")
      (footprint "eagle-import:20_HDR_LOCKING_RA")
      (libsource (lib "eagle-import") (part "20_HDR_LOCKING_RA"))
    )
    (comp (ref "J3")
      (value "20_HDR_LOCKING_RA")
      (footprint "eagle-import:20_HDR_LOCKING_RA")
      (libsource (lib "eagle-import") (part "20_HDR_LOCKING_RA"))
    )
    (comp (ref "Q1")
      (value "2N7000")
      (footprint "eagle-import:TO92-DGS")
      (libsource (lib "eagle-import") (part "2N7000"))
    )
    (comp (ref "Q2")
      (value "2N7000")
      (footprint "eagle-import:TO92-DGS")
      (libsource (lib "eagle-import") (part "2N7000"))
    )
    (comp (ref "Q3")
      (value "2N7000")
      (footprint "eagle-import:TO92-DGS")
      (libsource (lib "eagle-import") (part "2N7000"))
    )
    (comp (ref "Q61")
      (value "2N7000")
      (footprint "eagle-import:TO92-DGS")
      (libsource (lib "eagle-import") (part "2N7000"))
    )
    (comp (ref "Q62")
      (value "2N7000")
      (footprint "eagle-import:TO92-DGS")
      (libsource (lib "eagle-import") (part "2N7000"))
    )
    (comp (ref "Q63")
      (value "2N7000")
      (footprint "eagle-import:TO92-DGS")
      (libsource (lib "eagle-import") (part "2N7000"))
    )
    (comp (ref "R1")
      (value "10k")
      (footprint "eagle-import:R_P2INCH")
      (libsource (lib "eagle-import") (part "R_P2INCH"))
    )
    (comp (ref "R2")
      (value "10k")
      (footprint "eagle-import:R_P2INCH")
      (libsource (lib "eagle-import") (part "R_P2INCH"))
    )
    (comp (ref "R3")
      (value "470")
      (footprint "eagle-import:R_P2INCH")
      (libsource (lib "eagle-import") (part "R_P2INCH"))
    )
    (comp (ref "R4")
      (value "470")
      (footprint "eagle-import:R_P2INCH")
      (libsource (lib "eagle-import") (part "R_P2INCH"))
    )
    (comp (ref "R5")
      (value "10k")
      (footprint "eagle-import:R_P2INCH")
      (libsource (lib "eagle-import") (part "R_P2INCH"))
    )
    (comp (ref "R6")
      (value "470")
      (footprint "eagle-import:R_P2INCH")
      (libsource (lib "eagle-import") (part "R_P2INCH"))
    )
    (comp (ref "R31")
      (value "470")
      (footprint "eagle-import:R_P2INCH")
      (libsource (lib "eagle-import") (part "R_P2INCH"))
    )
    (comp (ref "R32")
      (value "470")
      (footprint "eagle-import:R_P2INCH")
      (libsource (lib "eagle-import") (part "R_P2INCH"))
    )
    (comp (ref "R33")
      (value "470")
      (footprint "eagle-import:R_P2INCH")
      (libsource (lib "eagle-import") (part "R_P2INCH"))
    )
    (comp (ref "R34")
      (value "10k")
      (footprint "eagle-import:R_P2INCH")
      (libsource (lib "eagle-import") (part "R_P2INCH"))
    )
    (comp (ref "R35")
      (value "10k")
      (footprint "eagle-import:R_P2INCH")
      (libsource (lib "eagle-import") (part "R_P2INCH"))
    )
    (comp (ref "R41")
      (value "10k")
      (footprint "eagle-import:R_P2INCH")
      (libsource (lib "eagle-import") (part "R_P2INCH"))
    )
    (comp (ref "TP1")
      (value "TEST_LOOP")
      (footprint "eagle-import:TEST_LOOP")
      (libsource (lib "eagle-import") (part "TEST_LOOP"))
    )
    (comp (ref "TP2")
      (value "TEST_LOOP")
      (footprint "eagle-import:TEST_LOOP")
      (libsource (lib "eagle-import") (part "TEST_LOOP"))
    )
    (comp (ref "TP3")
      (value "TEST_LOOP")
      (footprint "eagle-import:TEST_LOOP")
      (libsource (lib "eagle-import") (part "TEST_LOOP"))
    )
    (comp (ref "D16")
      (value "L-1334SRT")
      (footprint "eagle-import:LED3MM")
      (libsource (lib "eagle-import") (part "L-1334SRT"))
    )
    (comp (ref "D17")
      (value "L-1334SRT")
      (footprint "eagle-import:LED3MM")
      (libsource (lib "eagle-import") (part "L-1334SRT"))
    )
    (comp (ref "D18")
      (value "L-1334SRT")
      (footprint "eagle-import:LED3MM")
      (libsource (lib "eagle-import") (part "L-1334SRT"))
    )
    (comp (ref "D31")
      (value "L-1334SRT")
      (footprint "eagle-import:LED3MM")
      (libsource (lib "eagle-import") (part "L-1334SRT"))
    )
    (comp (ref "D32")
      (value "L-1334SRT")
      (footprint "eagle-import:LED3MM")
      (libsource (lib "eagle-import") (part "L-1334SRT"))
    )
    (comp (ref "D33")
      (value "L-1334SRT")
      (footprint "eagle-import:LED3MM")
      (libsource (lib "eagle-import") (part "L-1334SRT"))
    )
    (comp (ref "D43")
      (value "L-1334SRT")
      (footprint "eagle-import:LED3MM")
      (libsource (lib "eagle-import") (part "L-1334SRT"))
    )
    (comp (ref "D44")
      (value "L-1334SRT")
      (footprint "eagle-import:LED3MM")
      (libsource (lib "eagle-import") (part "L-1334SRT"))
    )
    (comp (ref "D45")
      (value "L-1334SRT")
      (footprint "eagle-import:LED3MM")
      (libsource (lib "eagle-import") (part "L-1334SRT"))
    )
    (comp (ref "Q22")
      (value "2N7000")
      (footprint "eagle-import:TO92-DGS")
      (libsource (lib "eagle-import") (part "2N7000"))
    )
    (comp (ref "Q23")
      (value "2N7000")
      (footprint "eagle-import:TO92-DGS")
      (libsource (lib "eagle-import") (part "2N7000"))
    )
    (comp (ref "Q24")
      (value "2N7000")
      (footprint "eagle-import:TO92-DGS")
      (libsource (lib "eagle-import") (part "2N7000"))
    )
    (comp (ref "Q25")
      (value "2N7000")
      (footprint "eagle-import:TO92-DGS")
      (libsource (lib "eagle-import") (part "2N7000"))
    )
    (comp (ref "Q26")
      (value "2N7000")
      (footprint "eagle-import:TO92-DGS")
      (libsource (lib "eagle-import") (part "2N7000"))
    )
    (comp (ref "Q45")
      (value "2N7000")
      (footprint "eagle-import:TO92-DGS")
      (libsource (lib "eagle-import") (part "2N7000"))
    )
    (comp (ref "Q46")
      (value "2N7000")
      (footprint "eagle-import:TO92-DGS")
      (libsource (lib "eagle-import") (part "2N7000"))
    )
    (comp (ref "Q47")
      (value "2N7000")
      (footprint "eagle-import:TO92-DGS")
      (libsource (lib "eagle-import") (part "2N7000"))
    )
    (comp (ref "Q57")
      (value "2N7000")
      (footprint "eagle-import:TO92-DGS")
      (libsource (lib "eagle-import") (part "2N7000"))
    )
    (comp (ref "Q58")
      (value "2N7000")
      (footprint "eagle-import:TO92-DGS")
      (libsource (lib "eagle-import") (part "2N7000"))
    )
    (comp (ref "Q59")
      (value "2N7000")
      (footprint "eagle-import:TO92-DGS")
      (libsource (lib "eagle-import") (part "2N7000"))
    )
    (comp (ref "R26")
      (value "10k")
      (footprint "eagle-import:R_P2INCH")
      (libsource (lib "eagle-import") (part "R_P2INCH"))
    )
    (comp (ref "R27")
      (value "470")
      (footprint "eagle-import:R_P2INCH")
      (libsource (lib "eagle-import") (part "R_P2INCH"))
    )
    (comp (ref "R28")
      (value "10k")
      (footprint "eagle-import:R_P2INCH")
      (libsource (lib "eagle-import") (part "R_P2INCH"))
    )
    (comp (ref "R29")
      (value "470")
      (footprint "eagle-import:R_P2INCH")
      (libsource (lib "eagle-import") (part "R_P2INCH"))
    )
    (comp (ref "R30")
      (value "470")
      (footprint "eagle-import:R_P2INCH")
      (libsource (lib "eagle-import") (part "R_P2INCH"))
    )
    (comp (ref "R51")
      (value "10k")
      (footprint "eagle-import:R_P2INCH")
      (libsource (lib "eagle-import") (part "R_P2INCH"))
    )
    (comp (ref "R52")
      (value "470")
      (footprint "eagle-import:R_P2INCH")
      (libsource (lib "eagle-import") (part "R_P2INCH"))
    )
    (comp (ref "R53")
      (value "10k")
      (footprint "eagle-import:R_P2INCH")
      (libsource (lib "eagle-import") (part "R_P2INCH"))
    )
    (comp (ref "R54")
      (value "470")
      (footprint "eagle-import:R_P2INCH")
      (libsource (lib "eagle-import") (part "R_P2INCH"))
    )
    (comp (ref "R55")
      (value "470")
      (footprint "eagle-import:R_P2INCH")
      (libsource (lib "eagle-import") (part "R_P2INCH"))
    )
    (comp (ref "R71")
      (value "10k")
      (footprint "eagle-import:R_P2INCH")
      (libsource (lib "eagle-import") (part "R_P2INCH"))
    )
    (comp (ref "R72")
      (value "470")
      (footprint "eagle-import:R_P2INCH")
      (libsource (lib "eagle-import") (part "R_P2INCH"))
    )
    (comp (ref "R73")
      (value "10k")
      (footprint "eagle-import:R_P2INCH")
      (libsource (lib "eagle-import") (part "R_P2INCH"))
    )
    (comp (ref "R74")
      (value "470")
      (footprint "eagle-import:R_P2INCH")
      (libsource (lib "eagle-import") (part "R_P2INCH"))
    )
    (comp (ref "R75")
      (value "470")
      (footprint "eagle-import:R_P2INCH")
      (libsource (lib "eagle-import") (part "R_P2INCH"))
    )
    (comp (ref "D12")
      (value "L-1334SRT")
      (footprint "eagle-import:LED3MM")
      (libsource (lib "eagle-import") (part "L-1334SRT"))
    )
    (comp (ref "D13")
      (value "L-1334SRT")
      (footprint "eagle-import:LED3MM")
      (libsource (lib "eagle-import") (part "L-1334SRT"))
    )
    (comp (ref "D14")
      (value "L-1334SRT")
      (footprint "eagle-import:LED3MM")
      (libsource (lib "eagle-import") (part "L-1334SRT"))
    )
    (comp (ref "D15")
      (value "L-1334SRT")
      (footprint "eagle-import:LED3MM")
      (libsource (lib "eagle-import") (part "L-1334SRT"))
    )
    (comp (ref "D19")
      (value "L-1334SRT")
      (footprint "eagle-import:LED3MM")
      (libsource (lib "eagle-import") (part "L-1334SRT"))
    )
    (comp (ref "D20")
      (value "L-1334SRT")
      (footprint "eagle-import:LED3MM")
      (libsource (lib "eagle-import") (part "L-1334SRT"))
    )
    (comp (ref "D21")
      (value "L-1334SRT")
      (footprint "eagle-import:LED3MM")
      (libsource (lib "eagle-import") (part "L-1334SRT"))
    )
    (comp (ref "D25")
      (value "L-1334SRT")
      (footprint "eagle-import:LED3MM")
      (libsource (lib "eagle-import") (part "L-1334SRT"))
    )
    (comp (ref "Q13")
      (value "2N7000")
      (footprint "eagle-import:TO92-DGS")
      (libsource (lib "eagle-import") (part "2N7000"))
    )
    (comp (ref "Q14")
      (value "2N7000")
      (footprint "eagle-import:TO92-DGS")
      (libsource (lib "eagle-import") (part "2N7000"))
    )
    (comp (ref "Q15")
      (value "2N7000")
      (footprint "eagle-import:TO92-DGS")
      (libsource (lib "eagle-import") (part "2N7000"))
    )
    (comp (ref "Q16")
      (value "2N7000")
      (footprint "eagle-import:TO92-DGS")
      (libsource (lib "eagle-import") (part "2N7000"))
    )
    (comp (ref "Q17")
      (value "2N7000")
      (footprint "eagle-import:TO92-DGS")
      (libsource (lib "eagle-import") (part "2N7000"))
    )
    (comp (ref "Q18")
      (value "2N7000")
      (footprint "eagle-import:TO92-DGS")
      (libsource (lib "eagle-import") (part "2N7000"))
    )
    (comp (ref "Q19")
      (value "2N7000")
      (footprint "eagle-import:TO92-DGS")
      (libsource (lib "eagle-import") (part "2N7000"))
    )
    (comp (ref "Q20")
      (value "2N7000")
      (footprint "eagle-import:TO92-DGS")
      (libsource (lib "eagle-import") (part "2N7000"))
    )
    (comp (ref "Q21")
      (value "2N7000")
      (footprint "eagle-import:TO92-DGS")
      (libsource (lib "eagle-import") (part "2N7000"))
    )
    (comp (ref "Q66")
      (value "2N7000")
      (footprint "eagle-import:TO92-DGS")
      (libsource (lib "eagle-import") (part "2N7000"))
    )
    (comp (ref "Q67")
      (value "2N7000")
      (footprint "eagle-import:TO92-DGS")
      (libsource (lib "eagle-import") (part "2N7000"))
    )
    (comp (ref "Q68")
      (value "2N7000")
      (footprint "eagle-import:TO92-DGS")
      (libsource (lib "eagle-import") (part "2N7000"))
    )
    (comp (ref "Q69")
      (value "2N7000")
      (footprint "eagle-import:TO92-DGS")
      (libsource (lib "eagle-import") (part "2N7000"))
    )
    (comp (ref "Q70")
      (value "2N7000")
      (footprint "eagle-import:TO92-DGS")
      (libsource (lib "eagle-import") (part "2N7000"))
    )
    (comp (ref "Q71")
      (value "2N7000")
      (footprint "eagle-import:TO92-DGS")
      (libsource (lib "eagle-import") (part "2N7000"))
    )
    (comp (ref "Q72")
      (value "2N7000")
      (footprint "eagle-import:TO92-DGS")
      (libsource (lib "eagle-import") (part "2N7000"))
    )
    (comp (ref "R43")
      (value "470")
      (footprint "eagle-import:R_P2INCH")
      (libsource (lib "eagle-import") (part "R_P2INCH"))
    )
    (comp (ref "R44")
      (value "470")
      (footprint "eagle-import:R_P2INCH")
      (libsource (lib "eagle-import") (part "R_P2INCH"))
    )
    (comp (ref "R45")
      (value "470")
      (footprint "eagle-import:R_P2INCH")
      (libsource (lib "eagle-import") (part "R_P2INCH"))
    )
    (comp (ref "R46")
      (value "470")
      (footprint "eagle-import:R_P2INCH")
      (libsource (lib "eagle-import") (part "R_P2INCH"))
    )
    (comp (ref "R47")
      (value "470")
      (footprint "eagle-import:R_P2INCH")
      (libsource (lib "eagle-import") (part "R_P2INCH"))
    )
    (comp (ref "R48")
      (value "470")
      (footprint "eagle-import:R_P2INCH")
      (libsource (lib "eagle-import") (part "R_P2INCH"))
    )
    (comp (ref "R49")
      (value "470")
      (footprint "eagle-import:R_P2INCH")
      (libsource (lib "eagle-import") (part "R_P2INCH"))
    )
    (comp (ref "R50")
      (value "470")
      (footprint "eagle-import:R_P2INCH")
      (libsource (lib "eagle-import") (part "R_P2INCH"))
    )
  )
  (nets
    (net (code "1") (name "+5V") (class "Default")
      (node (ref "C1") (pin "1") (pinfunction "1_1") (pintype "passive"))
      (node (ref "C10") (pin "1") (pinfunction "1_1") (pintype "passive"))
      (node (ref "C2") (pin "1") (pinfunction "1_1") (pintype "passive"))
      (node (ref "C3") (pin "1") (pinfunction "1_1") (pintype "passive"))
      (node (ref "C4") (pin "1") (pinfunction "1_1") (pintype "passive"))
      (node (ref "C5") (pin "1") (pinfunction "1_1") (pintype "passive"))
      (node (ref "C6") (pin "A") (pinfunction "A_A") (pintype "passive"))
      (node (ref "C7") (pin "1") (pinfunction "1_1") (pintype "passive"))
      (node (ref "C8") (pin "1") (pinfunction "1_1") (pintype "passive"))
      (node (ref "C9") (pin "1") (pinfunction "1_1") (pintype "passive"))
      (node (ref "D1") (pin "A") (pinfunction "A_A") (pintype "passive"))
      (node (ref "D10") (pin "A") (pinfunction "A_A") (pintype "passive"))
      (node (ref "D103") (pin "A") (pinfunction "A_A") (pintype "passive"))
      (node (ref "D104") (pin "A") (pinfunction "A_A") (pintype "passive"))
      (node (ref "D105") (pin "A") (pinfunction "A_A") (pintype "passive"))
      (node (ref "D106") (pin "A") (pinfunction "A_A") (pintype "passive"))
      (node (ref "D107") (pin "A") (pinfunction "A_A") (pintype "passive"))
      (node (ref "D108") (pin "A") (pinfunction "A_A") (pintype "passive"))
      (node (ref "D11") (pin "A") (pinfunction "A_A") (pintype "passive"))
      (node (ref "D112") (pin "A") (pinfunction "A_A") (pintype "passive"))
      (node (ref "D113") (pin "A") (pinfunction "A_A") (pintype "passive"))
      (node (ref "D114") (pin "A") (pinfunction "A_A") (pintype "passive"))
      (node (ref "D115") (pin "A") (pinfunction "A_A") (pintype "passive"))
      (node (ref "D116") (pin "A") (pinfunction "A_A") (pintype "passive"))
      (node (ref "D117") (pin "A") (pinfunction "A_A") (pintype "passive"))
      (node (ref "D12") (pin "A") (pinfunction "A_A") (pintype "passive"))
      (node (ref "D121") (pin "A") (pinfunction "A_A") (pintype "passive"))
      (node (ref "D122") (pin "A") (pinfunction "A_A") (pintype "passive"))
      (node (ref "D123") (pin "A") (pinfunction "A_A") (pintype "passive"))
      (node (ref "D124") (pin "A") (pinfunction "A_A") (pintype "passive"))
      (node (ref "D125") (pin "A") (pinfunction "A_A") (pintype "passive"))
      (node (ref "D126") (pin "A") (pinfunction "A_A") (pintype "passive"))
      (node (ref "D13") (pin "A") (pinfunction "A_A") (pintype "passive"))
      (node (ref "D130") (pin "A") (pinfunction "A_A") (pintype "passive"))
      (node (ref "D131") (pin "A") (pinfunction "A_A") (pintype "passive"))
      (node (ref "D132") (pin "A") (pinfunction "A_A") (pintype "passive"))
      (node (ref "D133") (pin "A") (pinfunction "A_A") (pintype "passive"))
      (node (ref "D134") (pin "A") (pinfunction "A_A") (pintype "passive"))
      (node (ref "D135") (pin "A") (pinfunction "A_A") (pintype "passive"))
      (node (ref "D139") (pin "A") (pinfunction "A_A") (pintype "passive"))
      (node (ref "D14") (pin "A") (pinfunction "A_A") (pintype "passive"))
      (node (ref "D140") (pin "A") (pinfunction "A_A") (pintype "passive"))
      (node (ref "D141") (pin "A") (pinfunction "A_A") (pintype "passive"))
      (node (ref "D142") (pin "A") (pinfunction "A_A") (pintype "passive"))
      (node (ref "D143") (pin "A") (pinfunction "A_A") (pintype "passive"))
      (node (ref "D144") (pin "A") (pinfunction "A_A") (pintype "passive"))
      (node (ref "D145") (pin "A") (pinfunction "A_A") (pintype "passive"))
      (node (ref "D146") (pin "A") (pinfunction "A_A") (pintype "passive"))
      (node (ref "D147") (pin "A") (pinfunction "A_A") (pintype "passive"))
      (node (ref "D148") (pin "A") (pinfunction "A_A") (pintype "passive"))
      (node (ref "D149") (pin "A") (pinfunction "A_A") (pintype "passive"))
      (node (ref "D15") (pin "A") (pinfunction "A_A") (pintype "passive"))
      (node (ref "D150") (pin "A") (pinfunction "A_A") (pintype "passive"))
      (node (ref "D151") (pin "A") (pinfunction "A_A") (pintype "passive"))
      (node (ref "D152") (pin "A") (pinfunction "A_A") (pintype "passive"))
      (node (ref "D153") (pin "A") (pinfunction "A_A") (pintype "passive"))
      (node (ref "D155") (pin "A") (pinfunction "A_A") (pintype "passive"))
      (node (ref "D156") (pin "A") (pinfunction "A_A") (pintype "passive"))
      (node (ref "D157") (pin "A") (pinfunction "A_A") (pintype "passive"))
      (node (ref "D158") (pin "A") (pinfunction "A_A") (pintype "passive"))
      (node (ref "D159") (pin "A") (pinfunction "A_A") (pintype "passive"))
      (node (ref "D16") (pin "A") (pinfunction "A_A") (pintype "passive"))
      (node (ref "D160") (pin "A") (pinfunction "A_A") (pintype "passive"))
      (node (ref "D161") (pin "A") (pinfunction "A_A") (pintype "passive"))
      (node (ref "D163") (pin "A") (pinfunction "A_A") (pintype "passive"))
      (node (ref "D164") (pin "A") (pinfunction "A_A") (pintype "passive"))
      (node (ref "D165") (pin "A") (pinfunction "A_A") (pintype "passive"))
      (node (ref "D166") (pin "A") (pinfunction "A_A") (pintype "passive"))
      (node (ref "D167") (pin "A") (pinfunction "A_A") (pintype "passive"))
      (node (ref "D168") (pin "A") (pinfunction "A_A") (pintype "passive"))
      (node (ref "D169") (pin "A") (pinfunction "A_A") (pintype "passive"))
      (node (ref "D17") (pin "A") (pinfunction "A_A") (pintype "passive"))
      (node (ref "D170") (pin "A") (pinfunction "A_A") (pintype "passive"))
      (node (ref "D18") (pin "A") (pinfunction "A_A") (pintype "passive"))
      (node (ref "D19") (pin "A") (pinfunction "A_A") (pintype "passive"))
      (node (ref "D2") (pin "A") (pinfunction "A_A") (pintype "passive"))
      (node (ref "D20") (pin "A") (pinfunction "A_A") (pintype "passive"))
      (node (ref "D21") (pin "A") (pinfunction "A_A") (pintype "passive"))
      (node (ref "D22") (pin "A") (pinfunction "A_A") (pintype "passive"))
      (node (ref "D23") (pin "A") (pinfunction "A_A") (pintype "passive"))
      (node (ref "D24") (pin "A") (pinfunction "A_A") (pintype "passive"))
      (node (ref "D25") (pin "A") (pinfunction "A_A") (pintype "passive"))
      (node (ref "D26") (pin "A") (pinfunction "A_A") (pintype "passive"))
      (node (ref "D27") (pin "A") (pinfunction "A_A") (pintype "passive"))
      (node (ref "D28") (pin "A") (pinfunction "A_A") (pintype "passive"))
      (node (ref "D29") (pin "A") (pinfunction "A_A") (pintype "passive"))
      (node (ref "D3") (pin "A") (pinfunction "A_A") (pintype "passive"))
      (node (ref "D30") (pin "A") (pinfunction "A_A") (pintype "passive"))
      (node (ref "D31") (pin "A") (pinfunction "A_A") (pintype "passive"))
      (node (ref "D32") (pin "A") (pinfunction "A_A") (pintype "passive"))
      (node (ref "D33") (pin "A") (pinfunction "A_A") (pintype "passive"))
      (node (ref "D34") (pin "A") (pinfunction "A_A") (pintype "passive"))
      (node (ref "D35") (pin "A") (pinfunction "A_A") (pintype "passive"))
      (node (ref "D36") (pin "A") (pinfunction "A_A") (pintype "passive"))
      (node (ref "D37") (pin "A") (pinfunction "A_A") (pintype "passive"))
      (node (ref "D38") (pin "A") (pinfunction "A_A") (pintype "passive"))
      (node (ref "D39") (pin "A") (pinfunction "A_A") (pintype "passive"))
      (node (ref "D4") (pin "A") (pinfunction "A_A") (pintype "passive"))
      (node (ref "D40") (pin "A") (pinfunction "A_A") (pintype "passive"))
      (node (ref "D41") (pin "A") (pinfunction "A_A") (pintype "passive"))
      (node (ref "D42") (pin "A") (pinfunction "A_A") (pintype "passive"))
      (node (ref "D43") (pin "A") (pinfunction "A_A") (pintype "passive"))
      (node (ref "D44") (pin "A") (pinfunction "A_A") (pintype "passive"))
      (node (ref "D45") (pin "A") (pinfunction "A_A") (pintype "passive"))
      (node (ref "D46") (pin "A") (pinfunction "A_A") (pintype "passive"))
      (node (ref "D47") (pin "A") (pinfunction "A_A") (pintype "passive"))
      (node (ref "D48") (pin "A") (pinfunction "A_A") (pintype "passive"))
      (node (ref "D49") (pin "A") (pinfunction "A_A") (pintype "passive"))
      (node (ref "D5") (pin "A") (pinfunction "A_A") (pintype "passive"))
      (node (ref "D50") (pin "A") (pinfunction "A_A") (pintype "passive"))
      (node (ref "D51") (pin "A") (pinfunction "A_A") (pintype "passive"))
      (node (ref "D52") (pin "A") (pinfunction "A_A") (pintype "passive"))
      (node (ref "D53") (pin "A") (pinfunction "A_A") (pintype "passive"))
      (node (ref "D54") (pin "A") (pinfunction "A_A") (pintype "passive"))
      (node (ref "D55") (pin "A") (pinfunction "A_A") (pintype "passive"))
      (node (ref "D56") (pin "A") (pinfunction "A_A") (pintype "passive"))
      (node (ref "D57") (pin "A") (pinfunction "A_A") (pintype "passive"))
      (node (ref "D58") (pin "A") (pinfunction "A_A") (pintype "passive"))
      (node (ref "D59") (pin "A") (pinfunction "A_A") (pintype "passive"))
      (node (ref "D6") (pin "A") (pinfunction "A_A") (pintype "passive"))
      (node (ref "D61") (pin "A") (pinfunction "A_A") (pintype "passive"))
      (node (ref "D62") (pin "A") (pinfunction "A_A") (pintype "passive"))
      (node (ref "D63") (pin "A") (pinfunction "A_A") (pintype "passive"))
      (node (ref "D67") (pin "A") (pinfunction "A_A") (pintype "passive"))
      (node (ref "D68") (pin "A") (pinfunction "A_A") (pintype "passive"))
      (node (ref "D69") (pin "A") (pinfunction "A_A") (pintype "passive"))
      (node (ref "D7") (pin "A") (pinfunction "A_A") (pintype "passive"))
      (node (ref "D73") (pin "A") (pinfunction "A_A") (pintype "passive"))
      (node (ref "D74") (pin "A") (pinfunction "A_A") (pintype "passive"))
      (node (ref "D75") (pin "A") (pinfunction "A_A") (pintype "passive"))
      (node (ref "D79") (pin "A") (pinfunction "A_A") (pintype "passive"))
      (node (ref "D8") (pin "A") (pinfunction "A_A") (pintype "passive"))
      (node (ref "D80") (pin "A") (pinfunction "A_A") (pintype "passive"))
      (node (ref "D81") (pin "A") (pinfunction "A_A") (pintype "passive"))
      (node (ref "D85") (pin "A") (pinfunction "A_A") (pintype "passive"))
      (node (ref "D86") (pin "A") (pinfunction "A_A") (pintype "passive"))
      (node (ref "D87") (pin "A") (pinfunction "A_A") (pintype "passive"))
      (node (ref "D9") (pin "A") (pinfunction "A_A") (pintype "passive"))
      (node (ref "D94") (pin "A") (pinfunction "A_A") (pintype "passive"))
      (node (ref "D95") (pin "A") (pinfunction "A_A") (pintype "passive"))
      (node (ref "D96") (pin "A") (pinfunction "A_A") (pintype "passive"))
      (node (ref "D97") (pin "A") (pinfunction "A_A") (pintype "passive"))
      (node (ref "D98") (pin "A") (pinfunction "A_A") (pintype "passive"))
      (node (ref "D99") (pin "A") (pinfunction "A_A") (pintype "passive"))
      (node (ref "PP1") (pin "1") (pinfunction "P$1_1") (pintype "bidirectional"))
      (node (ref "R1") (pin "2") (pinfunction "2_2") (pintype "passive"))
      (node (ref "R10") (pin "2") (pinfunction "2_2") (pintype "passive"))
      (node (ref "R100") (pin "2") (pinfunction "2_2") (pintype "passive"))
      (node (ref "R101") (pin "2") (pinfunction "2_2") (pintype "passive"))
      (node (ref "R103") (pin "2") (pinfunction "2_2") (pintype "passive"))
      (node (ref "R107") (pin "2") (pinfunction "2_2") (pintype "passive"))
      (node (ref "R109") (pin "2") (pinfunction "2_2") (pintype "passive"))
      (node (ref "R11") (pin "2") (pinfunction "2_2") (pintype "passive"))
      (node (ref "R111") (pin "2") (pinfunction "2_2") (pintype "passive"))
      (node (ref "R113") (pin "2") (pinfunction "2_2") (pintype "passive"))
      (node (ref "R116") (pin "2") (pinfunction "2_2") (pintype "passive"))
      (node (ref "R118") (pin "2") (pinfunction "2_2") (pintype "passive"))
      (node (ref "R12") (pin "2") (pinfunction "2_2") (pintype "passive"))
      (node (ref "R121") (pin "2") (pinfunction "2_2") (pintype "passive"))
      (node (ref "R123") (pin "2") (pinfunction "2_2") (pintype "passive"))
      (node (ref "R13") (pin "2") (pinfunction "2_2") (pintype "passive"))
      (node (ref "R131") (pin "2") (pinfunction "2_2") (pintype "passive"))
      (node (ref "R133") (pin "2") (pinfunction "2_2") (pintype "passive"))
      (node (ref "R14") (pin "2") (pinfunction "2_2") (pintype "passive"))
      (node (ref "R141") (pin "2") (pinfunction "2_2") (pintype "passive"))
      (node (ref "R143") (pin "2") (pinfunction "2_2") (pintype "passive"))
      (node (ref "R15") (pin "2") (pinfunction "2_2") (pintype "passive"))
      (node (ref "R156") (pin "2") (pinfunction "2_2") (pintype "passive"))
      (node (ref "R158") (pin "2") (pinfunction "2_2") (pintype "passive"))
      (node (ref "R161") (pin "2") (pinfunction "2_2") (pintype "passive"))
      (node (ref "R163") (pin "2") (pinfunction "2_2") (pintype "passive"))
      (node (ref "R171") (pin "2") (pinfunction "2_2") (pintype "passive"))
      (node (ref "R173") (pin "2") (pinfunction "2_2") (pintype "passive"))
      (node (ref "R176") (pin "2") (pinfunction "2_2") (pintype "passive"))
      (node (ref "R178") (pin "2") (pinfunction "2_2") (pintype "passive"))
      (node (ref "R186") (pin "2") (pinfunction "2_2") (pintype "passive"))
      (node (ref "R188") (pin "2") (pinfunction "2_2") (pintype "passive"))
      (node (ref "R191") (pin "2") (pinfunction "2_2") (pintype "passive"))
      (node (ref "R193") (pin "2") (pinfunction "2_2") (pintype "passive"))
      (node (ref "R2") (pin "2") (pinfunction "2_2") (pintype "passive"))
      (node (ref "R201") (pin "2") (pinfunction "2_2") (pintype "passive"))
      (node (ref "R203") (pin "2") (pinfunction "2_2") (pintype "passive"))
      (node (ref "R206") (pin "2") (pinfunction "2_2") (pintype "passive"))
      (node (ref "R208") (pin "2") (pinfunction "2_2") (pintype "passive"))
      (node (ref "R216") (pin "2") (pinfunction "2_2") (pintype "passive"))
      (node (ref "R218") (pin "2") (pinfunction "2_2") (pintype "passive"))
      (node (ref "R221") (pin "2") (pinfunction "2_2") (pintype "passive"))
      (node (ref "R223") (pin "2") (pinfunction "2_2") (pintype "passive"))
      (node (ref "R231") (pin "2") (pinfunction "2_2") (pintype "passive"))
      (node (ref "R233") (pin "2") (pinfunction "2_2") (pintype "passive"))
      (node (ref "R236") (pin "2") (pinfunction "2_2") (pintype "passive"))
      (node (ref "R238") (pin "2") (pinfunction "2_2") (pintype "passive"))
      (node (ref "R241") (pin "2") (pinfunction "2_2") (pintype "passive"))
      (node (ref "R242") (pin "2") (pinfunction "2_2") (pintype "passive"))
      (node (ref "R243") (pin "2") (pinfunction "2_2") (pintype "passive"))
      (node (ref "R244") (pin "2") (pinfunction "2_2") (pintype "passive"))
      (node (ref "R245") (pin "2") (pinfunction "2_2") (pintype "passive"))
      (node (ref "R246") (pin "2") (pinfunction "2_2") (pintype "passive"))
      (node (ref "R247") (pin "2") (pinfunction "2_2") (pintype "passive"))
      (node (ref "R248") (pin "2") (pinfunction "2_2") (pintype "passive"))
      (node (ref "R249") (pin "2") (pinfunction "2_2") (pintype "passive"))
      (node (ref "R250") (pin "2") (pinfunction "2_2") (pintype "passive"))
      (node (ref "R251") (pin "2") (pinfunction "2_2") (pintype "passive"))
      (node (ref "R252") (pin "2") (pinfunction "2_2") (pintype "passive"))
      (node (ref "R253") (pin "2") (pinfunction "2_2") (pintype "passive"))
      (node (ref "R254") (pin "2") (pinfunction "2_2") (pintype "passive"))
      (node (ref "R255") (pin "2") (pinfunction "2_2") (pintype "passive"))
      (node (ref "R256") (pin "2") (pinfunction "2_2") (pintype "passive"))
      (node (ref "R26") (pin "2") (pinfunction "2_2") (pintype "passive"))
      (node (ref "R28") (pin "2") (pinfunction "2_2") (pintype "passive"))
      (node (ref "R34") (pin "2") (pinfunction "2_2") (pintype "passive"))
      (node (ref "R35") (pin "2") (pinfunction "2_2") (pintype "passive"))
      (node (ref "R36") (pin "2") (pinfunction "2_2") (pintype "passive"))
      (node (ref "R38") (pin "2") (pinfunction "2_2") (pintype "passive"))
      (node (ref "R41") (pin "2") (pinfunction "2_2") (pintype "passive"))
      (node (ref "R5") (pin "2") (pinfunction "2_2") (pintype "passive"))
      (node (ref "R51") (pin "2") (pinfunction "2_2") (pintype "passive"))
      (node (ref "R53") (pin "2") (pinfunction "2_2") (pintype "passive"))
      (node (ref "R61") (pin "2") (pinfunction "2_2") (pintype "passive"))
      (node (ref "R63") (pin "2") (pinfunction "2_2") (pintype "passive"))
      (node (ref "R66") (pin "2") (pinfunction "2_2") (pintype "passive"))
      (node (ref "R68") (pin "2") (pinfunction "2_2") (pintype "passive"))
      (node (ref "R7") (pin "2") (pinfunction "2_2") (pintype "passive"))
      (node (ref "R71") (pin "2") (pinfunction "2_2") (pintype "passive"))
      (node (ref "R73") (pin "2") (pinfunction "2_2") (pintype "passive"))
      (node (ref "R89") (pin "2") (pinfunction "2_2") (pintype "passive"))
      (node (ref "R9") (pin "2") (pinfunction "2_2") (pintype "passive"))
      (node (ref "R91") (pin "2") (pinfunction "2_2") (pintype "passive"))
      (node (ref "R93") (pin "2") (pinfunction "2_2") (pintype "passive"))
      (node (ref "R96") (pin "2") (pinfunction "2_2") (pintype "passive"))
      (node (ref "R98") (pin "2") (pinfunction "2_2") (pintype "passive"))
    )
    (net (code "2") (name "AND0") (class "Default")
      (node (ref "Q5") (pin "G") (pinfunction "G_G") (pintype "passive"))
      (node (ref "Q59") (pin "D") (pinfunction "D_D") (pintype "passive"))
      (node (ref "R73") (pin "1") (pinfunction "1_1") (pintype "passive"))
    )
    (net (code "3") (name "AND0_N") (class "Default")
      (node (ref "Q57") (pin "D") (pinfunction "D_D") (pintype "passive"))
      (node (ref "Q59") (pin "G") (pinfunction "G_G") (pintype "passive"))
      (node (ref "R16") (pin "1") (pinfunction "1_1") (pintype "passive"))
      (node (ref "R71") (pin "1") (pinfunction "1_1") (pintype "passive"))
      (node (ref "R72") (pin "1") (pinfunction "1_1") (pintype "passive"))
    )
    (net (code "4") (name "AND1") (class "Default")
      (node (ref "Q56") (pin "D") (pinfunction "D_D") (pintype "passive"))
      (node (ref "Q6") (pin "G") (pinfunction "G_G") (pintype "passive"))
      (node (ref "R68") (pin "1") (pinfunction "1_1") (pintype "passive"))
    )
    (net (code "5") (name "AND1_N") (class "Default")
      (node (ref "Q54") (pin "D") (pinfunction "D_D") (pintype "passive"))
      (node (ref "Q56") (pin "G") (pinfunction "G_G") (pintype "passive"))
      (node (ref "R17") (pin "1") (pinfunction "1_1") (pintype "passive"))
      (node (ref "R66") (pin "1") (pinfunction "1_1") (pintype "passive"))
      (node (ref "R67") (pin "1") (pinfunction "1_1") (pintype "passive"))
    )
    (net (code "6") (name "AND2") (class "Default")
      (node (ref "Q147") (pin "D") (pinfunction "D_D") (pintype "passive"))
      (node (ref "Q7") (pin "G") (pinfunction "G_G") (pintype "passive"))
      (node (ref "R163") (pin "1") (pinfunction "1_1") (pintype "passive"))
    )
    (net (code "7") (name "AND2_N") (class "Default")
      (node (ref "Q145") (pin "D") (pinfunction "D_D") (pintype "passive"))
      (node (ref "Q147") (pin "G") (pinfunction "G_G") (pintype "passive"))
      (node (ref "R161") (pin "1") (pinfunction "1_1") (pintype "passive"))
      (node (ref "R162") (pin "1") (pinfunction "1_1") (pintype "passive"))
      (node (ref "R18") (pin "1") (pinfunction "1_1") (pintype "passive"))
    )
    (net (code "8") (name "AND3") (class "Default")
      (node (ref "Q156") (pin "D") (pinfunction "D_D") (pintype "passive"))
      (node (ref "Q8") (pin "G") (pinfunction "G_G") (pintype "passive"))
      (node (ref "R178") (pin "1") (pinfunction "1_1") (pintype "passive"))
    )
    (net (code "9") (name "AND3_N") (class "Default")
      (node (ref "Q154") (pin "D") (pinfunction "D_D") (pintype "passive"))
      (node (ref "Q156") (pin "G") (pinfunction "G_G") (pintype "passive"))
      (node (ref "R176") (pin "1") (pinfunction "1_1") (pintype "passive"))
      (node (ref "R177") (pin "1") (pinfunction "1_1") (pintype "passive"))
      (node (ref "R19") (pin "1") (pinfunction "1_1") (pintype "passive"))
    )
    (net (code "10") (name "AND4") (class "Default")
      (node (ref "Q165") (pin "D") (pinfunction "D_D") (pintype "passive"))
      (node (ref "Q9") (pin "G") (pinfunction "G_G") (pintype "passive"))
      (node (ref "R193") (pin "1") (pinfunction "1_1") (pintype "passive"))
    )
    (net (code "11") (name "AND4_N") (class "Default")
      (node (ref "Q163") (pin "D") (pinfunction "D_D") (pintype "passive"))
      (node (ref "Q165") (pin "G") (pinfunction "G_G") (pintype "passive"))
      (node (ref "R191") (pin "1") (pinfunction "1_1") (pintype "passive"))
      (node (ref "R192") (pin "1") (pinfunction "1_1") (pintype "passive"))
      (node (ref "R20") (pin "1") (pinfunction "1_1") (pintype "passive"))
    )
    (net (code "12") (name "AND5") (class "Default")
      (node (ref "Q10") (pin "G") (pinfunction "G_G") (pintype "passive"))
      (node (ref "Q174") (pin "D") (pinfunction "D_D") (pintype "passive"))
      (node (ref "R208") (pin "1") (pinfunction "1_1") (pintype "passive"))
    )
    (net (code "13") (name "AND5_N") (class "Default")
      (node (ref "Q172") (pin "D") (pinfunction "D_D") (pintype "passive"))
      (node (ref "Q174") (pin "G") (pinfunction "G_G") (pintype "passive"))
      (node (ref "R206") (pin "1") (pinfunction "1_1") (pintype "passive"))
      (node (ref "R207") (pin "1") (pinfunction "1_1") (pintype "passive"))
      (node (ref "R21") (pin "1") (pinfunction "1_1") (pintype "passive"))
    )
    (net (code "14") (name "AND6") (class "Default")
      (node (ref "Q11") (pin "G") (pinfunction "G_G") (pintype "passive"))
      (node (ref "Q183") (pin "D") (pinfunction "D_D") (pintype "passive"))
      (node (ref "R223") (pin "1") (pinfunction "1_1") (pintype "passive"))
    )
    (net (code "15") (name "AND6_N") (class "Default")
      (node (ref "Q181") (pin "D") (pinfunction "D_D") (pintype "passive"))
      (node (ref "Q183") (pin "G") (pinfunction "G_G") (pintype "passive"))
      (node (ref "R22") (pin "1") (pinfunction "1_1") (pintype "passive"))
      (node (ref "R221") (pin "1") (pinfunction "1_1") (pintype "passive"))
      (node (ref "R222") (pin "1") (pinfunction "1_1") (pintype "passive"))
    )
    (net (code "16") (name "AND7") (class "Default")
      (node (ref "Q12") (pin "G") (pinfunction "G_G") (pintype "passive"))
      (node (ref "Q192") (pin "D") (pinfunction "D_D") (pintype "passive"))
      (node (ref "R238") (pin "1") (pinfunction "1_1") (pintype "passive"))
    )
    (net (code "17") (name "AND7_N") (class "Default")
      (node (ref "Q190") (pin "D") (pinfunction "D_D") (pintype "passive"))
      (node (ref "Q192") (pin "G") (pinfunction "G_G") (pintype "passive"))
      (node (ref "R23") (pin "1") (pinfunction "1_1") (pintype "passive"))
      (node (ref "R236") (pin "1") (pinfunction "1_1") (pintype "passive"))
      (node (ref "R237") (pin "1") (pinfunction "1_1") (pintype "passive"))
    )
    (net (code "18") (name "DO_AND") (class "Default")
      (node (ref "Q4") (pin "G") (pinfunction "G_G") (pintype "passive"))
      (node (ref "Q61") (pin "D") (pinfunction "D_D") (pintype "passive"))
      (node (ref "Q64") (pin "G") (pinfunction "G_G") (pintype "passive"))
      (node (ref "Q84") (pin "G") (pinfunction "G_G") (pintype "passive"))
      (node (ref "Q85") (pin "G") (pinfunction "G_G") (pintype "passive"))
      (node (ref "Q86") (pin "G") (pinfunction "G_G") (pintype "passive"))
      (node (ref "Q87") (pin "G") (pinfunction "G_G") (pintype "passive"))
      (node (ref "Q88") (pin "G") (pinfunction "G_G") (pintype "passive"))
      (node (ref "Q94") (pin "G") (pinfunction "G_G") (pintype "passive"))
      (node (ref "R34") (pin "1") (pinfunction "1_1") (pintype "passive"))
    )
    (net (code "19") (name "DO_AND_IN") (class "Default")
      (node (ref "Q2") (pin "G") (pinfunction "G_G") (pintype "passive"))
      (node (ref "TP1") (pin "P$1") (pinfunction "P$1_P$1") (pintype "bidirectional"))
    )
    (net (code "20") (name "DO_AND_N") (class "Default")
      (node (ref "Q2") (pin "D") (pinfunction "D_D") (pintype "passive"))
      (node (ref "Q61") (pin "G") (pinfunction "G_G") (pintype "passive"))
      (node (ref "R2") (pin "1") (pinfunction "1_1") (pintype "passive"))
      (node (ref "R3") (pin "1") (pinfunction "1_1") (pintype "passive"))
      (node (ref "R31") (pin "1") (pinfunction "1_1") (pintype "passive"))
    )
    (net (code "21") (name "DO_OR") (class "Default")
      (node (ref "Q13") (pin "G") (pinfunction "G_G") (pintype "passive"))
      (node (ref "Q62") (pin "D") (pinfunction "D_D") (pintype "passive"))
      (node (ref "Q66") (pin "G") (pinfunction "G_G") (pintype "passive"))
      (node (ref "Q67") (pin "G") (pinfunction "G_G") (pintype "passive"))
      (node (ref "Q68") (pin "G") (pinfunction "G_G") (pintype "passive"))
      (node (ref "Q69") (pin "G") (pinfunction "G_G") (pintype "passive"))
      (node (ref "Q70") (pin "G") (pinfunction "G_G") (pintype "passive"))
      (node (ref "Q71") (pin "G") (pinfunction "G_G") (pintype "passive"))
      (node (ref "Q72") (pin "G") (pinfunction "G_G") (pintype "passive"))
      (node (ref "R35") (pin "1") (pinfunction "1_1") (pintype "passive"))
    )
    (net (code "22") (name "DO_OR_IN") (class "Default")
      (node (ref "Q3") (pin "G") (pinfunction "G_G") (pintype "passive"))
      (node (ref "TP2") (pin "P$1") (pinfunction "P$1_P$1") (pintype "bidirectional"))
    )
    (net (code "23") (name "DO_OR_N") (class "Default")
      (node (ref "Q3") (pin "D") (pinfunction "D_D") (pintype "passive"))
      (node (ref "Q62") (pin "G") (pinfunction "G_G") (pintype "passive"))
      (node (ref "R32") (pin "1") (pinfunction "1_1") (pintype "passive"))
      (node (ref "R5") (pin "1") (pinfunction "1_1") (pintype "passive"))
      (node (ref "R6") (pin "1") (pinfunction "1_1") (pintype "passive"))
    )
    (net (code "24") (name "DO_XOR") (class "Default")
      (node (ref "Q27") (pin "G") (pinfunction "G_G") (pintype "passive"))
      (node (ref "Q63") (pin "D") (pinfunction "D_D") (pintype "passive"))
      (node (ref "Q65") (pin "G") (pinfunction "G_G") (pintype "passive"))
      (node (ref "Q73") (pin "G") (pinfunction "G_G") (pintype "passive"))
      (node (ref "Q74") (pin "G") (pinfunction "G_G") (pintype "passive"))
      (node (ref "Q75") (pin "G") (pinfunction "G_G") (pintype "passive"))
      (node (ref "Q76") (pin "G") (pinfunction "G_G") (pintype "passive"))
      (node (ref "Q77") (pin "G") (pinfunction "G_G") (pintype "passive"))
      (node (ref "Q78") (pin "G") (pinfunction "G_G") (pintype "passive"))
      (node (ref "R41") (pin "1") (pinfunction "1_1") (pintype "passive"))
    )
    (net (code "25") (name "DO_XOR_IN") (class "Default")
      (node (ref "Q1") (pin "G") (pinfunction "G_G") (pintype "passive"))
      (node (ref "TP3") (pin "P$1") (pinfunction "P$1_P$1") (pintype "bidirectional"))
    )
    (net (code "26") (name "DO_XOR_N") (class "Default")
      (node (ref "Q1") (pin "D") (pinfunction "D_D") (pintype "passive"))
      (node (ref "Q63") (pin "G") (pinfunction "G_G") (pintype "passive"))
      (node (ref "R1") (pin "1") (pinfunction "1_1") (pintype "passive"))
      (node (ref "R33") (pin "1") (pinfunction "1_1") (pintype "passive"))
      (node (ref "R4") (pin "1") (pinfunction "1_1") (pintype "passive"))
    )
    (net (code "27") (name "GND") (class "Default")
      (node (ref "C1") (pin "2") (pinfunction "2_2") (pintype "passive"))
      (node (ref "C10") (pin "2") (pinfunction "2_2") (pintype "passive"))
      (node (ref "C2") (pin "2") (pinfunction "2_2") (pintype "passive"))
      (node (ref "C3") (pin "2") (pinfunction "2_2") (pintype "passive"))
      (node (ref "C4") (pin "2") (pinfunction "2_2") (pintype "passive"))
      (node (ref "C5") (pin "2") (pinfunction "2_2") (pintype "passive"))
      (node (ref "C6") (pin "K") (pinfunction "K_K") (pintype "passive"))
      (node (ref "C7") (pin "2") (pinfunction "2_2") (pintype "passive"))
      (node (ref "C8") (pin "2") (pinfunction "2_2") (pintype "passive"))
      (node (ref "C9") (pin "2") (pinfunction "2_2") (pintype "passive"))
      (node (ref "J1") (pin "1") (pinfunction "1_1") (pintype "bidirectional"))
      (node (ref "J1") (pin "10") (pinfunction "10_10") (pintype "bidirectional"))
      (node (ref "J1") (pin "11") (pinfunction "11_11") (pintype "bidirectional"))
      (node (ref "J1") (pin "20") (pinfunction "20_20") (pintype "bidirectional"))
      (node (ref "J2") (pin "1") (pinfunction "1_1") (pintype "bidirectional"))
      (node (ref "J2") (pin "10") (pinfunction "10_10") (pintype "bidirectional"))
      (node (ref "J2") (pin "11") (pinfunction "11_11") (pintype "bidirectional"))
      (node (ref "J2") (pin "20") (pinfunction "20_20") (pintype "bidirectional"))
      (node (ref "J3") (pin "1") (pinfunction "1_1") (pintype "bidirectional"))
      (node (ref "J3") (pin "10") (pinfunction "10_10") (pintype "bidirectional"))
      (node (ref "J3") (pin "11") (pinfunction "11_11") (pintype "bidirectional"))
      (node (ref "J3") (pin "20") (pinfunction "20_20") (pintype "bidirectional"))
      (node (ref "J4") (pin "1") (pinfunction "1_1") (pintype "bidirectional"))
      (node (ref "J4") (pin "10") (pinfunction "10_10") (pintype "bidirectional"))
      (node (ref "J4") (pin "19") (pinfunction "19_19") (pintype "bidirectional"))
      (node (ref "J4") (pin "28") (pinfunction "28_28") (pintype "bidirectional"))
      (node (ref "PP2") (pin "1") (pinfunction "P$1_1") (pintype "bidirectional"))
      (node (ref "Q1") (pin "S") (pinfunction "S_S") (pintype "passive"))
      (node (ref "Q100") (pin "S") (pinfunction "S_S") (pintype "passive"))
      (node (ref "Q102") (pin "S") (pinfunction "S_S") (pintype "passive"))
      (node (ref "Q103") (pin "S") (pinfunction "S_S") (pintype "passive"))
      (node (ref "Q110") (pin "S") (pinfunction "S_S") (pintype "passive"))
      (node (ref "Q112") (pin "S") (pinfunction "S_S") (pintype "passive"))
      (node (ref "Q113") (pin "S") (pinfunction "S_S") (pintype "passive"))
      (node (ref "Q120") (pin "S") (pinfunction "S_S") (pintype "passive"))
      (node (ref "Q122") (pin "S") (pinfunction "S_S") (pintype "passive"))
      (node (ref "Q123") (pin "S") (pinfunction "S_S") (pintype "passive"))
      (node (ref "Q13") (pin "S") (pinfunction "S_S") (pintype "passive"))
      (node (ref "Q130") (pin "S") (pinfunction "S_S") (pintype "passive"))
      (node (ref "Q132") (pin "S") (pinfunction "S_S") (pintype "passive"))
      (node (ref "Q133") (pin "S") (pinfunction "S_S") (pintype "passive"))
      (node (ref "Q142") (pin "S") (pinfunction "S_S") (pintype "passive"))
      (node (ref "Q143") (pin "S") (pinfunction "S_S") (pintype "passive"))
      (node (ref "Q144") (pin "S") (pinfunction "S_S") (pintype "passive"))
      (node (ref "Q146") (pin "S") (pinfunction "S_S") (pintype "passive"))
      (node (ref "Q147") (pin "S") (pinfunction "S_S") (pintype "passive"))
      (node (ref "Q151") (pin "S") (pinfunction "S_S") (pintype "passive"))
      (node (ref "Q152") (pin "S") (pinfunction "S_S") (pintype "passive"))
      (node (ref "Q153") (pin "S") (pinfunction "S_S") (pintype "passive"))
      (node (ref "Q155") (pin "S") (pinfunction "S_S") (pintype "passive"))
      (node (ref "Q156") (pin "S") (pinfunction "S_S") (pintype "passive"))
      (node (ref "Q160") (pin "S") (pinfunction "S_S") (pintype "passive"))
      (node (ref "Q161") (pin "S") (pinfunction "S_S") (pintype "passive"))
      (node (ref "Q162") (pin "S") (pinfunction "S_S") (pintype "passive"))
      (node (ref "Q164") (pin "S") (pinfunction "S_S") (pintype "passive"))
      (node (ref "Q165") (pin "S") (pinfunction "S_S") (pintype "passive"))
      (node (ref "Q169") (pin "S") (pinfunction "S_S") (pintype "passive"))
      (node (ref "Q170") (pin "S") (pinfunction "S_S") (pintype "passive"))
      (node (ref "Q171") (pin "S") (pinfunction "S_S") (pintype "passive"))
      (node (ref "Q173") (pin "S") (pinfunction "S_S") (pintype "passive"))
      (node (ref "Q174") (pin "S") (pinfunction "S_S") (pintype "passive"))
      (node (ref "Q178") (pin "S") (pinfunction "S_S") (pintype "passive"))
      (node (ref "Q179") (pin "S") (pinfunction "S_S") (pintype "passive"))
      (node (ref "Q180") (pin "S") (pinfunction "S_S") (pintype "passive"))
      (node (ref "Q182") (pin "S") (pinfunction "S_S") (pintype "passive"))
      (node (ref "Q183") (pin "S") (pinfunction "S_S") (pintype "passive"))
      (node (ref "Q187") (pin "S") (pinfunction "S_S") (pintype "passive"))
      (node (ref "Q188") (pin "S") (pinfunction "S_S") (pintype "passive"))
      (node (ref "Q189") (pin "S") (pinfunction "S_S") (pintype "passive"))
      (node (ref "Q191") (pin "S") (pinfunction "S_S") (pintype "passive"))
      (node (ref "Q192") (pin "S") (pinfunction "S_S") (pintype "passive"))
      (node (ref "Q193") (pin "S") (pinfunction "S_S") (pintype "passive"))
      (node (ref "Q194") (pin "S") (pinfunction "S_S") (pintype "passive"))
      (node (ref "Q195") (pin "S") (pinfunction "S_S") (pintype "passive"))
      (node (ref "Q196") (pin "S") (pinfunction "S_S") (pintype "passive"))
      (node (ref "Q197") (pin "S") (pinfunction "S_S") (pintype "passive"))
      (node (ref "Q198") (pin "S") (pinfunction "S_S") (pintype "passive"))
      (node (ref "Q199") (pin "S") (pinfunction "S_S") (pintype "passive"))
      (node (ref "Q2") (pin "S") (pinfunction "S_S") (pintype "passive"))
      (node (ref "Q200") (pin "S") (pinfunction "S_S") (pintype "passive"))
      (node (ref "Q201") (pin "S") (pinfunction "S_S") (pintype "passive"))
      (node (ref "Q202") (pin "S") (pinfunction "S_S") (pintype "passive"))
      (node (ref "Q203") (pin "S") (pinfunction "S_S") (pintype "passive"))
      (node (ref "Q204") (pin "S") (pinfunction "S_S") (pintype "passive"))
      (node (ref "Q205") (pin "S") (pinfunction "S_S") (pintype "passive"))
      (node (ref "Q206") (pin "S") (pinfunction "S_S") (pintype "passive"))
      (node (ref "Q207") (pin "S") (pinfunction "S_S") (pintype "passive"))
      (node (ref "Q208") (pin "S") (pinfunction "S_S") (pintype "passive"))
      (node (ref "Q23") (pin "S") (pinfunction "S_S") (pintype "passive"))
      (node (ref "Q25") (pin "S") (pinfunction "S_S") (pintype "passive"))
      (node (ref "Q26") (pin "S") (pinfunction "S_S") (pintype "passive"))
      (node (ref "Q27") (pin "S") (pinfunction "S_S") (pintype "passive"))
      (node (ref "Q3") (pin "S") (pinfunction "S_S") (pintype "passive"))
      (node (ref "Q33") (pin "S") (pinfunction "S_S") (pintype "passive"))
      (node (ref "Q35") (pin "S") (pinfunction "S_S") (pintype "passive"))
      (node (ref "Q36") (pin "S") (pinfunction "S_S") (pintype "passive"))
      (node (ref "Q4") (pin "S") (pinfunction "S_S") (pintype "passive"))
      (node (ref "Q41") (pin "S") (pinfunction "S_S") (pintype "passive"))
      (node (ref "Q42") (pin "S") (pinfunction "S_S") (pintype "passive"))
      (node (ref "Q43") (pin "S") (pinfunction "S_S") (pintype "passive"))
      (node (ref "Q44") (pin "S") (pinfunction "S_S") (pintype "passive"))
      (node (ref "Q45") (pin "S") (pinfunction "S_S") (pintype "passive"))
      (node (ref "Q46") (pin "S") (pinfunction "S_S") (pintype "passive"))
      (node (ref "Q47") (pin "S") (pinfunction "S_S") (pintype "passive"))
      (node (ref "Q48") (pin "S") (pinfunction "S_S") (pintype "passive"))
      (node (ref "Q49") (pin "S") (pinfunction "S_S") (pintype "passive"))
      (node (ref "Q50") (pin "S") (pinfunction "S_S") (pintype "passive"))
      (node (ref "Q51") (pin "S") (pinfunction "S_S") (pintype "passive"))
      (node (ref "Q52") (pin "S") (pinfunction "S_S") (pintype "passive"))
      (node (ref "Q53") (pin "S") (pinfunction "S_S") (pintype "passive"))
      (node (ref "Q55") (pin "S") (pinfunction "S_S") (pintype "passive"))
      (node (ref "Q56") (pin "S") (pinfunction "S_S") (pintype "passive"))
      (node (ref "Q58") (pin "S") (pinfunction "S_S") (pintype "passive"))
      (node (ref "Q59") (pin "S") (pinfunction "S_S") (pintype "passive"))
      (node (ref "Q60") (pin "S") (pinfunction "S_S") (pintype "passive"))
      (node (ref "Q61") (pin "S") (pinfunction "S_S") (pintype "passive"))
      (node (ref "Q62") (pin "S") (pinfunction "S_S") (pintype "passive"))
      (node (ref "Q63") (pin "S") (pinfunction "S_S") (pintype "passive"))
      (node (ref "Q64") (pin "S") (pinfunction "S_S") (pintype "passive"))
      (node (ref "Q65") (pin "S") (pinfunction "S_S") (pintype "passive"))
      (node (ref "Q66") (pin "S") (pinfunction "S_S") (pintype "passive"))
      (node (ref "Q67") (pin "S") (pinfunction "S_S") (pintype "passive"))
      (node (ref "Q68") (pin "S") (pinfunction "S_S") (pintype "passive"))
      (node (ref "Q69") (pin "S") (pinfunction "S_S") (pintype "passive"))
      (node (ref "Q70") (pin "S") (pinfunction "S_S") (pintype "passive"))
      (node (ref "Q71") (pin "S") (pinfunction "S_S") (pintype "passive"))
      (node (ref "Q72") (pin "S") (pinfunction "S_S") (pintype "passive"))
      (node (ref "Q73") (pin "S") (pinfunction "S_S") (pintype "passive"))
      (node (ref "Q74") (pin "S") (pinfunction "S_S") (pintype "passive"))
      (node (ref "Q75") (pin "S") (pinfunction "S_S") (pintype "passive"))
      (node (ref "Q76") (pin "S") (pinfunction "S_S") (pintype "passive"))
      (node (ref "Q77") (pin "S") (pinfunction "S_S") (pintype "passive"))
      (node (ref "Q78") (pin "S") (pinfunction "S_S") (pintype "passive"))
      (node (ref "Q80") (pin "S") (pinfunction "S_S") (pintype "passive"))
      (node (ref "Q82") (pin "S") (pinfunction "S_S") (pintype "passive"))
      (node (ref "Q83") (pin "S") (pinfunction "S_S") (pintype "passive"))
      (node (ref "Q84") (pin "S") (pinfunction "S_S") (pintype "passive"))
      (node (ref "Q85") (pin "S") (pinfunction "S_S") (pintype "passive"))
      (node (ref "Q86") (pin "S") (pinfunction "S_S") (pintype "passive"))
      (node (ref "Q87") (pin "S") (pinfunction "S_S") (pintype "passive"))
      (node (ref "Q88") (pin "S") (pinfunction "S_S") (pintype "passive"))
      (node (ref "Q90") (pin "S") (pinfunction "S_S") (pintype "passive"))
      (node (ref "Q92") (pin "S") (pinfunction "S_S") (pintype "passive"))
      (node (ref "Q93") (pin "S") (pinfunction "S_S") (pintype "passive"))
      (node (ref "Q94") (pin "S") (pinfunction "S_S") (pintype "passive"))
      (node (ref "TP4") (pin "P$1") (pinfunction "P$1_P$1") (pintype "bidirectional"))
      (node (ref "TP5") (pin "P$1") (pinfunction "P$1_P$1") (pintype "bidirectional"))
      (node (ref "TP6") (pin "P$1") (pinfunction "P$1_P$1") (pintype "bidirectional"))
      (node (ref "TP7") (pin "P$1") (pinfunction "P$1_P$1") (pintype "bidirectional"))
    )
    (net (code "28") (name "IN_A0") (class "Default")
      (node (ref "J1") (pin "2") (pinfunction "2_2") (pintype "bidirectional"))
      (node (ref "J4") (pin "2") (pinfunction "2_2") (pintype "bidirectional"))
      (node (ref "Q193") (pin "G") (pinfunction "G_G") (pintype "passive"))
      (node (ref "Q25") (pin "G") (pinfunction "G_G") (pintype "passive"))
      (node (ref "Q46") (pin "G") (pinfunction "G_G") (pintype "passive"))
      (node (ref "Q58") (pin "G") (pinfunction "G_G") (pintype "passive"))
    )
    (net (code "29") (name "IN_A0_N") (class "Default")
      (node (ref "Q193") (pin "D") (pinfunction "D_D") (pintype "passive"))
      (node (ref "Q23") (pin "G") (pinfunction "G_G") (pintype "passive"))
      (node (ref "R241") (pin "1") (pinfunction "1_1") (pintype "passive"))
      (node (ref "R269") (pin "1") (pinfunction "1_1") (pintype "passive"))
      (node (ref "R30") (pin "1") (pinfunction "1_1") (pintype "passive"))
      (node (ref "R55") (pin "1") (pinfunction "1_1") (pintype "passive"))
      (node (ref "R75") (pin "1") (pinfunction "1_1") (pintype "passive"))
    )
    (net (code "30") (name "IN_A1") (class "Default")
      (node (ref "J1") (pin "3") (pinfunction "3_3") (pintype "bidirectional"))
      (node (ref "J4") (pin "3") (pinfunction "3_3") (pintype "bidirectional"))
      (node (ref "Q194") (pin "G") (pinfunction "G_G") (pintype "passive"))
      (node (ref "Q35") (pin "G") (pinfunction "G_G") (pintype "passive"))
      (node (ref "Q52") (pin "G") (pinfunction "G_G") (pintype "passive"))
      (node (ref "Q55") (pin "G") (pinfunction "G_G") (pintype "passive"))
    )
    (net (code "31") (name "IN_A1_N") (class "Default")
      (node (ref "Q194") (pin "D") (pinfunction "D_D") (pintype "passive"))
      (node (ref "Q33") (pin "G") (pinfunction "G_G") (pintype "passive"))
      (node (ref "R242") (pin "1") (pinfunction "1_1") (pintype "passive"))
      (node (ref "R270") (pin "1") (pinfunction "1_1") (pintype "passive"))
      (node (ref "R40") (pin "1") (pinfunction "1_1") (pintype "passive"))
      (node (ref "R65") (pin "1") (pinfunction "1_1") (pintype "passive"))
      (node (ref "R70") (pin "1") (pinfunction "1_1") (pintype "passive"))
    )
    (net (code "32") (name "IN_A2") (class "Default")
      (node (ref "J1") (pin "4") (pinfunction "4_4") (pintype "bidirectional"))
      (node (ref "J4") (pin "4") (pinfunction "4_4") (pintype "bidirectional"))
      (node (ref "Q143") (pin "G") (pinfunction "G_G") (pintype "passive"))
      (node (ref "Q146") (pin "G") (pinfunction "G_G") (pintype "passive"))
      (node (ref "Q195") (pin "G") (pinfunction "G_G") (pintype "passive"))
      (node (ref "Q82") (pin "G") (pinfunction "G_G") (pintype "passive"))
    )
    (net (code "33") (name "IN_A2_N") (class "Default")
      (node (ref "Q195") (pin "D") (pinfunction "D_D") (pintype "passive"))
      (node (ref "Q80") (pin "G") (pinfunction "G_G") (pintype "passive"))
      (node (ref "R160") (pin "1") (pinfunction "1_1") (pintype "passive"))
      (node (ref "R165") (pin "1") (pinfunction "1_1") (pintype "passive"))
      (node (ref "R243") (pin "1") (pinfunction "1_1") (pintype "passive"))
      (node (ref "R263") (pin "1") (pinfunction "1_1") (pintype "passive"))
      (node (ref "R95") (pin "1") (pinfunction "1_1") (pintype "passive"))
    )
    (net (code "34") (name "IN_A3") (class "Default")
      (node (ref "J1") (pin "5") (pinfunction "5_5") (pintype "bidirectional"))
      (node (ref "J4") (pin "5") (pinfunction "5_5") (pintype "bidirectional"))
      (node (ref "Q152") (pin "G") (pinfunction "G_G") (pintype "passive"))
      (node (ref "Q155") (pin "G") (pinfunction "G_G") (pintype "passive"))
      (node (ref "Q196") (pin "G") (pinfunction "G_G") (pintype "passive"))
      (node (ref "Q92") (pin "G") (pinfunction "G_G") (pintype "passive"))
    )
    (net (code "35") (name "IN_A3_N") (class "Default")
      (node (ref "Q196") (pin "D") (pinfunction "D_D") (pintype "passive"))
      (node (ref "Q90") (pin "G") (pinfunction "G_G") (pintype "passive"))
      (node (ref "R105") (pin "1") (pinfunction "1_1") (pintype "passive"))
      (node (ref "R175") (pin "1") (pinfunction "1_1") (pintype "passive"))
      (node (ref "R180") (pin "1") (pinfunction "1_1") (pintype "passive"))
      (node (ref "R244") (pin "1") (pinfunction "1_1") (pintype "passive"))
      (node (ref "R272") (pin "1") (pinfunction "1_1") (pintype "passive"))
    )
    (net (code "36") (name "IN_A4") (class "Default")
      (node (ref "J1") (pin "6") (pinfunction "6_6") (pintype "bidirectional"))
      (node (ref "J4") (pin "6") (pinfunction "6_6") (pintype "bidirectional"))
      (node (ref "Q102") (pin "G") (pinfunction "G_G") (pintype "passive"))
      (node (ref "Q161") (pin "G") (pinfunction "G_G") (pintype "passive"))
      (node (ref "Q164") (pin "G") (pinfunction "G_G") (pintype "passive"))
      (node (ref "Q197") (pin "G") (pinfunction "G_G") (pintype "passive"))
    )
    (net (code "37") (name "IN_A4_N") (class "Default")
      (node (ref "Q100") (pin "G") (pinfunction "G_G") (pintype "passive"))
      (node (ref "Q197") (pin "D") (pinfunction "D_D") (pintype "passive"))
      (node (ref "R115") (pin "1") (pinfunction "1_1") (pintype "passive"))
      (node (ref "R190") (pin "1") (pinfunction "1_1") (pintype "passive"))
      (node (ref "R195") (pin "1") (pinfunction "1_1") (pintype "passive"))
      (node (ref "R245") (pin "1") (pinfunction "1_1") (pintype "passive"))
      (node (ref "R271") (pin "1") (pinfunction "1_1") (pintype "passive"))
    )
    (net (code "38") (name "IN_A5") (class "Default")
      (node (ref "J1") (pin "7") (pinfunction "7_7") (pintype "bidirectional"))
      (node (ref "J4") (pin "7") (pinfunction "7_7") (pintype "bidirectional"))
      (node (ref "Q112") (pin "G") (pinfunction "G_G") (pintype "passive"))
      (node (ref "Q170") (pin "G") (pinfunction "G_G") (pintype "passive"))
      (node (ref "Q173") (pin "G") (pinfunction "G_G") (pintype "passive"))
      (node (ref "Q198") (pin "G") (pinfunction "G_G") (pintype "passive"))
    )
    (net (code "39") (name "IN_A5_N") (class "Default")
      (node (ref "Q110") (pin "G") (pinfunction "G_G") (pintype "passive"))
      (node (ref "Q198") (pin "D") (pinfunction "D_D") (pintype "passive"))
      (node (ref "R125") (pin "1") (pinfunction "1_1") (pintype "passive"))
      (node (ref "R205") (pin "1") (pinfunction "1_1") (pintype "passive"))
      (node (ref "R210") (pin "1") (pinfunction "1_1") (pintype "passive"))
      (node (ref "R246") (pin "1") (pinfunction "1_1") (pintype "passive"))
      (node (ref "R273") (pin "1") (pinfunction "1_1") (pintype "passive"))
    )
    (net (code "40") (name "IN_A6") (class "Default")
      (node (ref "J1") (pin "8") (pinfunction "8_8") (pintype "bidirectional"))
      (node (ref "J4") (pin "8") (pinfunction "8_8") (pintype "bidirectional"))
      (node (ref "Q122") (pin "G") (pinfunction "G_G") (pintype "passive"))
      (node (ref "Q179") (pin "G") (pinfunction "G_G") (pintype "passive"))
      (node (ref "Q182") (pin "G") (pinfunction "G_G") (pintype "passive"))
      (node (ref "Q199") (pin "G") (pinfunction "G_G") (pintype "passive"))
    )
    (net (code "41") (name "IN_A6_N") (class "Default")
      (node (ref "Q120") (pin "G") (pinfunction "G_G") (pintype "passive"))
      (node (ref "Q199") (pin "D") (pinfunction "D_D") (pintype "passive"))
      (node (ref "R135") (pin "1") (pinfunction "1_1") (pintype "passive"))
      (node (ref "R220") (pin "1") (pinfunction "1_1") (pintype "passive"))
      (node (ref "R225") (pin "1") (pinfunction "1_1") (pintype "passive"))
      (node (ref "R247") (pin "1") (pinfunction "1_1") (pintype "passive"))
      (node (ref "R274") (pin "1") (pinfunction "1_1") (pintype "passive"))
    )
    (net (code "42") (name "IN_A7") (class "Default")
      (node (ref "J1") (pin "9") (pinfunction "9_9") (pintype "bidirectional"))
      (node (ref "J4") (pin "9") (pinfunction "9_9") (pintype "bidirectional"))
      (node (ref "Q132") (pin "G") (pinfunction "G_G") (pintype "passive"))
      (node (ref "Q188") (pin "G") (pinfunction "G_G") (pintype "passive"))
      (node (ref "Q191") (pin "G") (pinfunction "G_G") (pintype "passive"))
      (node (ref "Q200") (pin "G") (pinfunction "G_G") (pintype "passive"))
    )
    (net (code "43") (name "IN_A7_N") (class "Default")
      (node (ref "Q130") (pin "G") (pinfunction "G_G") (pintype "passive"))
      (node (ref "Q200") (pin "D") (pinfunction "D_D") (pintype "passive"))
      (node (ref "R145") (pin "1") (pinfunction "1_1") (pintype "passive"))
      (node (ref "R235") (pin "1") (pinfunction "1_1") (pintype "passive"))
      (node (ref "R240") (pin "1") (pinfunction "1_1") (pintype "passive"))
      (node (ref "R248") (pin "1") (pinfunction "1_1") (pintype "passive"))
      (node (ref "R275") (pin "1") (pinfunction "1_1") (pintype "passive"))
    )
    (net (code "44") (name "IN_B0") (class "Default")
      (node (ref "J2") (pin "2") (pinfunction "2_2") (pintype "bidirectional"))
      (node (ref "J4") (pin "11") (pinfunction "11_11") (pintype "bidirectional"))
      (node (ref "Q201") (pin "G") (pinfunction "G_G") (pintype "passive"))
      (node (ref "Q22") (pin "G") (pinfunction "G_G") (pintype "passive"))
      (node (ref "Q45") (pin "G") (pinfunction "G_G") (pintype "passive"))
      (node (ref "Q57") (pin "G") (pinfunction "G_G") (pintype "passive"))
    )
    (net (code "45") (name "IN_B0_N") (class "Default")
      (node (ref "Q201") (pin "D") (pinfunction "D_D") (pintype "passive"))
      (node (ref "Q24") (pin "G") (pinfunction "G_G") (pintype "passive"))
      (node (ref "R249") (pin "1") (pinfunction "1_1") (pintype "passive"))
      (node (ref "R262") (pin "1") (pinfunction "1_1") (pintype "passive"))
      (node (ref "R29") (pin "1") (pinfunction "1_1") (pintype "passive"))
      (node (ref "R54") (pin "1") (pinfunction "1_1") (pintype "passive"))
      (node (ref "R74") (pin "1") (pinfunction "1_1") (pintype "passive"))
    )
    (net (code "46") (name "IN_B1") (class "Default")
      (node (ref "J2") (pin "3") (pinfunction "3_3") (pintype "bidirectional"))
      (node (ref "J4") (pin "12") (pinfunction "12_12") (pintype "bidirectional"))
      (node (ref "Q202") (pin "G") (pinfunction "G_G") (pintype "passive"))
      (node (ref "Q32") (pin "G") (pinfunction "G_G") (pintype "passive"))
      (node (ref "Q51") (pin "G") (pinfunction "G_G") (pintype "passive"))
      (node (ref "Q54") (pin "G") (pinfunction "G_G") (pintype "passive"))
    )
    (net (code "47") (name "IN_B1_N") (class "Default")
      (node (ref "Q202") (pin "D") (pinfunction "D_D") (pintype "passive"))
      (node (ref "Q34") (pin "G") (pinfunction "G_G") (pintype "passive"))
      (node (ref "R250") (pin "1") (pinfunction "1_1") (pintype "passive"))
      (node (ref "R261") (pin "1") (pinfunction "1_1") (pintype "passive"))
      (node (ref "R39") (pin "1") (pinfunction "1_1") (pintype "passive"))
      (node (ref "R64") (pin "1") (pinfunction "1_1") (pintype "passive"))
      (node (ref "R69") (pin "1") (pinfunction "1_1") (pintype "passive"))
    )
    (net (code "48") (name "IN_B2") (class "Default")
      (node (ref "J2") (pin "4") (pinfunction "4_4") (pintype "bidirectional"))
      (node (ref "J4") (pin "13") (pinfunction "13_13") (pintype "bidirectional"))
      (node (ref "Q142") (pin "G") (pinfunction "G_G") (pintype "passive"))
      (node (ref "Q145") (pin "G") (pinfunction "G_G") (pintype "passive"))
      (node (ref "Q203") (pin "G") (pinfunction "G_G") (pintype "passive"))
      (node (ref "Q79") (pin "G") (pinfunction "G_G") (pintype "passive"))
    )
    (net (code "49") (name "IN_B2_N") (class "Default")
      (node (ref "Q203") (pin "D") (pinfunction "D_D") (pintype "passive"))
      (node (ref "Q81") (pin "G") (pinfunction "G_G") (pintype "passive"))
      (node (ref "R159") (pin "1") (pinfunction "1_1") (pintype "passive"))
      (node (ref "R164") (pin "1") (pinfunction "1_1") (pintype "passive"))
      (node (ref "R251") (pin "1") (pinfunction "1_1") (pintype "passive"))
      (node (ref "R260") (pin "1") (pinfunction "1_1") (pintype "passive"))
      (node (ref "R94") (pin "1") (pinfunction "1_1") (pintype "passive"))
    )
    (net (code "50") (name "IN_B3") (class "Default")
      (node (ref "J2") (pin "5") (pinfunction "5_5") (pintype "bidirectional"))
      (node (ref "J4") (pin "14") (pinfunction "14_14") (pintype "bidirectional"))
      (node (ref "Q151") (pin "G") (pinfunction "G_G") (pintype "passive"))
      (node (ref "Q154") (pin "G") (pinfunction "G_G") (pintype "passive"))
      (node (ref "Q204") (pin "G") (pinfunction "G_G") (pintype "passive"))
      (node (ref "Q89") (pin "G") (pinfunction "G_G") (pintype "passive"))
    )
    (net (code "51") (name "IN_B3_N") (class "Default")
      (node (ref "Q204") (pin "D") (pinfunction "D_D") (pintype "passive"))
      (node (ref "Q91") (pin "G") (pinfunction "G_G") (pintype "passive"))
      (node (ref "R104") (pin "1") (pinfunction "1_1") (pintype "passive"))
      (node (ref "R174") (pin "1") (pinfunction "1_1") (pintype "passive"))
      (node (ref "R179") (pin "1") (pinfunction "1_1") (pintype "passive"))
      (node (ref "R252") (pin "1") (pinfunction "1_1") (pintype "passive"))
      (node (ref "R259") (pin "1") (pinfunction "1_1") (pintype "passive"))
    )
    (net (code "52") (name "IN_B4") (class "Default")
      (node (ref "J2") (pin "6") (pinfunction "6_6") (pintype "bidirectional"))
      (node (ref "J4") (pin "15") (pinfunction "15_15") (pintype "bidirectional"))
      (node (ref "Q160") (pin "G") (pinfunction "G_G") (pintype "passive"))
      (node (ref "Q163") (pin "G") (pinfunction "G_G") (pintype "passive"))
      (node (ref "Q205") (pin "G") (pinfunction "G_G") (pintype "passive"))
      (node (ref "Q99") (pin "G") (pinfunction "G_G") (pintype "passive"))
    )
    (net (code "53") (name "IN_B4_N") (class "Default")
      (node (ref "Q101") (pin "G") (pinfunction "G_G") (pintype "passive"))
      (node (ref "Q205") (pin "D") (pinfunction "D_D") (pintype "passive"))
      (node (ref "R114") (pin "1") (pinfunction "1_1") (pintype "passive"))
      (node (ref "R189") (pin "1") (pinfunction "1_1") (pintype "passive"))
      (node (ref "R194") (pin "1") (pinfunction "1_1") (pintype "passive"))
      (node (ref "R253") (pin "1") (pinfunction "1_1") (pintype "passive"))
      (node (ref "R264") (pin "1") (pinfunction "1_1") (pintype "passive"))
    )
    (net (code "54") (name "IN_B5") (class "Default")
      (node (ref "J2") (pin "7") (pinfunction "7_7") (pintype "bidirectional"))
      (node (ref "J4") (pin "16") (pinfunction "16_16") (pintype "bidirectional"))
      (node (ref "Q109") (pin "G") (pinfunction "G_G") (pintype "passive"))
      (node (ref "Q169") (pin "G") (pinfunction "G_G") (pintype "passive"))
      (node (ref "Q172") (pin "G") (pinfunction "G_G") (pintype "passive"))
      (node (ref "Q206") (pin "G") (pinfunction "G_G") (pintype "passive"))
    )
    (net (code "55") (name "IN_B5_N") (class "Default")
      (node (ref "Q111") (pin "G") (pinfunction "G_G") (pintype "passive"))
      (node (ref "Q206") (pin "D") (pinfunction "D_D") (pintype "passive"))
      (node (ref "R124") (pin "1") (pinfunction "1_1") (pintype "passive"))
      (node (ref "R204") (pin "1") (pinfunction "1_1") (pintype "passive"))
      (node (ref "R209") (pin "1") (pinfunction "1_1") (pintype "passive"))
      (node (ref "R254") (pin "1") (pinfunction "1_1") (pintype "passive"))
      (node (ref "R265") (pin "1") (pinfunction "1_1") (pintype "passive"))
    )
    (net (code "56") (name "IN_B6") (class "Default")
      (node (ref "J2") (pin "8") (pinfunction "8_8") (pintype "bidirectional"))
      (node (ref "J4") (pin "17") (pinfunction "17_17") (pintype "bidirectional"))
      (node (ref "Q119") (pin "G") (pinfunction "G_G") (pintype "passive"))
      (node (ref "Q178") (pin "G") (pinfunction "G_G") (pintype "passive"))
      (node (ref "Q181") (pin "G") (pinfunction "G_G") (pintype "passive"))
      (node (ref "Q207") (pin "G") (pinfunction "G_G") (pintype "passive"))
    )
    (net (code "57") (name "IN_B6_N") (class "Default")
      (node (ref "Q121") (pin "G") (pinfunction "G_G") (pintype "passive"))
      (node (ref "Q207") (pin "D") (pinfunction "D_D") (pintype "passive"))
      (node (ref "R134") (pin "1") (pinfunction "1_1") (pintype "passive"))
      (node (ref "R219") (pin "1") (pinfunction "1_1") (pintype "passive"))
      (node (ref "R224") (pin "1") (pinfunction "1_1") (pintype "passive"))
      (node (ref "R255") (pin "1") (pinfunction "1_1") (pintype "passive"))
      (node (ref "R266") (pin "1") (pinfunction "1_1") (pintype "passive"))
    )
    (net (code "58") (name "IN_B7") (class "Default")
      (node (ref "J2") (pin "9") (pinfunction "9_9") (pintype "bidirectional"))
      (node (ref "J4") (pin "18") (pinfunction "18_18") (pintype "bidirectional"))
      (node (ref "Q129") (pin "G") (pinfunction "G_G") (pintype "passive"))
      (node (ref "Q187") (pin "G") (pinfunction "G_G") (pintype "passive"))
      (node (ref "Q190") (pin "G") (pinfunction "G_G") (pintype "passive"))
      (node (ref "Q208") (pin "G") (pinfunction "G_G") (pintype "passive"))
    )
    (net (code "59") (name "IN_B7_N") (class "Default")
      (node (ref "Q131") (pin "G") (pinfunction "G_G") (pintype "passive"))
      (node (ref "Q208") (pin "D") (pinfunction "D_D") (pintype "passive"))
      (node (ref "R144") (pin "1") (pinfunction "1_1") (pintype "passive"))
      (node (ref "R234") (pin "1") (pinfunction "1_1") (pintype "passive"))
      (node (ref "R239") (pin "1") (pinfunction "1_1") (pintype "passive"))
      (node (ref "R256") (pin "1") (pinfunction "1_1") (pintype "passive"))
      (node (ref "R267") (pin "1") (pinfunction "1_1") (pintype "passive"))
    )
    (net (code "60") (name "Net-(D1-C)") (class "Default")
      (node (ref "D1") (pin "K") (pinfunction "C_K") (pintype "passive"))
      (node (ref "R3") (pin "2") (pinfunction "2_2") (pintype "passive"))
    )
    (net (code "61") (name "Net-(D2-C)") (class "Default")
      (node (ref "D2") (pin "K") (pinfunction "C_K") (pintype "passive"))
      (node (ref "R4") (pin "2") (pinfunction "2_2") (pintype "passive"))
    )
    (net (code "62") (name "Net-(D3-C)") (class "Default")
      (node (ref "D3") (pin "K") (pinfunction "C_K") (pintype "passive"))
      (node (ref "R6") (pin "2") (pinfunction "2_2") (pintype "passive"))
    )
    (net (code "63") (name "Net-(D4-C)") (class "Default")
      (node (ref "D4") (pin "K") (pinfunction "C_K") (pintype "passive"))
      (node (ref "R16") (pin "2") (pinfunction "2_2") (pintype "passive"))
    )
    (net (code "64") (name "Net-(D5-C)") (class "Default")
      (node (ref "D5") (pin "K") (pinfunction "C_K") (pintype "passive"))
      (node (ref "R17") (pin "2") (pinfunction "2_2") (pintype "passive"))
    )
    (net (code "65") (name "Net-(D6-C)") (class "Default")
      (node (ref "D6") (pin "K") (pinfunction "C_K") (pintype "passive"))
      (node (ref "R18") (pin "2") (pinfunction "2_2") (pintype "passive"))
    )
    (net (code "66") (name "Net-(D7-C)") (class "Default")
      (node (ref "D7") (pin "K") (pinfunction "C_K") (pintype "passive"))
      (node (ref "R19") (pin "2") (pinfunction "2_2") (pintype "passive"))
    )
    (net (code "67") (name "Net-(D8-C)") (class "Default")
      (node (ref "D8") (pin "K") (pinfunction "C_K") (pintype "passive"))
      (node (ref "R20") (pin "2") (pinfunction "2_2") (pintype "passive"))
    )
    (net (code "68") (name "Net-(D9-C)") (class "Default")
      (node (ref "D9") (pin "K") (pinfunction "C_K") (pintype "passive"))
      (node (ref "R21") (pin "2") (pinfunction "2_2") (pintype "passive"))
    )
    (net (code "69") (name "Net-(D10-C)") (class "Default")
      (node (ref "D10") (pin "K") (pinfunction "C_K") (pintype "passive"))
      (node (ref "R22") (pin "2") (pinfunction "2_2") (pintype "passive"))
    )
    (net (code "70") (name "Net-(D11-C)") (class "Default")
      (node (ref "D11") (pin "K") (pinfunction "C_K") (pintype "passive"))
      (node (ref "R23") (pin "2") (pinfunction "2_2") (pintype "passive"))
    )
    (net (code "71") (name "Net-(D12-C)") (class "Default")
      (node (ref "D12") (pin "K") (pinfunction "C_K") (pintype "passive"))
      (node (ref "R43") (pin "2") (pinfunction "2_2") (pintype "passive"))
    )
    (net (code "72") (name "Net-(D13-C)") (class "Default")
      (node (ref "D13") (pin "K") (pinfunction "C_K") (pintype "passive"))
      (node (ref "R44") (pin "2") (pinfunction "2_2") (pintype "passive"))
    )
    (net (code "73") (name "Net-(D14-C)") (class "Default")
      (node (ref "D14") (pin "K") (pinfunction "C_K") (pintype "passive"))
      (node (ref "R45") (pin "2") (pinfunction "2_2") (pintype "passive"))
    )
    (net (code "74") (name "Net-(D15-C)") (class "Default")
      (node (ref "D15") (pin "K") (pinfunction "C_K") (pintype "passive"))
      (node (ref "R46") (pin "2") (pinfunction "2_2") (pintype "passive"))
    )
    (net (code "75") (name "Net-(D16-C)") (class "Default")
      (node (ref "D16") (pin "K") (pinfunction "C_K") (pintype "passive"))
      (node (ref "R27") (pin "2") (pinfunction "2_2") (pintype "passive"))
    )
    (net (code "76") (name "Net-(D17-C)") (class "Default")
      (node (ref "D17") (pin "K") (pinfunction "C_K") (pintype "passive"))
      (node (ref "R29") (pin "2") (pinfunction "2_2") (pintype "passive"))
    )
    (net (code "77") (name "Net-(D18-C)") (class "Default")
      (node (ref "D18") (pin "K") (pinfunction "C_K") (pintype "passive"))
      (node (ref "R30") (pin "2") (pinfunction "2_2") (pintype "passive"))
    )
    (net (code "78") (name "Net-(D19-C)") (class "Default")
      (node (ref "D19") (pin "K") (pinfunction "C_K") (pintype "passive"))
      (node (ref "R47") (pin "2") (pinfunction "2_2") (pintype "passive"))
    )
    (net (code "79") (name "Net-(D20-C)") (class "Default")
      (node (ref "D20") (pin "K") (pinfunction "C_K") (pintype "passive"))
      (node (ref "R48") (pin "2") (pinfunction "2_2") (pintype "passive"))
    )
    (net (code "80") (name "Net-(D21-C)") (class "Default")
      (node (ref "D21") (pin "K") (pinfunction "C_K") (pintype "passive"))
      (node (ref "R49") (pin "2") (pinfunction "2_2") (pintype "passive"))
    )
    (net (code "81") (name "Net-(D22-C)") (class "Default")
      (node (ref "D22") (pin "K") (pinfunction "C_K") (pintype "passive"))
      (node (ref "R37") (pin "2") (pinfunction "2_2") (pintype "passive"))
    )
    (net (code "82") (name "Net-(D23-C)") (class "Default")
      (node (ref "D23") (pin "K") (pinfunction "C_K") (pintype "passive"))
      (node (ref "R39") (pin "2") (pinfunction "2_2") (pintype "passive"))
    )
    (net (code "83") (name "Net-(D24-C)") (class "Default")
      (node (ref "D24") (pin "K") (pinfunction "C_K") (pintype "passive"))
      (node (ref "R40") (pin "2") (pinfunction "2_2") (pintype "passive"))
    )
    (net (code "84") (name "Net-(D25-C)") (class "Default")
      (node (ref "D25") (pin "K") (pinfunction "C_K") (pintype "passive"))
      (node (ref "R50") (pin "2") (pinfunction "2_2") (pintype "passive"))
    )
    (net (code "85") (name "Net-(D26-C)") (class "Default")
      (node (ref "D26") (pin "K") (pinfunction "C_K") (pintype "passive"))
      (node (ref "R80") (pin "2") (pinfunction "2_2") (pintype "passive"))
    )
    (net (code "86") (name "Net-(D27-C)") (class "Default")
      (node (ref "D27") (pin "K") (pinfunction "C_K") (pintype "passive"))
      (node (ref "R81") (pin "2") (pinfunction "2_2") (pintype "passive"))
    )
    (net (code "87") (name "Net-(D28-C)") (class "Default")
      (node (ref "D28") (pin "K") (pinfunction "C_K") (pintype "passive"))
      (node (ref "R82") (pin "2") (pinfunction "2_2") (pintype "passive"))
    )
    (net (code "88") (name "Net-(D29-C)") (class "Default")
      (node (ref "D29") (pin "K") (pinfunction "C_K") (pintype "passive"))
      (node (ref "R83") (pin "2") (pinfunction "2_2") (pintype "passive"))
    )
    (net (code "89") (name "Net-(D30-C)") (class "Default")
      (node (ref "D30") (pin "K") (pinfunction "C_K") (pintype "passive"))
      (node (ref "R84") (pin "2") (pinfunction "2_2") (pintype "passive"))
    )
    (net (code "90") (name "Net-(D31-C)") (class "Default")
      (node (ref "D31") (pin "K") (pinfunction "C_K") (pintype "passive"))
      (node (ref "R52") (pin "2") (pinfunction "2_2") (pintype "passive"))
    )
    (net (code "91") (name "Net-(D32-C)") (class "Default")
      (node (ref "D32") (pin "K") (pinfunction "C_K") (pintype "passive"))
      (node (ref "R54") (pin "2") (pinfunction "2_2") (pintype "passive"))
    )
    (net (code "92") (name "Net-(D33-C)") (class "Default")
      (node (ref "D33") (pin "K") (pinfunction "C_K") (pintype "passive"))
      (node (ref "R55") (pin "2") (pinfunction "2_2") (pintype "passive"))
    )
    (net (code "93") (name "Net-(D34-C)") (class "Default")
      (node (ref "D34") (pin "K") (pinfunction "C_K") (pintype "passive"))
      (node (ref "R85") (pin "2") (pinfunction "2_2") (pintype "passive"))
    )
    (net (code "94") (name "Net-(D35-C)") (class "Default")
      (node (ref "D35") (pin "K") (pinfunction "C_K") (pintype "passive"))
      (node (ref "R86") (pin "2") (pinfunction "2_2") (pintype "passive"))
    )
    (net (code "95") (name "Net-(D36-C)") (class "Default")
      (node (ref "D36") (pin "K") (pinfunction "C_K") (pintype "passive"))
      (node (ref "R87") (pin "2") (pinfunction "2_2") (pintype "passive"))
    )
    (net (code "96") (name "Net-(D37-C)") (class "Default")
      (node (ref "D37") (pin "K") (pinfunction "C_K") (pintype "passive"))
      (node (ref "R62") (pin "2") (pinfunction "2_2") (pintype "passive"))
    )
    (net (code "97") (name "Net-(D38-C)") (class "Default")
      (node (ref "D38") (pin "K") (pinfunction "C_K") (pintype "passive"))
      (node (ref "R64") (pin "2") (pinfunction "2_2") (pintype "passive"))
    )
    (net (code "98") (name "Net-(D39-C)") (class "Default")
      (node (ref "D39") (pin "K") (pinfunction "C_K") (pintype "passive"))
      (node (ref "R65") (pin "2") (pinfunction "2_2") (pintype "passive"))
    )
    (net (code "99") (name "Net-(D40-C)") (class "Default")
      (node (ref "D40") (pin "K") (pinfunction "C_K") (pintype "passive"))
      (node (ref "R67") (pin "2") (pinfunction "2_2") (pintype "passive"))
    )
    (net (code "100") (name "Net-(D41-C)") (class "Default")
      (node (ref "D41") (pin "K") (pinfunction "C_K") (pintype "passive"))
      (node (ref "R69") (pin "2") (pinfunction "2_2") (pintype "passive"))
    )
    (net (code "101") (name "Net-(D42-C)") (class "Default")
      (node (ref "D42") (pin "K") (pinfunction "C_K") (pintype "passive"))
      (node (ref "R70") (pin "2") (pinfunction "2_2") (pintype "passive"))
    )
    (net (code "102") (name "Net-(D43-C)") (class "Default")
      (node (ref "D43") (pin "K") (pinfunction "C_K") (pintype "passive"))
      (node (ref "R72") (pin "2") (pinfunction "2_2") (pintype "passive"))
    )
    (net (code "103") (name "Net-(D44-C)") (class "Default")
      (node (ref "D44") (pin "K") (pinfunction "C_K") (pintype "passive"))
      (node (ref "R74") (pin "2") (pinfunction "2_2") (pintype "passive"))
    )
    (net (code "104") (name "Net-(D45-C)") (class "Default")
      (node (ref "D45") (pin "K") (pinfunction "C_K") (pintype "passive"))
      (node (ref "R75") (pin "2") (pinfunction "2_2") (pintype "passive"))
    )
    (net (code "105") (name "Net-(D46-C)") (class "Default")
      (node (ref "D46") (pin "K") (pinfunction "C_K") (pintype "passive"))
      (node (ref "R88") (pin "2") (pinfunction "2_2") (pintype "passive"))
    )
    (net (code "106") (name "Net-(D47-C)") (class "Default")
      (node (ref "D47") (pin "K") (pinfunction "C_K") (pintype "passive"))
      (node (ref "R90") (pin "2") (pinfunction "2_2") (pintype "passive"))
    )
    (net (code "107") (name "Net-(D48-C)") (class "Default")
      (node (ref "D48") (pin "K") (pinfunction "C_K") (pintype "passive"))
      (node (ref "R97") (pin "2") (pinfunction "2_2") (pintype "passive"))
    )
    (net (code "108") (name "Net-(D49-C)") (class "Default")
      (node (ref "D49") (pin "K") (pinfunction "C_K") (pintype "passive"))
      (node (ref "R99") (pin "2") (pinfunction "2_2") (pintype "passive"))
    )
    (net (code "109") (name "Net-(D50-C)") (class "Default")
      (node (ref "D50") (pin "K") (pinfunction "C_K") (pintype "passive"))
      (node (ref "R106") (pin "2") (pinfunction "2_2") (pintype "passive"))
    )
    (net (code "110") (name "Net-(D51-C)") (class "Default")
      (node (ref "D51") (pin "K") (pinfunction "C_K") (pintype "passive"))
      (node (ref "R108") (pin "2") (pinfunction "2_2") (pintype "passive"))
    )
    (net (code "111") (name "Net-(D52-C)") (class "Default")
      (node (ref "D52") (pin "K") (pinfunction "C_K") (pintype "passive"))
      (node (ref "R110") (pin "2") (pinfunction "2_2") (pintype "passive"))
    )
    (net (code "112") (name "Net-(D53-C)") (class "Default")
      (node (ref "D53") (pin "K") (pinfunction "C_K") (pintype "passive"))
      (node (ref "R117") (pin "2") (pinfunction "2_2") (pintype "passive"))
    )
    (net (code "113") (name "Net-(D54-C)") (class "Default")
      (node (ref "D54") (pin "K") (pinfunction "C_K") (pintype "passive"))
      (node (ref "R31") (pin "2") (pinfunction "2_2") (pintype "passive"))
    )
    (net (code "114") (name "Net-(D55-C)") (class "Default")
      (node (ref "D55") (pin "K") (pinfunction "C_K") (pintype "passive"))
      (node (ref "R92") (pin "2") (pinfunction "2_2") (pintype "passive"))
    )
    (net (code "115") (name "Net-(D56-C)") (class "Default")
      (node (ref "D56") (pin "K") (pinfunction "C_K") (pintype "passive"))
      (node (ref "R94") (pin "2") (pinfunction "2_2") (pintype "passive"))
    )
    (net (code "116") (name "Net-(D57-C)") (class "Default")
      (node (ref "D57") (pin "K") (pinfunction "C_K") (pintype "passive"))
      (node (ref "R95") (pin "2") (pinfunction "2_2") (pintype "passive"))
    )
    (net (code "117") (name "Net-(D58-C)") (class "Default")
      (node (ref "D58") (pin "K") (pinfunction "C_K") (pintype "passive"))
      (node (ref "R32") (pin "2") (pinfunction "2_2") (pintype "passive"))
    )
    (net (code "118") (name "Net-(D59-C)") (class "Default")
      (node (ref "D59") (pin "K") (pinfunction "C_K") (pintype "passive"))
      (node (ref "R33") (pin "2") (pinfunction "2_2") (pintype "passive"))
    )
    (net (code "119") (name "Net-(D61-C)") (class "Default")
      (node (ref "D61") (pin "K") (pinfunction "C_K") (pintype "passive"))
      (node (ref "R102") (pin "2") (pinfunction "2_2") (pintype "passive"))
    )
    (net (code "120") (name "Net-(D62-C)") (class "Default")
      (node (ref "D62") (pin "K") (pinfunction "C_K") (pintype "passive"))
      (node (ref "R104") (pin "2") (pinfunction "2_2") (pintype "passive"))
    )
    (net (code "121") (name "Net-(D63-C)") (class "Default")
      (node (ref "D63") (pin "K") (pinfunction "C_K") (pintype "passive"))
      (node (ref "R105") (pin "2") (pinfunction "2_2") (pintype "passive"))
    )
    (net (code "122") (name "Net-(D67-C)") (class "Default")
      (node (ref "D67") (pin "K") (pinfunction "C_K") (pintype "passive"))
      (node (ref "R112") (pin "2") (pinfunction "2_2") (pintype "passive"))
    )
    (net (code "123") (name "Net-(D68-C)") (class "Default")
      (node (ref "D68") (pin "K") (pinfunction "C_K") (pintype "passive"))
      (node (ref "R114") (pin "2") (pinfunction "2_2") (pintype "passive"))
    )
    (net (code "124") (name "Net-(D69-C)") (class "Default")
      (node (ref "D69") (pin "K") (pinfunction "C_K") (pintype "passive"))
      (node (ref "R115") (pin "2") (pinfunction "2_2") (pintype "passive"))
    )
    (net (code "125") (name "Net-(D73-C)") (class "Default")
      (node (ref "D73") (pin "K") (pinfunction "C_K") (pintype "passive"))
      (node (ref "R122") (pin "2") (pinfunction "2_2") (pintype "passive"))
    )
    (net (code "126") (name "Net-(D74-C)") (class "Default")
      (node (ref "D74") (pin "K") (pinfunction "C_K") (pintype "passive"))
      (node (ref "R124") (pin "2") (pinfunction "2_2") (pintype "passive"))
    )
    (net (code "127") (name "Net-(D75-C)") (class "Default")
      (node (ref "D75") (pin "K") (pinfunction "C_K") (pintype "passive"))
      (node (ref "R125") (pin "2") (pinfunction "2_2") (pintype "passive"))
    )
    (net (code "128") (name "Net-(D79-C)") (class "Default")
      (node (ref "D79") (pin "K") (pinfunction "C_K") (pintype "passive"))
      (node (ref "R132") (pin "2") (pinfunction "2_2") (pintype "passive"))
    )
    (net (code "129") (name "Net-(D80-C)") (class "Default")
      (node (ref "D80") (pin "K") (pinfunction "C_K") (pintype "passive"))
      (node (ref "R134") (pin "2") (pinfunction "2_2") (pintype "passive"))
    )
    (net (code "130") (name "Net-(D81-C)") (class "Default")
      (node (ref "D81") (pin "K") (pinfunction "C_K") (pintype "passive"))
      (node (ref "R135") (pin "2") (pinfunction "2_2") (pintype "passive"))
    )
    (net (code "131") (name "Net-(D85-C)") (class "Default")
      (node (ref "D85") (pin "K") (pinfunction "C_K") (pintype "passive"))
      (node (ref "R142") (pin "2") (pinfunction "2_2") (pintype "passive"))
    )
    (net (code "132") (name "Net-(D86-C)") (class "Default")
      (node (ref "D86") (pin "K") (pinfunction "C_K") (pintype "passive"))
      (node (ref "R144") (pin "2") (pinfunction "2_2") (pintype "passive"))
    )
    (net (code "133") (name "Net-(D87-C)") (class "Default")
      (node (ref "D87") (pin "K") (pinfunction "C_K") (pintype "passive"))
      (node (ref "R145") (pin "2") (pinfunction "2_2") (pintype "passive"))
    )
    (net (code "134") (name "Net-(D94-C)") (class "Default")
      (node (ref "D94") (pin "K") (pinfunction "C_K") (pintype "passive"))
      (node (ref "R157") (pin "2") (pinfunction "2_2") (pintype "passive"))
    )
    (net (code "135") (name "Net-(D95-C)") (class "Default")
      (node (ref "D95") (pin "K") (pinfunction "C_K") (pintype "passive"))
      (node (ref "R159") (pin "2") (pinfunction "2_2") (pintype "passive"))
    )
    (net (code "136") (name "Net-(D96-C)") (class "Default")
      (node (ref "D96") (pin "K") (pinfunction "C_K") (pintype "passive"))
      (node (ref "R160") (pin "2") (pinfunction "2_2") (pintype "passive"))
    )
    (net (code "137") (name "Net-(D97-C)") (class "Default")
      (node (ref "D97") (pin "K") (pinfunction "C_K") (pintype "passive"))
      (node (ref "R162") (pin "2") (pinfunction "2_2") (pintype "passive"))
    )
    (net (code "138") (name "Net-(D98-C)") (class "Default")
      (node (ref "D98") (pin "K") (pinfunction "C_K") (pintype "passive"))
      (node (ref "R164") (pin "2") (pinfunction "2_2") (pintype "passive"))
    )
    (net (code "139") (name "Net-(D99-C)") (class "Default")
      (node (ref "D99") (pin "K") (pinfunction "C_K") (pintype "passive"))
      (node (ref "R165") (pin "2") (pinfunction "2_2") (pintype "passive"))
    )
    (net (code "140") (name "Net-(D103-C)") (class "Default")
      (node (ref "D103") (pin "K") (pinfunction "C_K") (pintype "passive"))
      (node (ref "R172") (pin "2") (pinfunction "2_2") (pintype "passive"))
    )
    (net (code "141") (name "Net-(D104-C)") (class "Default")
      (node (ref "D104") (pin "K") (pinfunction "C_K") (pintype "passive"))
      (node (ref "R174") (pin "2") (pinfunction "2_2") (pintype "passive"))
    )
    (net (code "142") (name "Net-(D105-C)") (class "Default")
      (node (ref "D105") (pin "K") (pinfunction "C_K") (pintype "passive"))
      (node (ref "R175") (pin "2") (pinfunction "2_2") (pintype "passive"))
    )
    (net (code "143") (name "Net-(D106-C)") (class "Default")
      (node (ref "D106") (pin "K") (pinfunction "C_K") (pintype "passive"))
      (node (ref "R177") (pin "2") (pinfunction "2_2") (pintype "passive"))
    )
    (net (code "144") (name "Net-(D107-C)") (class "Default")
      (node (ref "D107") (pin "K") (pinfunction "C_K") (pintype "passive"))
      (node (ref "R179") (pin "2") (pinfunction "2_2") (pintype "passive"))
    )
    (net (code "145") (name "Net-(D108-C)") (class "Default")
      (node (ref "D108") (pin "K") (pinfunction "C_K") (pintype "passive"))
      (node (ref "R180") (pin "2") (pinfunction "2_2") (pintype "passive"))
    )
    (net (code "146") (name "Net-(D112-C)") (class "Default")
      (node (ref "D112") (pin "K") (pinfunction "C_K") (pintype "passive"))
      (node (ref "R187") (pin "2") (pinfunction "2_2") (pintype "passive"))
    )
    (net (code "147") (name "Net-(D113-C)") (class "Default")
      (node (ref "D113") (pin "K") (pinfunction "C_K") (pintype "passive"))
      (node (ref "R189") (pin "2") (pinfunction "2_2") (pintype "passive"))
    )
    (net (code "148") (name "Net-(D114-C)") (class "Default")
      (node (ref "D114") (pin "K") (pinfunction "C_K") (pintype "passive"))
      (node (ref "R190") (pin "2") (pinfunction "2_2") (pintype "passive"))
    )
    (net (code "149") (name "Net-(D115-C)") (class "Default")
      (node (ref "D115") (pin "K") (pinfunction "C_K") (pintype "passive"))
      (node (ref "R192") (pin "2") (pinfunction "2_2") (pintype "passive"))
    )
    (net (code "150") (name "Net-(D116-C)") (class "Default")
      (node (ref "D116") (pin "K") (pinfunction "C_K") (pintype "passive"))
      (node (ref "R194") (pin "2") (pinfunction "2_2") (pintype "passive"))
    )
    (net (code "151") (name "Net-(D117-C)") (class "Default")
      (node (ref "D117") (pin "K") (pinfunction "C_K") (pintype "passive"))
      (node (ref "R195") (pin "2") (pinfunction "2_2") (pintype "passive"))
    )
    (net (code "152") (name "Net-(D121-C)") (class "Default")
      (node (ref "D121") (pin "K") (pinfunction "C_K") (pintype "passive"))
      (node (ref "R202") (pin "2") (pinfunction "2_2") (pintype "passive"))
    )
    (net (code "153") (name "Net-(D122-C)") (class "Default")
      (node (ref "D122") (pin "K") (pinfunction "C_K") (pintype "passive"))
      (node (ref "R204") (pin "2") (pinfunction "2_2") (pintype "passive"))
    )
    (net (code "154") (name "Net-(D123-C)") (class "Default")
      (node (ref "D123") (pin "K") (pinfunction "C_K") (pintype "passive"))
      (node (ref "R205") (pin "2") (pinfunction "2_2") (pintype "passive"))
    )
    (net (code "155") (name "Net-(D124-C)") (class "Default")
      (node (ref "D124") (pin "K") (pinfunction "C_K") (pintype "passive"))
      (node (ref "R207") (pin "2") (pinfunction "2_2") (pintype "passive"))
    )
    (net (code "156") (name "Net-(D125-C)") (class "Default")
      (node (ref "D125") (pin "K") (pinfunction "C_K") (pintype "passive"))
      (node (ref "R209") (pin "2") (pinfunction "2_2") (pintype "passive"))
    )
    (net (code "157") (name "Net-(D126-C)") (class "Default")
      (node (ref "D126") (pin "K") (pinfunction "C_K") (pintype "passive"))
      (node (ref "R210") (pin "2") (pinfunction "2_2") (pintype "passive"))
    )
    (net (code "158") (name "Net-(D130-C)") (class "Default")
      (node (ref "D130") (pin "K") (pinfunction "C_K") (pintype "passive"))
      (node (ref "R217") (pin "2") (pinfunction "2_2") (pintype "passive"))
    )
    (net (code "159") (name "Net-(D131-C)") (class "Default")
      (node (ref "D131") (pin "K") (pinfunction "C_K") (pintype "passive"))
      (node (ref "R219") (pin "2") (pinfunction "2_2") (pintype "passive"))
    )
    (net (code "160") (name "Net-(D132-C)") (class "Default")
      (node (ref "D132") (pin "K") (pinfunction "C_K") (pintype "passive"))
      (node (ref "R220") (pin "2") (pinfunction "2_2") (pintype "passive"))
    )
    (net (code "161") (name "Net-(D133-C)") (class "Default")
      (node (ref "D133") (pin "K") (pinfunction "C_K") (pintype "passive"))
      (node (ref "R222") (pin "2") (pinfunction "2_2") (pintype "passive"))
    )
    (net (code "162") (name "Net-(D134-C)") (class "Default")
      (node (ref "D134") (pin "K") (pinfunction "C_K") (pintype "passive"))
      (node (ref "R224") (pin "2") (pinfunction "2_2") (pintype "passive"))
    )
    (net (code "163") (name "Net-(D135-C)") (class "Default")
      (node (ref "D135") (pin "K") (pinfunction "C_K") (pintype "passive"))
      (node (ref "R225") (pin "2") (pinfunction "2_2") (pintype "passive"))
    )
    (net (code "164") (name "Net-(D139-C)") (class "Default")
      (node (ref "D139") (pin "K") (pinfunction "C_K") (pintype "passive"))
      (node (ref "R232") (pin "2") (pinfunction "2_2") (pintype "passive"))
    )
    (net (code "165") (name "Net-(D140-C)") (class "Default")
      (node (ref "D140") (pin "K") (pinfunction "C_K") (pintype "passive"))
      (node (ref "R234") (pin "2") (pinfunction "2_2") (pintype "passive"))
    )
    (net (code "166") (name "Net-(D141-C)") (class "Default")
      (node (ref "D141") (pin "K") (pinfunction "C_K") (pintype "passive"))
      (node (ref "R235") (pin "2") (pinfunction "2_2") (pintype "passive"))
    )
    (net (code "167") (name "Net-(D142-C)") (class "Default")
      (node (ref "D142") (pin "K") (pinfunction "C_K") (pintype "passive"))
      (node (ref "R237") (pin "2") (pinfunction "2_2") (pintype "passive"))
    )
    (net (code "168") (name "Net-(D143-C)") (class "Default")
      (node (ref "D143") (pin "K") (pinfunction "C_K") (pintype "passive"))
      (node (ref "R239") (pin "2") (pinfunction "2_2") (pintype "passive"))
    )
    (net (code "169") (name "Net-(D144-C)") (class "Default")
      (node (ref "D144") (pin "K") (pinfunction "C_K") (pintype "passive"))
      (node (ref "R240") (pin "2") (pinfunction "2_2") (pintype "passive"))
    )
    (net (code "170") (name "Net-(D145-C)") (class "Default")
      (node (ref "D145") (pin "K") (pinfunction "C_K") (pintype "passive"))
      (node (ref "R259") (pin "2") (pinfunction "2_2") (pintype "passive"))
    )
    (net (code "171") (name "Net-(D146-C)") (class "Default")
      (node (ref "D146") (pin "K") (pinfunction "C_K") (pintype "passive"))
      (node (ref "R260") (pin "2") (pinfunction "2_2") (pintype "passive"))
    )
    (net (code "172") (name "Net-(D147-C)") (class "Default")
      (node (ref "D147") (pin "K") (pinfunction "C_K") (pintype "passive"))
      (node (ref "R261") (pin "2") (pinfunction "2_2") (pintype "passive"))
    )
    (net (code "173") (name "Net-(D148-C)") (class "Default")
      (node (ref "D148") (pin "K") (pinfunction "C_K") (pintype "passive"))
      (node (ref "R262") (pin "2") (pinfunction "2_2") (pintype "passive"))
    )
    (net (code "174") (name "Net-(D149-C)") (class "Default")
      (node (ref "D149") (pin "K") (pinfunction "C_K") (pintype "passive"))
      (node (ref "R263") (pin "2") (pinfunction "2_2") (pintype "passive"))
    )
    (net (code "175") (name "Net-(D150-C)") (class "Default")
      (node (ref "D150") (pin "K") (pinfunction "C_K") (pintype "passive"))
      (node (ref "R264") (pin "2") (pinfunction "2_2") (pintype "passive"))
    )
    (net (code "176") (name "Net-(D151-C)") (class "Default")
      (node (ref "D151") (pin "K") (pinfunction "C_K") (pintype "passive"))
      (node (ref "R265") (pin "2") (pinfunction "2_2") (pintype "passive"))
    )
    (net (code "177") (name "Net-(D152-C)") (class "Default")
      (node (ref "D152") (pin "K") (pinfunction "C_K") (pintype "passive"))
      (node (ref "R266") (pin "2") (pinfunction "2_2") (pintype "passive"))
    )
    (net (code "178") (name "Net-(D153-C)") (class "Default")
      (node (ref "D153") (pin "K") (pinfunction "C_K") (pintype "passive"))
      (node (ref "R267") (pin "2") (pinfunction "2_2") (pintype "passive"))
    )
    (net (code "179") (name "Net-(D155-C)") (class "Default")
      (node (ref "D155") (pin "K") (pinfunction "C_K") (pintype "passive"))
      (node (ref "R269") (pin "2") (pinfunction "2_2") (pintype "passive"))
    )
    (net (code "180") (name "Net-(D156-C)") (class "Default")
      (node (ref "D156") (pin "K") (pinfunction "C_K") (pintype "passive"))
      (node (ref "R270") (pin "2") (pinfunction "2_2") (pintype "passive"))
    )
    (net (code "181") (name "Net-(D157-C)") (class "Default")
      (node (ref "D157") (pin "K") (pinfunction "C_K") (pintype "passive"))
      (node (ref "R271") (pin "2") (pinfunction "2_2") (pintype "passive"))
    )
    (net (code "182") (name "Net-(D158-C)") (class "Default")
      (node (ref "D158") (pin "K") (pinfunction "C_K") (pintype "passive"))
      (node (ref "R272") (pin "2") (pinfunction "2_2") (pintype "passive"))
    )
    (net (code "183") (name "Net-(D159-C)") (class "Default")
      (node (ref "D159") (pin "K") (pinfunction "C_K") (pintype "passive"))
      (node (ref "R273") (pin "2") (pinfunction "2_2") (pintype "passive"))
    )
    (net (code "184") (name "Net-(D160-C)") (class "Default")
      (node (ref "D160") (pin "K") (pinfunction "C_K") (pintype "passive"))
      (node (ref "R274") (pin "2") (pinfunction "2_2") (pintype "passive"))
    )
    (net (code "185") (name "Net-(D161-C)") (class "Default")
      (node (ref "D161") (pin "K") (pinfunction "C_K") (pintype "passive"))
      (node (ref "R275") (pin "2") (pinfunction "2_2") (pintype "passive"))
    )
    (net (code "186") (name "Net-(D163-C)") (class "Default")
      (node (ref "D163") (pin "K") (pinfunction "C_K") (pintype "passive"))
      (node (ref "R277") (pin "2") (pinfunction "2_2") (pintype "passive"))
    )
    (net (code "187") (name "Net-(D164-C)") (class "Default")
      (node (ref "D164") (pin "K") (pinfunction "C_K") (pintype "passive"))
      (node (ref "R278") (pin "2") (pinfunction "2_2") (pintype "passive"))
    )
    (net (code "188") (name "Net-(D165-C)") (class "Default")
      (node (ref "D165") (pin "K") (pinfunction "C_K") (pintype "passive"))
      (node (ref "R279") (pin "2") (pinfunction "2_2") (pintype "passive"))
    )
    (net (code "189") (name "Net-(D166-C)") (class "Default")
      (node (ref "D166") (pin "K") (pinfunction "C_K") (pintype "passive"))
      (node (ref "R280") (pin "2") (pinfunction "2_2") (pintype "passive"))
    )
    (net (code "190") (name "Net-(D167-C)") (class "Default")
      (node (ref "D167") (pin "K") (pinfunction "C_K") (pintype "passive"))
      (node (ref "R281") (pin "2") (pinfunction "2_2") (pintype "passive"))
    )
    (net (code "191") (name "Net-(D168-C)") (class "Default")
      (node (ref "D168") (pin "K") (pinfunction "C_K") (pintype "passive"))
      (node (ref "R282") (pin "2") (pinfunction "2_2") (pintype "passive"))
    )
    (net (code "192") (name "Net-(D169-C)") (class "Default")
      (node (ref "D169") (pin "K") (pinfunction "C_K") (pintype "passive"))
      (node (ref "R283") (pin "2") (pinfunction "2_2") (pintype "passive"))
    )
    (net (code "193") (name "Net-(D170-C)") (class "Default")
      (node (ref "D170") (pin "K") (pinfunction "C_K") (pintype "passive"))
      (node (ref "R284") (pin "2") (pinfunction "2_2") (pintype "passive"))
    )
    (net (code "194") (name "Net-(Q4-PadD)") (class "Default")
      (node (ref "Q4") (pin "D") (pinfunction "D_D") (pintype "passive"))
      (node (ref "Q5") (pin "S") (pinfunction "S_S") (pintype "passive"))
    )
    (net (code "195") (name "Net-(Q6-PadS)") (class "Default")
      (node (ref "Q6") (pin "S") (pinfunction "S_S") (pintype "passive"))
      (node (ref "Q84") (pin "D") (pinfunction "D_D") (pintype "passive"))
    )
    (net (code "196") (name "Net-(Q7-PadS)") (class "Default")
      (node (ref "Q7") (pin "S") (pinfunction "S_S") (pintype "passive"))
      (node (ref "Q85") (pin "D") (pinfunction "D_D") (pintype "passive"))
    )
    (net (code "197") (name "Net-(Q8-PadS)") (class "Default")
      (node (ref "Q8") (pin "S") (pinfunction "S_S") (pintype "passive"))
      (node (ref "Q86") (pin "D") (pinfunction "D_D") (pintype "passive"))
    )
    (net (code "198") (name "Net-(Q10-PadS)") (class "Default")
      (node (ref "Q10") (pin "S") (pinfunction "S_S") (pintype "passive"))
      (node (ref "Q88") (pin "D") (pinfunction "D_D") (pintype "passive"))
    )
    (net (code "199") (name "Net-(Q11-PadS)") (class "Default")
      (node (ref "Q11") (pin "S") (pinfunction "S_S") (pintype "passive"))
      (node (ref "Q94") (pin "D") (pinfunction "D_D") (pintype "passive"))
    )
    (net (code "200") (name "Net-(Q12-PadS)") (class "Default")
      (node (ref "Q12") (pin "S") (pinfunction "S_S") (pintype "passive"))
      (node (ref "Q64") (pin "D") (pinfunction "D_D") (pintype "passive"))
    )
    (net (code "201") (name "Net-(Q13-PadD)") (class "Default")
      (node (ref "Q13") (pin "D") (pinfunction "D_D") (pintype "passive"))
      (node (ref "Q14") (pin "S") (pinfunction "S_S") (pintype "passive"))
    )
    (net (code "202") (name "Net-(Q15-PadS)") (class "Default")
      (node (ref "Q15") (pin "S") (pinfunction "S_S") (pintype "passive"))
      (node (ref "Q72") (pin "D") (pinfunction "D_D") (pintype "passive"))
    )
    (net (code "203") (name "Net-(Q16-PadS)") (class "Default")
      (node (ref "Q16") (pin "S") (pinfunction "S_S") (pintype "passive"))
      (node (ref "Q71") (pin "D") (pinfunction "D_D") (pintype "passive"))
    )
    (net (code "204") (name "Net-(Q17-PadS)") (class "Default")
      (node (ref "Q17") (pin "S") (pinfunction "S_S") (pintype "passive"))
      (node (ref "Q70") (pin "D") (pinfunction "D_D") (pintype "passive"))
    )
    (net (code "205") (name "Net-(Q18-PadS)") (class "Default")
      (node (ref "Q18") (pin "S") (pinfunction "S_S") (pintype "passive"))
      (node (ref "Q69") (pin "D") (pinfunction "D_D") (pintype "passive"))
    )
    (net (code "206") (name "Net-(Q19-PadS)") (class "Default")
      (node (ref "Q19") (pin "S") (pinfunction "S_S") (pintype "passive"))
      (node (ref "Q68") (pin "D") (pinfunction "D_D") (pintype "passive"))
    )
    (net (code "207") (name "Net-(Q20-PadS)") (class "Default")
      (node (ref "Q20") (pin "S") (pinfunction "S_S") (pintype "passive"))
      (node (ref "Q67") (pin "D") (pinfunction "D_D") (pintype "passive"))
    )
    (net (code "208") (name "Net-(Q21-PadS)") (class "Default")
      (node (ref "Q21") (pin "S") (pinfunction "S_S") (pintype "passive"))
      (node (ref "Q66") (pin "D") (pinfunction "D_D") (pintype "passive"))
    )
    (net (code "209") (name "Net-(Q22-PadS)") (class "Default")
      (node (ref "Q22") (pin "S") (pinfunction "S_S") (pintype "passive"))
      (node (ref "Q23") (pin "D") (pinfunction "D_D") (pintype "passive"))
    )
    (net (code "210") (name "Net-(Q24-PadS)") (class "Default")
      (node (ref "Q24") (pin "S") (pinfunction "S_S") (pintype "passive"))
      (node (ref "Q25") (pin "D") (pinfunction "D_D") (pintype "passive"))
    )
    (net (code "211") (name "Net-(Q27-PadD)") (class "Default")
      (node (ref "Q27") (pin "D") (pinfunction "D_D") (pintype "passive"))
      (node (ref "Q28") (pin "S") (pinfunction "S_S") (pintype "passive"))
    )
    (net (code "212") (name "Net-(Q29-PadS)") (class "Default")
      (node (ref "Q29") (pin "S") (pinfunction "S_S") (pintype "passive"))
      (node (ref "Q73") (pin "D") (pinfunction "D_D") (pintype "passive"))
    )
    (net (code "213") (name "Net-(Q30-PadS)") (class "Default")
      (node (ref "Q30") (pin "S") (pinfunction "S_S") (pintype "passive"))
      (node (ref "Q74") (pin "D") (pinfunction "D_D") (pintype "passive"))
    )
    (net (code "214") (name "Net-(Q31-PadS)") (class "Default")
      (node (ref "Q31") (pin "S") (pinfunction "S_S") (pintype "passive"))
      (node (ref "Q75") (pin "D") (pinfunction "D_D") (pintype "passive"))
    )
    (net (code "215") (name "Net-(Q32-PadS)") (class "Default")
      (node (ref "Q32") (pin "S") (pinfunction "S_S") (pintype "passive"))
      (node (ref "Q33") (pin "D") (pinfunction "D_D") (pintype "passive"))
    )
    (net (code "216") (name "Net-(Q34-PadS)") (class "Default")
      (node (ref "Q34") (pin "S") (pinfunction "S_S") (pintype "passive"))
      (node (ref "Q35") (pin "D") (pinfunction "D_D") (pintype "passive"))
    )
    (net (code "217") (name "Net-(Q37-PadS)") (class "Default")
      (node (ref "Q37") (pin "S") (pinfunction "S_S") (pintype "passive"))
      (node (ref "Q76") (pin "D") (pinfunction "D_D") (pintype "passive"))
    )
    (net (code "218") (name "Net-(Q38-PadS)") (class "Default")
      (node (ref "Q38") (pin "S") (pinfunction "S_S") (pintype "passive"))
      (node (ref "Q77") (pin "D") (pinfunction "D_D") (pintype "passive"))
    )
    (net (code "219") (name "Net-(Q39-PadS)") (class "Default")
      (node (ref "Q39") (pin "S") (pinfunction "S_S") (pintype "passive"))
      (node (ref "Q78") (pin "D") (pinfunction "D_D") (pintype "passive"))
    )
    (net (code "220") (name "Net-(Q40-PadS)") (class "Default")
      (node (ref "Q40") (pin "S") (pinfunction "S_S") (pintype "passive"))
      (node (ref "Q65") (pin "D") (pinfunction "D_D") (pintype "passive"))
    )
    (net (code "221") (name "Net-(Q54-PadS)") (class "Default")
      (node (ref "Q54") (pin "S") (pinfunction "S_S") (pintype "passive"))
      (node (ref "Q55") (pin "D") (pinfunction "D_D") (pintype "passive"))
    )
    (net (code "222") (name "Net-(Q57-PadS)") (class "Default")
      (node (ref "Q57") (pin "S") (pinfunction "S_S") (pintype "passive"))
      (node (ref "Q58") (pin "D") (pinfunction "D_D") (pintype "passive"))
    )
    (net (code "223") (name "Net-(Q79-PadS)") (class "Default")
      (node (ref "Q79") (pin "S") (pinfunction "S_S") (pintype "passive"))
      (node (ref "Q80") (pin "D") (pinfunction "D_D") (pintype "passive"))
    )
    (net (code "224") (name "Net-(Q81-PadS)") (class "Default")
      (node (ref "Q81") (pin "S") (pinfunction "S_S") (pintype "passive"))
      (node (ref "Q82") (pin "D") (pinfunction "D_D") (pintype "passive"))
    )
    (net (code "225") (name "Net-(Q87-PadD)") (class "Default")
      (node (ref "Q87") (pin "D") (pinfunction "D_D") (pintype "passive"))
      (node (ref "Q9") (pin "S") (pinfunction "S_S") (pintype "passive"))
    )
    (net (code "226") (name "Net-(Q89-PadS)") (class "Default")
      (node (ref "Q89") (pin "S") (pinfunction "S_S") (pintype "passive"))
      (node (ref "Q90") (pin "D") (pinfunction "D_D") (pintype "passive"))
    )
    (net (code "227") (name "Net-(Q91-PadS)") (class "Default")
      (node (ref "Q91") (pin "S") (pinfunction "S_S") (pintype "passive"))
      (node (ref "Q92") (pin "D") (pinfunction "D_D") (pintype "passive"))
    )
    (net (code "228") (name "Net-(Q100-PadD)") (class "Default")
      (node (ref "Q100") (pin "D") (pinfunction "D_D") (pintype "passive"))
      (node (ref "Q99") (pin "S") (pinfunction "S_S") (pintype "passive"))
    )
    (net (code "229") (name "Net-(Q101-PadS)") (class "Default")
      (node (ref "Q101") (pin "S") (pinfunction "S_S") (pintype "passive"))
      (node (ref "Q102") (pin "D") (pinfunction "D_D") (pintype "passive"))
    )
    (net (code "230") (name "Net-(Q109-PadS)") (class "Default")
      (node (ref "Q109") (pin "S") (pinfunction "S_S") (pintype "passive"))
      (node (ref "Q110") (pin "D") (pinfunction "D_D") (pintype "passive"))
    )
    (net (code "231") (name "Net-(Q111-PadS)") (class "Default")
      (node (ref "Q111") (pin "S") (pinfunction "S_S") (pintype "passive"))
      (node (ref "Q112") (pin "D") (pinfunction "D_D") (pintype "passive"))
    )
    (net (code "232") (name "Net-(Q119-PadS)") (class "Default")
      (node (ref "Q119") (pin "S") (pinfunction "S_S") (pintype "passive"))
      (node (ref "Q120") (pin "D") (pinfunction "D_D") (pintype "passive"))
    )
    (net (code "233") (name "Net-(Q121-PadS)") (class "Default")
      (node (ref "Q121") (pin "S") (pinfunction "S_S") (pintype "passive"))
      (node (ref "Q122") (pin "D") (pinfunction "D_D") (pintype "passive"))
    )
    (net (code "234") (name "Net-(Q129-PadS)") (class "Default")
      (node (ref "Q129") (pin "S") (pinfunction "S_S") (pintype "passive"))
      (node (ref "Q130") (pin "D") (pinfunction "D_D") (pintype "passive"))
    )
    (net (code "235") (name "Net-(Q131-PadS)") (class "Default")
      (node (ref "Q131") (pin "S") (pinfunction "S_S") (pintype "passive"))
      (node (ref "Q132") (pin "D") (pinfunction "D_D") (pintype "passive"))
    )
    (net (code "236") (name "Net-(Q145-PadS)") (class "Default")
      (node (ref "Q145") (pin "S") (pinfunction "S_S") (pintype "passive"))
      (node (ref "Q146") (pin "D") (pinfunction "D_D") (pintype "passive"))
    )
    (net (code "237") (name "Net-(Q154-PadS)") (class "Default")
      (node (ref "Q154") (pin "S") (pinfunction "S_S") (pintype "passive"))
      (node (ref "Q155") (pin "D") (pinfunction "D_D") (pintype "passive"))
    )
    (net (code "238") (name "Net-(Q163-PadS)") (class "Default")
      (node (ref "Q163") (pin "S") (pinfunction "S_S") (pintype "passive"))
      (node (ref "Q164") (pin "D") (pinfunction "D_D") (pintype "passive"))
    )
    (net (code "239") (name "Net-(Q172-PadS)") (class "Default")
      (node (ref "Q172") (pin "S") (pinfunction "S_S") (pintype "passive"))
      (node (ref "Q173") (pin "D") (pinfunction "D_D") (pintype "passive"))
    )
    (net (code "240") (name "Net-(Q181-PadS)") (class "Default")
      (node (ref "Q181") (pin "S") (pinfunction "S_S") (pintype "passive"))
      (node (ref "Q182") (pin "D") (pinfunction "D_D") (pintype "passive"))
    )
    (net (code "241") (name "Net-(Q190-PadS)") (class "Default")
      (node (ref "Q190") (pin "S") (pinfunction "S_S") (pintype "passive"))
      (node (ref "Q191") (pin "D") (pinfunction "D_D") (pintype "passive"))
    )
    (net (code "242") (name "OR0") (class "Default")
      (node (ref "Q14") (pin "G") (pinfunction "G_G") (pintype "passive"))
      (node (ref "Q47") (pin "D") (pinfunction "D_D") (pintype "passive"))
      (node (ref "R53") (pin "1") (pinfunction "1_1") (pintype "passive"))
    )
    (net (code "243") (name "OR0_N") (class "Default")
      (node (ref "Q45") (pin "D") (pinfunction "D_D") (pintype "passive"))
      (node (ref "Q46") (pin "D") (pinfunction "D_D") (pintype "passive"))
      (node (ref "Q47") (pin "G") (pinfunction "G_G") (pintype "passive"))
      (node (ref "R43") (pin "1") (pinfunction "1_1") (pintype "passive"))
      (node (ref "R51") (pin "1") (pinfunction "1_1") (pintype "passive"))
      (node (ref "R52") (pin "1") (pinfunction "1_1") (pintype "passive"))
    )
    (net (code "244") (name "OR1") (class "Default")
      (node (ref "Q15") (pin "G") (pinfunction "G_G") (pintype "passive"))
      (node (ref "Q53") (pin "D") (pinfunction "D_D") (pintype "passive"))
      (node (ref "R63") (pin "1") (pinfunction "1_1") (pintype "passive"))
    )
    (net (code "245") (name "OR1_N") (class "Default")
      (node (ref "Q51") (pin "D") (pinfunction "D_D") (pintype "passive"))
      (node (ref "Q52") (pin "D") (pinfunction "D_D") (pintype "passive"))
      (node (ref "Q53") (pin "G") (pinfunction "G_G") (pintype "passive"))
      (node (ref "R44") (pin "1") (pinfunction "1_1") (pintype "passive"))
      (node (ref "R61") (pin "1") (pinfunction "1_1") (pintype "passive"))
      (node (ref "R62") (pin "1") (pinfunction "1_1") (pintype "passive"))
    )
    (net (code "246") (name "OR2") (class "Default")
      (node (ref "Q144") (pin "D") (pinfunction "D_D") (pintype "passive"))
      (node (ref "Q16") (pin "G") (pinfunction "G_G") (pintype "passive"))
      (node (ref "R158") (pin "1") (pinfunction "1_1") (pintype "passive"))
    )
    (net (code "247") (name "OR2_N") (class "Default")
      (node (ref "Q142") (pin "D") (pinfunction "D_D") (pintype "passive"))
      (node (ref "Q143") (pin "D") (pinfunction "D_D") (pintype "passive"))
      (node (ref "Q144") (pin "G") (pinfunction "G_G") (pintype "passive"))
      (node (ref "R156") (pin "1") (pinfunction "1_1") (pintype "passive"))
      (node (ref "R157") (pin "1") (pinfunction "1_1") (pintype "passive"))
      (node (ref "R45") (pin "1") (pinfunction "1_1") (pintype "passive"))
    )
    (net (code "248") (name "OR3") (class "Default")
      (node (ref "Q153") (pin "D") (pinfunction "D_D") (pintype "passive"))
      (node (ref "Q17") (pin "G") (pinfunction "G_G") (pintype "passive"))
      (node (ref "R173") (pin "1") (pinfunction "1_1") (pintype "passive"))
    )
    (net (code "249") (name "OR3_N") (class "Default")
      (node (ref "Q151") (pin "D") (pinfunction "D_D") (pintype "passive"))
      (node (ref "Q152") (pin "D") (pinfunction "D_D") (pintype "passive"))
      (node (ref "Q153") (pin "G") (pinfunction "G_G") (pintype "passive"))
      (node (ref "R171") (pin "1") (pinfunction "1_1") (pintype "passive"))
      (node (ref "R172") (pin "1") (pinfunction "1_1") (pintype "passive"))
      (node (ref "R46") (pin "1") (pinfunction "1_1") (pintype "passive"))
    )
    (net (code "250") (name "OR4") (class "Default")
      (node (ref "Q162") (pin "D") (pinfunction "D_D") (pintype "passive"))
      (node (ref "Q18") (pin "G") (pinfunction "G_G") (pintype "passive"))
      (node (ref "R188") (pin "1") (pinfunction "1_1") (pintype "passive"))
    )
    (net (code "251") (name "OR4_N") (class "Default")
      (node (ref "Q160") (pin "D") (pinfunction "D_D") (pintype "passive"))
      (node (ref "Q161") (pin "D") (pinfunction "D_D") (pintype "passive"))
      (node (ref "Q162") (pin "G") (pinfunction "G_G") (pintype "passive"))
      (node (ref "R186") (pin "1") (pinfunction "1_1") (pintype "passive"))
      (node (ref "R187") (pin "1") (pinfunction "1_1") (pintype "passive"))
      (node (ref "R47") (pin "1") (pinfunction "1_1") (pintype "passive"))
    )
    (net (code "252") (name "OR5") (class "Default")
      (node (ref "Q171") (pin "D") (pinfunction "D_D") (pintype "passive"))
      (node (ref "Q19") (pin "G") (pinfunction "G_G") (pintype "passive"))
      (node (ref "R203") (pin "1") (pinfunction "1_1") (pintype "passive"))
    )
    (net (code "253") (name "OR5_N") (class "Default")
      (node (ref "Q169") (pin "D") (pinfunction "D_D") (pintype "passive"))
      (node (ref "Q170") (pin "D") (pinfunction "D_D") (pintype "passive"))
      (node (ref "Q171") (pin "G") (pinfunction "G_G") (pintype "passive"))
      (node (ref "R201") (pin "1") (pinfunction "1_1") (pintype "passive"))
      (node (ref "R202") (pin "1") (pinfunction "1_1") (pintype "passive"))
      (node (ref "R48") (pin "1") (pinfunction "1_1") (pintype "passive"))
    )
    (net (code "254") (name "OR6") (class "Default")
      (node (ref "Q180") (pin "D") (pinfunction "D_D") (pintype "passive"))
      (node (ref "Q20") (pin "G") (pinfunction "G_G") (pintype "passive"))
      (node (ref "R218") (pin "1") (pinfunction "1_1") (pintype "passive"))
    )
    (net (code "255") (name "OR6_N") (class "Default")
      (node (ref "Q178") (pin "D") (pinfunction "D_D") (pintype "passive"))
      (node (ref "Q179") (pin "D") (pinfunction "D_D") (pintype "passive"))
      (node (ref "Q180") (pin "G") (pinfunction "G_G") (pintype "passive"))
      (node (ref "R216") (pin "1") (pinfunction "1_1") (pintype "passive"))
      (node (ref "R217") (pin "1") (pinfunction "1_1") (pintype "passive"))
      (node (ref "R49") (pin "1") (pinfunction "1_1") (pintype "passive"))
    )
    (net (code "256") (name "OR7") (class "Default")
      (node (ref "Q189") (pin "D") (pinfunction "D_D") (pintype "passive"))
      (node (ref "Q21") (pin "G") (pinfunction "G_G") (pintype "passive"))
      (node (ref "R233") (pin "1") (pinfunction "1_1") (pintype "passive"))
    )
    (net (code "257") (name "OR7_N") (class "Default")
      (node (ref "Q187") (pin "D") (pinfunction "D_D") (pintype "passive"))
      (node (ref "Q188") (pin "D") (pinfunction "D_D") (pintype "passive"))
      (node (ref "Q189") (pin "G") (pinfunction "G_G") (pintype "passive"))
      (node (ref "R231") (pin "1") (pinfunction "1_1") (pintype "passive"))
      (node (ref "R232") (pin "1") (pinfunction "1_1") (pintype "passive"))
      (node (ref "R50") (pin "1") (pinfunction "1_1") (pintype "passive"))
    )
    (net (code "258") (name "XOR0") (class "Default")
      (node (ref "Q26") (pin "D") (pinfunction "D_D") (pintype "passive"))
      (node (ref "Q28") (pin "G") (pinfunction "G_G") (pintype "passive"))
      (node (ref "R28") (pin "1") (pinfunction "1_1") (pintype "passive"))
    )
    (net (code "259") (name "XOR0_N") (class "Default")
      (node (ref "Q22") (pin "D") (pinfunction "D_D") (pintype "passive"))
      (node (ref "Q24") (pin "D") (pinfunction "D_D") (pintype "passive"))
      (node (ref "Q26") (pin "G") (pinfunction "G_G") (pintype "passive"))
      (node (ref "R26") (pin "1") (pinfunction "1_1") (pintype "passive"))
      (node (ref "R27") (pin "1") (pinfunction "1_1") (pintype "passive"))
      (node (ref "R80") (pin "1") (pinfunction "1_1") (pintype "passive"))
    )
    (net (code "260") (name "XOR1") (class "Default")
      (node (ref "Q29") (pin "G") (pinfunction "G_G") (pintype "passive"))
      (node (ref "Q36") (pin "D") (pinfunction "D_D") (pintype "passive"))
      (node (ref "R38") (pin "1") (pinfunction "1_1") (pintype "passive"))
    )
    (net (code "261") (name "XOR1_N") (class "Default")
      (node (ref "Q32") (pin "D") (pinfunction "D_D") (pintype "passive"))
      (node (ref "Q34") (pin "D") (pinfunction "D_D") (pintype "passive"))
      (node (ref "Q36") (pin "G") (pinfunction "G_G") (pintype "passive"))
      (node (ref "R36") (pin "1") (pinfunction "1_1") (pintype "passive"))
      (node (ref "R37") (pin "1") (pinfunction "1_1") (pintype "passive"))
      (node (ref "R81") (pin "1") (pinfunction "1_1") (pintype "passive"))
    )
    (net (code "262") (name "XOR2") (class "Default")
      (node (ref "Q30") (pin "G") (pinfunction "G_G") (pintype "passive"))
      (node (ref "Q83") (pin "D") (pinfunction "D_D") (pintype "passive"))
      (node (ref "R93") (pin "1") (pinfunction "1_1") (pintype "passive"))
    )
    (net (code "263") (name "XOR2_N") (class "Default")
      (node (ref "Q79") (pin "D") (pinfunction "D_D") (pintype "passive"))
      (node (ref "Q81") (pin "D") (pinfunction "D_D") (pintype "passive"))
      (node (ref "Q83") (pin "G") (pinfunction "G_G") (pintype "passive"))
      (node (ref "R82") (pin "1") (pinfunction "1_1") (pintype "passive"))
      (node (ref "R91") (pin "1") (pinfunction "1_1") (pintype "passive"))
      (node (ref "R92") (pin "1") (pinfunction "1_1") (pintype "passive"))
    )
    (net (code "264") (name "XOR3") (class "Default")
      (node (ref "Q31") (pin "G") (pinfunction "G_G") (pintype "passive"))
      (node (ref "Q93") (pin "D") (pinfunction "D_D") (pintype "passive"))
      (node (ref "R103") (pin "1") (pinfunction "1_1") (pintype "passive"))
    )
    (net (code "265") (name "XOR3_N") (class "Default")
      (node (ref "Q89") (pin "D") (pinfunction "D_D") (pintype "passive"))
      (node (ref "Q91") (pin "D") (pinfunction "D_D") (pintype "passive"))
      (node (ref "Q93") (pin "G") (pinfunction "G_G") (pintype "passive"))
      (node (ref "R101") (pin "1") (pinfunction "1_1") (pintype "passive"))
      (node (ref "R102") (pin "1") (pinfunction "1_1") (pintype "passive"))
      (node (ref "R83") (pin "1") (pinfunction "1_1") (pintype "passive"))
    )
    (net (code "266") (name "XOR4") (class "Default")
      (node (ref "Q103") (pin "D") (pinfunction "D_D") (pintype "passive"))
      (node (ref "Q37") (pin "G") (pinfunction "G_G") (pintype "passive"))
      (node (ref "R113") (pin "1") (pinfunction "1_1") (pintype "passive"))
    )
    (net (code "267") (name "XOR4_N") (class "Default")
      (node (ref "Q101") (pin "D") (pinfunction "D_D") (pintype "passive"))
      (node (ref "Q103") (pin "G") (pinfunction "G_G") (pintype "passive"))
      (node (ref "Q99") (pin "D") (pinfunction "D_D") (pintype "passive"))
      (node (ref "R111") (pin "1") (pinfunction "1_1") (pintype "passive"))
      (node (ref "R112") (pin "1") (pinfunction "1_1") (pintype "passive"))
      (node (ref "R84") (pin "1") (pinfunction "1_1") (pintype "passive"))
    )
    (net (code "268") (name "XOR5") (class "Default")
      (node (ref "Q113") (pin "D") (pinfunction "D_D") (pintype "passive"))
      (node (ref "Q38") (pin "G") (pinfunction "G_G") (pintype "passive"))
      (node (ref "R123") (pin "1") (pinfunction "1_1") (pintype "passive"))
    )
    (net (code "269") (name "XOR5_N") (class "Default")
      (node (ref "Q109") (pin "D") (pinfunction "D_D") (pintype "passive"))
      (node (ref "Q111") (pin "D") (pinfunction "D_D") (pintype "passive"))
      (node (ref "Q113") (pin "G") (pinfunction "G_G") (pintype "passive"))
      (node (ref "R121") (pin "1") (pinfunction "1_1") (pintype "passive"))
      (node (ref "R122") (pin "1") (pinfunction "1_1") (pintype "passive"))
      (node (ref "R85") (pin "1") (pinfunction "1_1") (pintype "passive"))
    )
    (net (code "270") (name "XOR6") (class "Default")
      (node (ref "Q123") (pin "D") (pinfunction "D_D") (pintype "passive"))
      (node (ref "Q39") (pin "G") (pinfunction "G_G") (pintype "passive"))
      (node (ref "R133") (pin "1") (pinfunction "1_1") (pintype "passive"))
    )
    (net (code "271") (name "XOR6_N") (class "Default")
      (node (ref "Q119") (pin "D") (pinfunction "D_D") (pintype "passive"))
      (node (ref "Q121") (pin "D") (pinfunction "D_D") (pintype "passive"))
      (node (ref "Q123") (pin "G") (pinfunction "G_G") (pintype "passive"))
      (node (ref "R131") (pin "1") (pinfunction "1_1") (pintype "passive"))
      (node (ref "R132") (pin "1") (pinfunction "1_1") (pintype "passive"))
      (node (ref "R86") (pin "1") (pinfunction "1_1") (pintype "passive"))
    )
    (net (code "272") (name "XOR7") (class "Default")
      (node (ref "Q133") (pin "D") (pinfunction "D_D") (pintype "passive"))
      (node (ref "Q40") (pin "G") (pinfunction "G_G") (pintype "passive"))
      (node (ref "R143") (pin "1") (pinfunction "1_1") (pintype "passive"))
    )
    (net (code "273") (name "XOR7_N") (class "Default")
      (node (ref "Q129") (pin "D") (pinfunction "D_D") (pintype "passive"))
      (node (ref "Q131") (pin "D") (pinfunction "D_D") (pintype "passive"))
      (node (ref "Q133") (pin "G") (pinfunction "G_G") (pintype "passive"))
      (node (ref "R141") (pin "1") (pinfunction "1_1") (pintype "passive"))
      (node (ref "R142") (pin "1") (pinfunction "1_1") (pintype "passive"))
      (node (ref "R87") (pin "1") (pinfunction "1_1") (pintype "passive"))
    )
    (net (code "274") (name "Y0") (class "Default")
      (node (ref "J3") (pin "2") (pinfunction "2_2") (pintype "bidirectional"))
      (node (ref "J4") (pin "20") (pinfunction "20_20") (pintype "bidirectional"))
      (node (ref "Q41") (pin "D") (pinfunction "D_D") (pintype "passive"))
      (node (ref "R89") (pin "1") (pinfunction "1_1") (pintype "passive"))
    )
    (net (code "275") (name "Y0_N") (class "Default")
      (node (ref "Q14") (pin "D") (pinfunction "D_D") (pintype "passive"))
      (node (ref "Q28") (pin "D") (pinfunction "D_D") (pintype "passive"))
      (node (ref "Q41") (pin "G") (pinfunction "G_G") (pintype "passive"))
      (node (ref "Q5") (pin "D") (pinfunction "D_D") (pintype "passive"))
      (node (ref "R277") (pin "1") (pinfunction "1_1") (pintype "passive"))
      (node (ref "R7") (pin "1") (pinfunction "1_1") (pintype "passive"))
      (node (ref "R88") (pin "1") (pinfunction "1_1") (pintype "passive"))
    )
    (net (code "276") (name "Y1") (class "Default")
      (node (ref "J3") (pin "3") (pinfunction "3_3") (pintype "bidirectional"))
      (node (ref "J4") (pin "21") (pinfunction "21_21") (pintype "bidirectional"))
      (node (ref "Q42") (pin "D") (pinfunction "D_D") (pintype "passive"))
      (node (ref "R96") (pin "1") (pinfunction "1_1") (pintype "passive"))
    )
    (net (code "277") (name "Y1_N") (class "Default")
      (node (ref "Q15") (pin "D") (pinfunction "D_D") (pintype "passive"))
      (node (ref "Q29") (pin "D") (pinfunction "D_D") (pintype "passive"))
      (node (ref "Q42") (pin "G") (pinfunction "G_G") (pintype "passive"))
      (node (ref "Q6") (pin "D") (pinfunction "D_D") (pintype "passive"))
      (node (ref "R278") (pin "1") (pinfunction "1_1") (pintype "passive"))
      (node (ref "R9") (pin "1") (pinfunction "1_1") (pintype "passive"))
      (node (ref "R90") (pin "1") (pinfunction "1_1") (pintype "passive"))
    )
    (net (code "278") (name "Y2") (class "Default")
      (node (ref "J3") (pin "4") (pinfunction "4_4") (pintype "bidirectional"))
      (node (ref "J4") (pin "22") (pinfunction "22_22") (pintype "bidirectional"))
      (node (ref "Q43") (pin "D") (pinfunction "D_D") (pintype "passive"))
      (node (ref "R98") (pin "1") (pinfunction "1_1") (pintype "passive"))
    )
    (net (code "279") (name "Y2_N") (class "Default")
      (node (ref "Q16") (pin "D") (pinfunction "D_D") (pintype "passive"))
      (node (ref "Q30") (pin "D") (pinfunction "D_D") (pintype "passive"))
      (node (ref "Q43") (pin "G") (pinfunction "G_G") (pintype "passive"))
      (node (ref "Q7") (pin "D") (pinfunction "D_D") (pintype "passive"))
      (node (ref "R10") (pin "1") (pinfunction "1_1") (pintype "passive"))
      (node (ref "R279") (pin "1") (pinfunction "1_1") (pintype "passive"))
      (node (ref "R97") (pin "1") (pinfunction "1_1") (pintype "passive"))
    )
    (net (code "280") (name "Y3") (class "Default")
      (node (ref "J3") (pin "5") (pinfunction "5_5") (pintype "bidirectional"))
      (node (ref "J4") (pin "23") (pinfunction "23_23") (pintype "bidirectional"))
      (node (ref "Q44") (pin "D") (pinfunction "D_D") (pintype "passive"))
      (node (ref "R100") (pin "1") (pinfunction "1_1") (pintype "passive"))
    )
    (net (code "281") (name "Y3_N") (class "Default")
      (node (ref "Q17") (pin "D") (pinfunction "D_D") (pintype "passive"))
      (node (ref "Q31") (pin "D") (pinfunction "D_D") (pintype "passive"))
      (node (ref "Q44") (pin "G") (pinfunction "G_G") (pintype "passive"))
      (node (ref "Q8") (pin "D") (pinfunction "D_D") (pintype "passive"))
      (node (ref "R11") (pin "1") (pinfunction "1_1") (pintype "passive"))
      (node (ref "R280") (pin "1") (pinfunction "1_1") (pintype "passive"))
      (node (ref "R99") (pin "1") (pinfunction "1_1") (pintype "passive"))
    )
    (net (code "282") (name "Y4") (class "Default")
      (node (ref "J3") (pin "6") (pinfunction "6_6") (pintype "bidirectional"))
      (node (ref "J4") (pin "24") (pinfunction "24_24") (pintype "bidirectional"))
      (node (ref "Q60") (pin "D") (pinfunction "D_D") (pintype "passive"))
      (node (ref "R118") (pin "1") (pinfunction "1_1") (pintype "passive"))
    )
    (net (code "283") (name "Y4_N") (class "Default")
      (node (ref "Q18") (pin "D") (pinfunction "D_D") (pintype "passive"))
      (node (ref "Q37") (pin "D") (pinfunction "D_D") (pintype "passive"))
      (node (ref "Q60") (pin "G") (pinfunction "G_G") (pintype "passive"))
      (node (ref "Q9") (pin "D") (pinfunction "D_D") (pintype "passive"))
      (node (ref "R117") (pin "1") (pinfunction "1_1") (pintype "passive"))
      (node (ref "R12") (pin "1") (pinfunction "1_1") (pintype "passive"))
      (node (ref "R281") (pin "1") (pinfunction "1_1") (pintype "passive"))
    )
    (net (code "284") (name "Y5") (class "Default")
      (node (ref "J3") (pin "7") (pinfunction "7_7") (pintype "bidirectional"))
      (node (ref "J4") (pin "25") (pinfunction "25_25") (pintype "bidirectional"))
      (node (ref "Q50") (pin "D") (pinfunction "D_D") (pintype "passive"))
      (node (ref "R116") (pin "1") (pinfunction "1_1") (pintype "passive"))
    )
    (net (code "285") (name "Y5_N") (class "Default")
      (node (ref "Q10") (pin "D") (pinfunction "D_D") (pintype "passive"))
      (node (ref "Q19") (pin "D") (pinfunction "D_D") (pintype "passive"))
      (node (ref "Q38") (pin "D") (pinfunction "D_D") (pintype "passive"))
      (node (ref "Q50") (pin "G") (pinfunction "G_G") (pintype "passive"))
      (node (ref "R110") (pin "1") (pinfunction "1_1") (pintype "passive"))
      (node (ref "R13") (pin "1") (pinfunction "1_1") (pintype "passive"))
      (node (ref "R282") (pin "1") (pinfunction "1_1") (pintype "passive"))
    )
    (net (code "286") (name "Y6") (class "Default")
      (node (ref "J3") (pin "8") (pinfunction "8_8") (pintype "bidirectional"))
      (node (ref "J4") (pin "26") (pinfunction "26_26") (pintype "bidirectional"))
      (node (ref "Q49") (pin "D") (pinfunction "D_D") (pintype "passive"))
      (node (ref "R109") (pin "1") (pinfunction "1_1") (pintype "passive"))
    )
    (net (code "287") (name "Y6_N") (class "Default")
      (node (ref "Q11") (pin "D") (pinfunction "D_D") (pintype "passive"))
      (node (ref "Q20") (pin "D") (pinfunction "D_D") (pintype "passive"))
      (node (ref "Q39") (pin "D") (pinfunction "D_D") (pintype "passive"))
      (node (ref "Q49") (pin "G") (pinfunction "G_G") (pintype "passive"))
      (node (ref "R108") (pin "1") (pinfunction "1_1") (pintype "passive"))
      (node (ref "R14") (pin "1") (pinfunction "1_1") (pintype "passive"))
      (node (ref "R283") (pin "1") (pinfunction "1_1") (pintype "passive"))
    )
    (net (code "288") (name "Y7") (class "Default")
      (node (ref "J3") (pin "9") (pinfunction "9_9") (pintype "bidirectional"))
      (node (ref "J4") (pin "27") (pinfunction "27_27") (pintype "bidirectional"))
      (node (ref "Q48") (pin "D") (pinfunction "D_D") (pintype "passive"))
      (node (ref "R107") (pin "1") (pinfunction "1_1") (pintype "passive"))
    )
    (net (code "289") (name "Y7_N") (class "Default")
      (node (ref "Q12") (pin "D") (pinfunction "D_D") (pintype "passive"))
      (node (ref "Q21") (pin "D") (pinfunction "D_D") (pintype "passive"))
      (node (ref "Q40") (pin "D") (pinfunction "D_D") (pintype "passive"))
      (node (ref "Q48") (pin "G") (pinfunction "G_G") (pintype "passive"))
      (node (ref "R106") (pin "1") (pinfunction "1_1") (pintype "passive"))
      (node (ref "R15") (pin "1") (pinfunction "1_1") (pintype "passive"))
      (node (ref "R284") (pin "1") (pinfunction "1_1") (pintype "passive"))
    )
    (net (code "290") (name "unconnected-(J1-Pad12)") (class "Default")
      (node (ref "J1") (pin "12") (pinfunction "12_12") (pintype "bidirectional"))
    )
    (net (code "291") (name "unconnected-(J1-Pad13)") (class "Default")
      (node (ref "J1") (pin "13") (pinfunction "13_13") (pintype "bidirectional"))
    )
    (net (code "292") (name "unconnected-(J1-Pad14)") (class "Default")
      (node (ref "J1") (pin "14") (pinfunction "14_14") (pintype "bidirectional"))
    )
    (net (code "293") (name "unconnected-(J1-Pad15)") (class "Default")
      (node (ref "J1") (pin "15") (pinfunction "15_15") (pintype "bidirectional"))
    )
    (net (code "294") (name "unconnected-(J1-Pad16)") (class "Default")
      (node (ref "J1") (pin "16") (pinfunction "16_16") (pintype "bidirectional"))
    )
    (net (code "295") (name "unconnected-(J1-Pad17)") (class "Default")
      (node (ref "J1") (pin "17") (pinfunction "17_17") (pintype "bidirectional"))
    )
    (net (code "296") (name "unconnected-(J1-Pad18)") (class "Default")
      (node (ref "J1") (pin "18") (pinfunction "18_18") (pintype "bidirectional"))
    )
    (net (code "297") (name "unconnected-(J1-Pad19)") (class "Default")
      (node (ref "J1") (pin "19") (pinfunction "19_19") (pintype "bidirectional"))
    )
    (net (code "298") (name "unconnected-(J2-Pad12)") (class "Default")
      (node (ref "J2") (pin "12") (pinfunction "12_12") (pintype "bidirectional"))
    )
    (net (code "299") (name "unconnected-(J2-Pad13)") (class "Default")
      (node (ref "J2") (pin "13") (pinfunction "13_13") (pintype "bidirectional"))
    )
    (net (code "300") (name "unconnected-(J2-Pad14)") (class "Default")
      (node (ref "J2") (pin "14") (pinfunction "14_14") (pintype "bidirectional"))
    )
    (net (code "301") (name "unconnected-(J2-Pad15)") (class "Default")
      (node (ref "J2") (pin "15") (pinfunction "15_15") (pintype "bidirectional"))
    )
    (net (code "302") (name "unconnected-(J2-Pad16)") (class "Default")
      (node (ref "J2") (pin "16") (pinfunction "16_16") (pintype "bidirectional"))
    )
    (net (code "303") (name "unconnected-(J2-Pad17)") (class "Default")
      (node (ref "J2") (pin "17") (pinfunction "17_17") (pintype "bidirectional"))
    )
    (net (code "304") (name "unconnected-(J2-Pad18)") (class "Default")
      (node (ref "J2") (pin "18") (pinfunction "18_18") (pintype "bidirectional"))
    )
    (net (code "305") (name "unconnected-(J2-Pad19)") (class "Default")
      (node (ref "J2") (pin "19") (pinfunction "19_19") (pintype "bidirectional"))
    )
    (net (code "306") (name "unconnected-(J3-Pad12)") (class "Default")
      (node (ref "J3") (pin "12") (pinfunction "12_12") (pintype "bidirectional"))
    )
    (net (code "307") (name "unconnected-(J3-Pad13)") (class "Default")
      (node (ref "J3") (pin "13") (pinfunction "13_13") (pintype "bidirectional"))
    )
    (net (code "308") (name "unconnected-(J3-Pad14)") (class "Default")
      (node (ref "J3") (pin "14") (pinfunction "14_14") (pintype "bidirectional"))
    )
    (net (code "309") (name "unconnected-(J3-Pad15)") (class "Default")
      (node (ref "J3") (pin "15") (pinfunction "15_15") (pintype "bidirectional"))
    )
    (net (code "310") (name "unconnected-(J3-Pad16)") (class "Default")
      (node (ref "J3") (pin "16") (pinfunction "16_16") (pintype "bidirectional"))
    )
    (net (code "311") (name "unconnected-(J3-Pad17)") (class "Default")
      (node (ref "J3") (pin "17") (pinfunction "17_17") (pintype "bidirectional"))
    )
    (net (code "312") (name "unconnected-(J3-Pad18)") (class "Default")
      (node (ref "J3") (pin "18") (pinfunction "18_18") (pintype "bidirectional"))
    )
    (net (code "313") (name "unconnected-(J3-Pad19)") (class "Default")
      (node (ref "J3") (pin "19") (pinfunction "19_19") (pintype "bidirectional"))
    )
    (net (code "314") (name "unconnected-(J4-Pad29)") (class "Default")
      (node (ref "J4") (pin "29") (pinfunction "29_29") (pintype "bidirectional"))
    )
    (net (code "315") (name "unconnected-(J4-Pad30)") (class "Default")
      (node (ref "J4") (pin "30") (pinfunction "30_30") (pintype "bidirectional"))
    )
  )
)
